# Beilage_xx.net
KiCad netlist of a schematic drawn in EAGLE
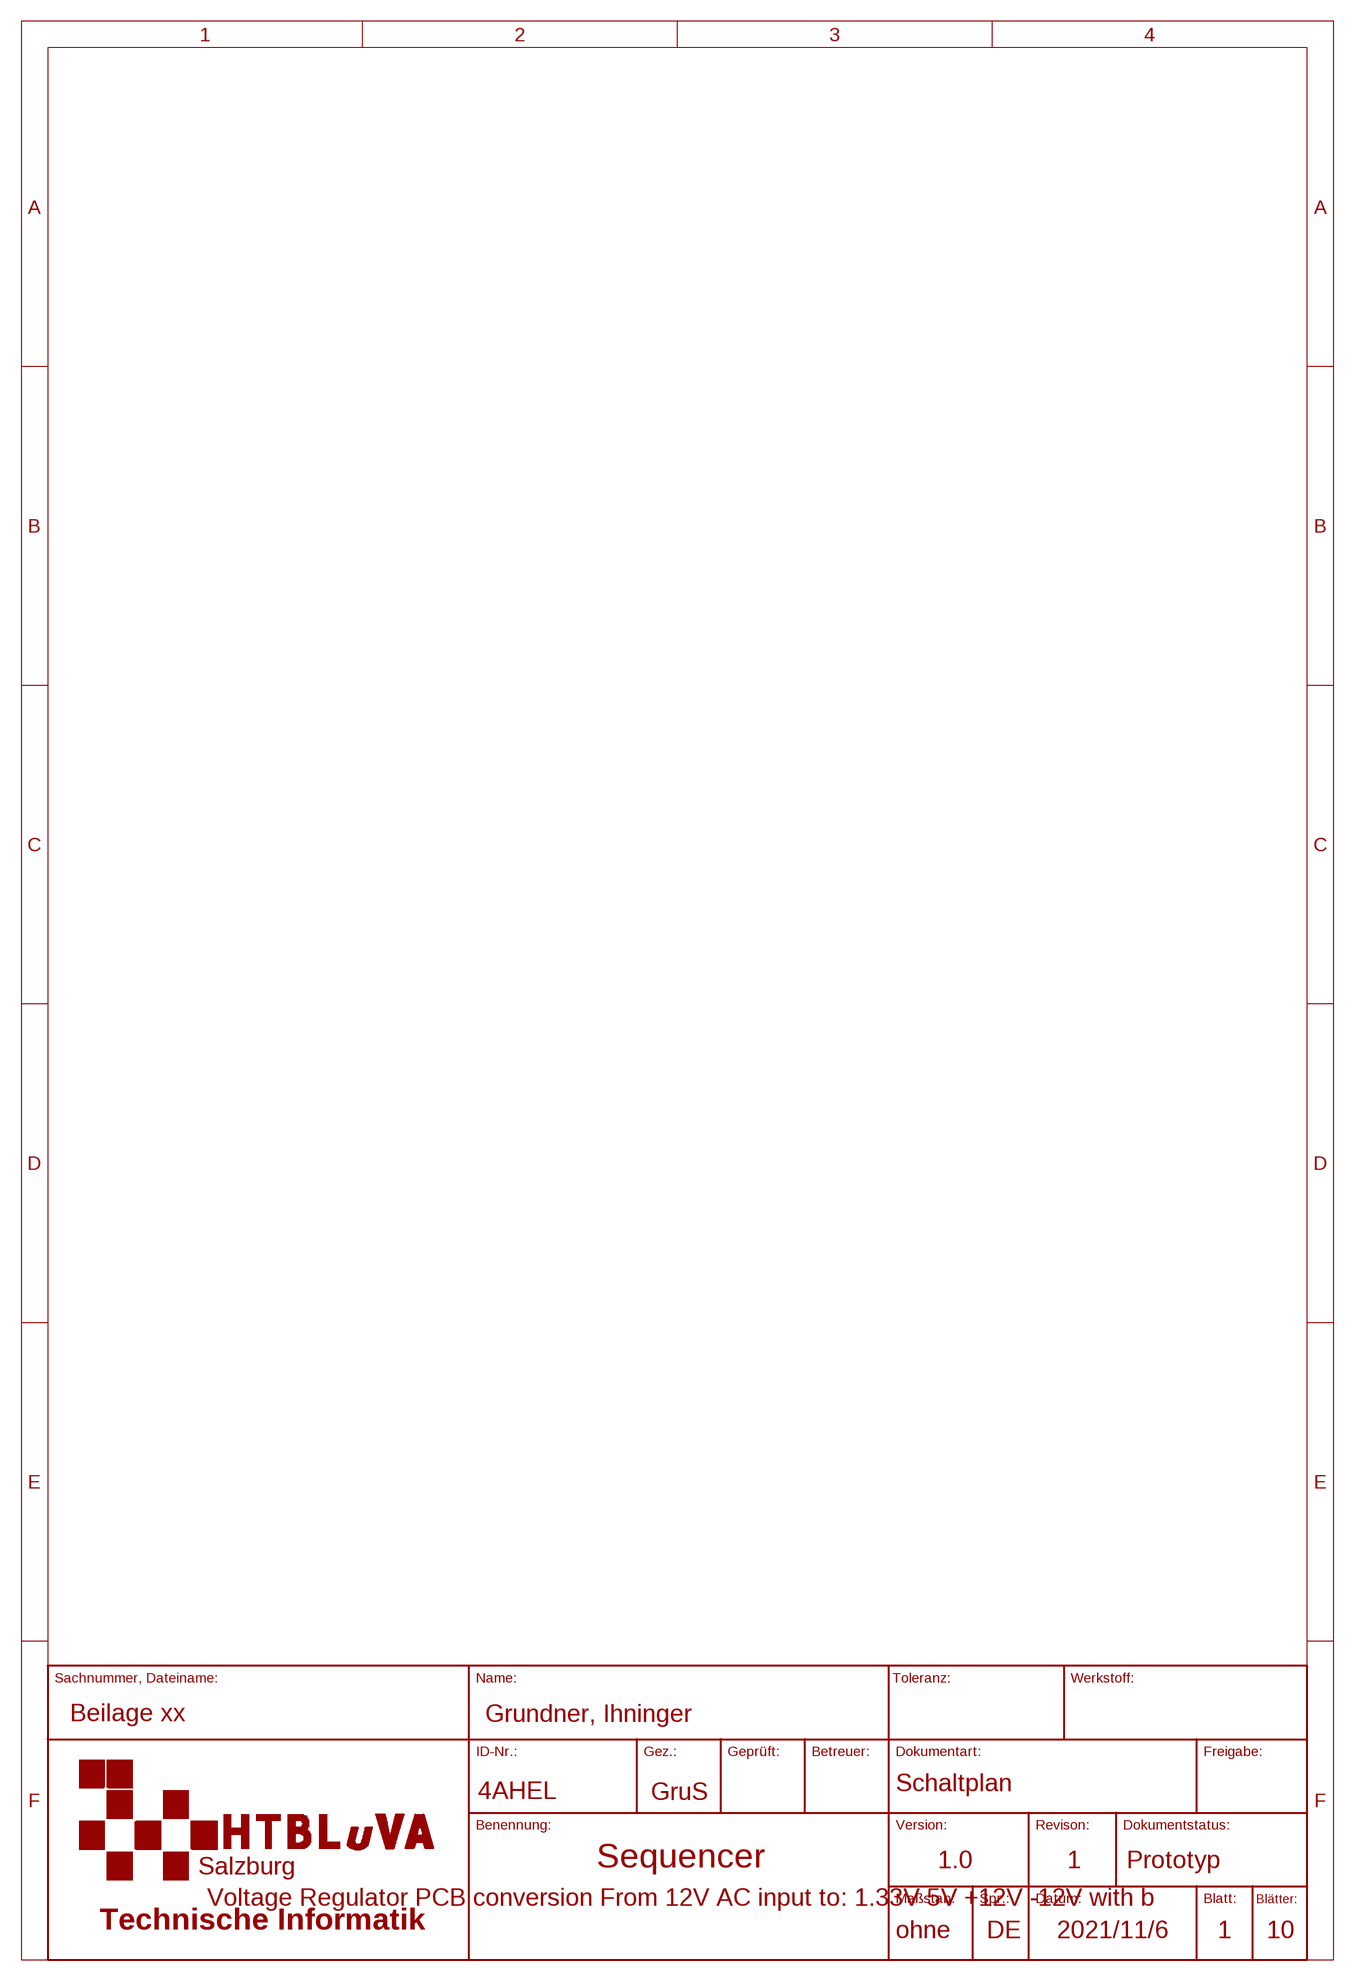
[diagram p0: schematic, sheet 1]
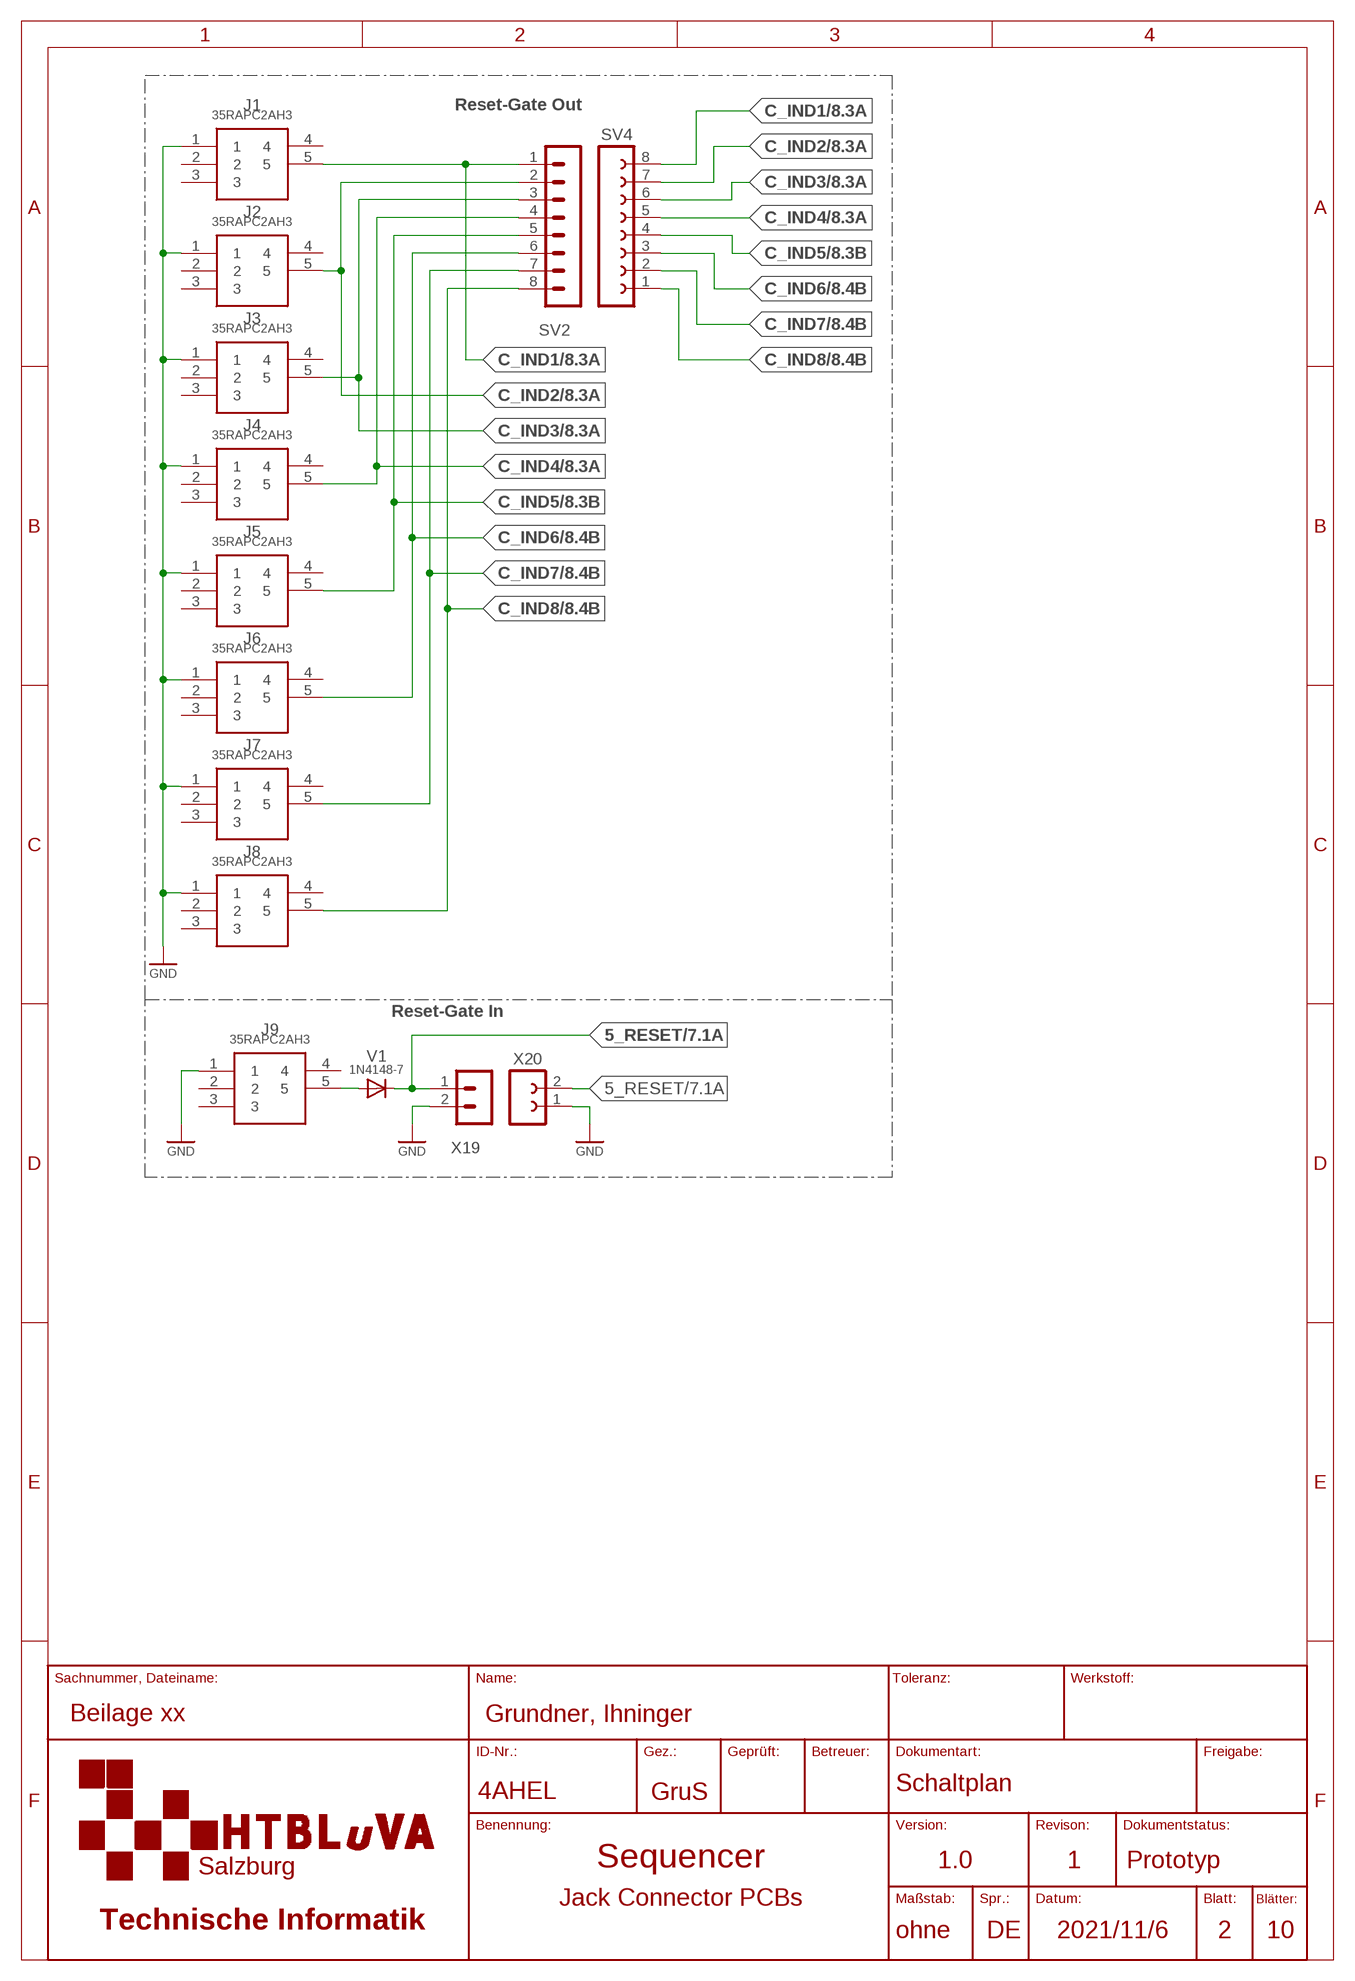
[diagram p1: schematic, sheet 2]
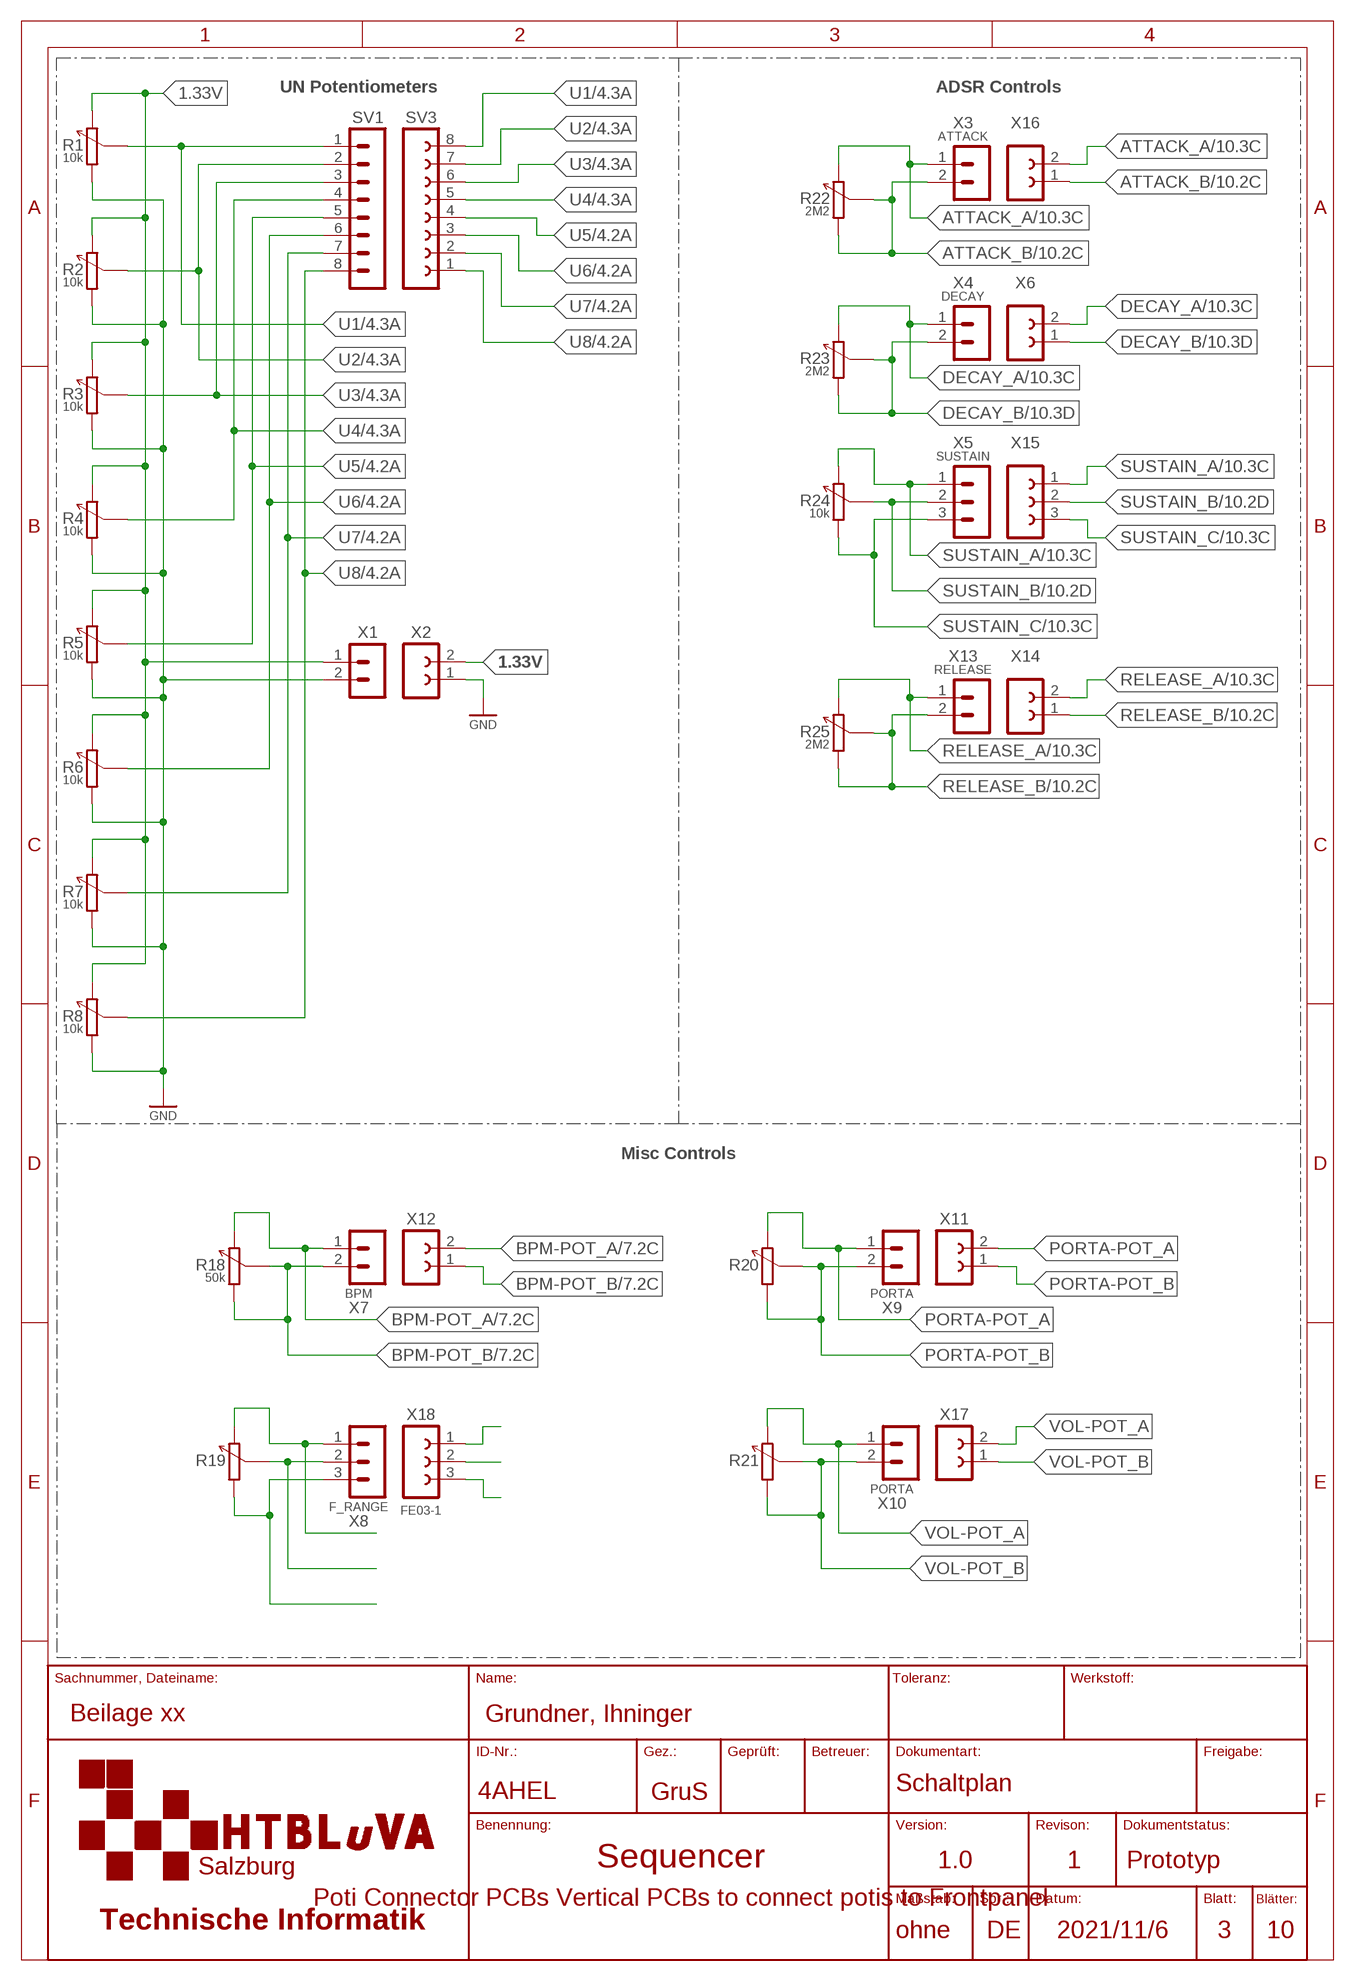
[diagram p2: schematic, sheet 3]
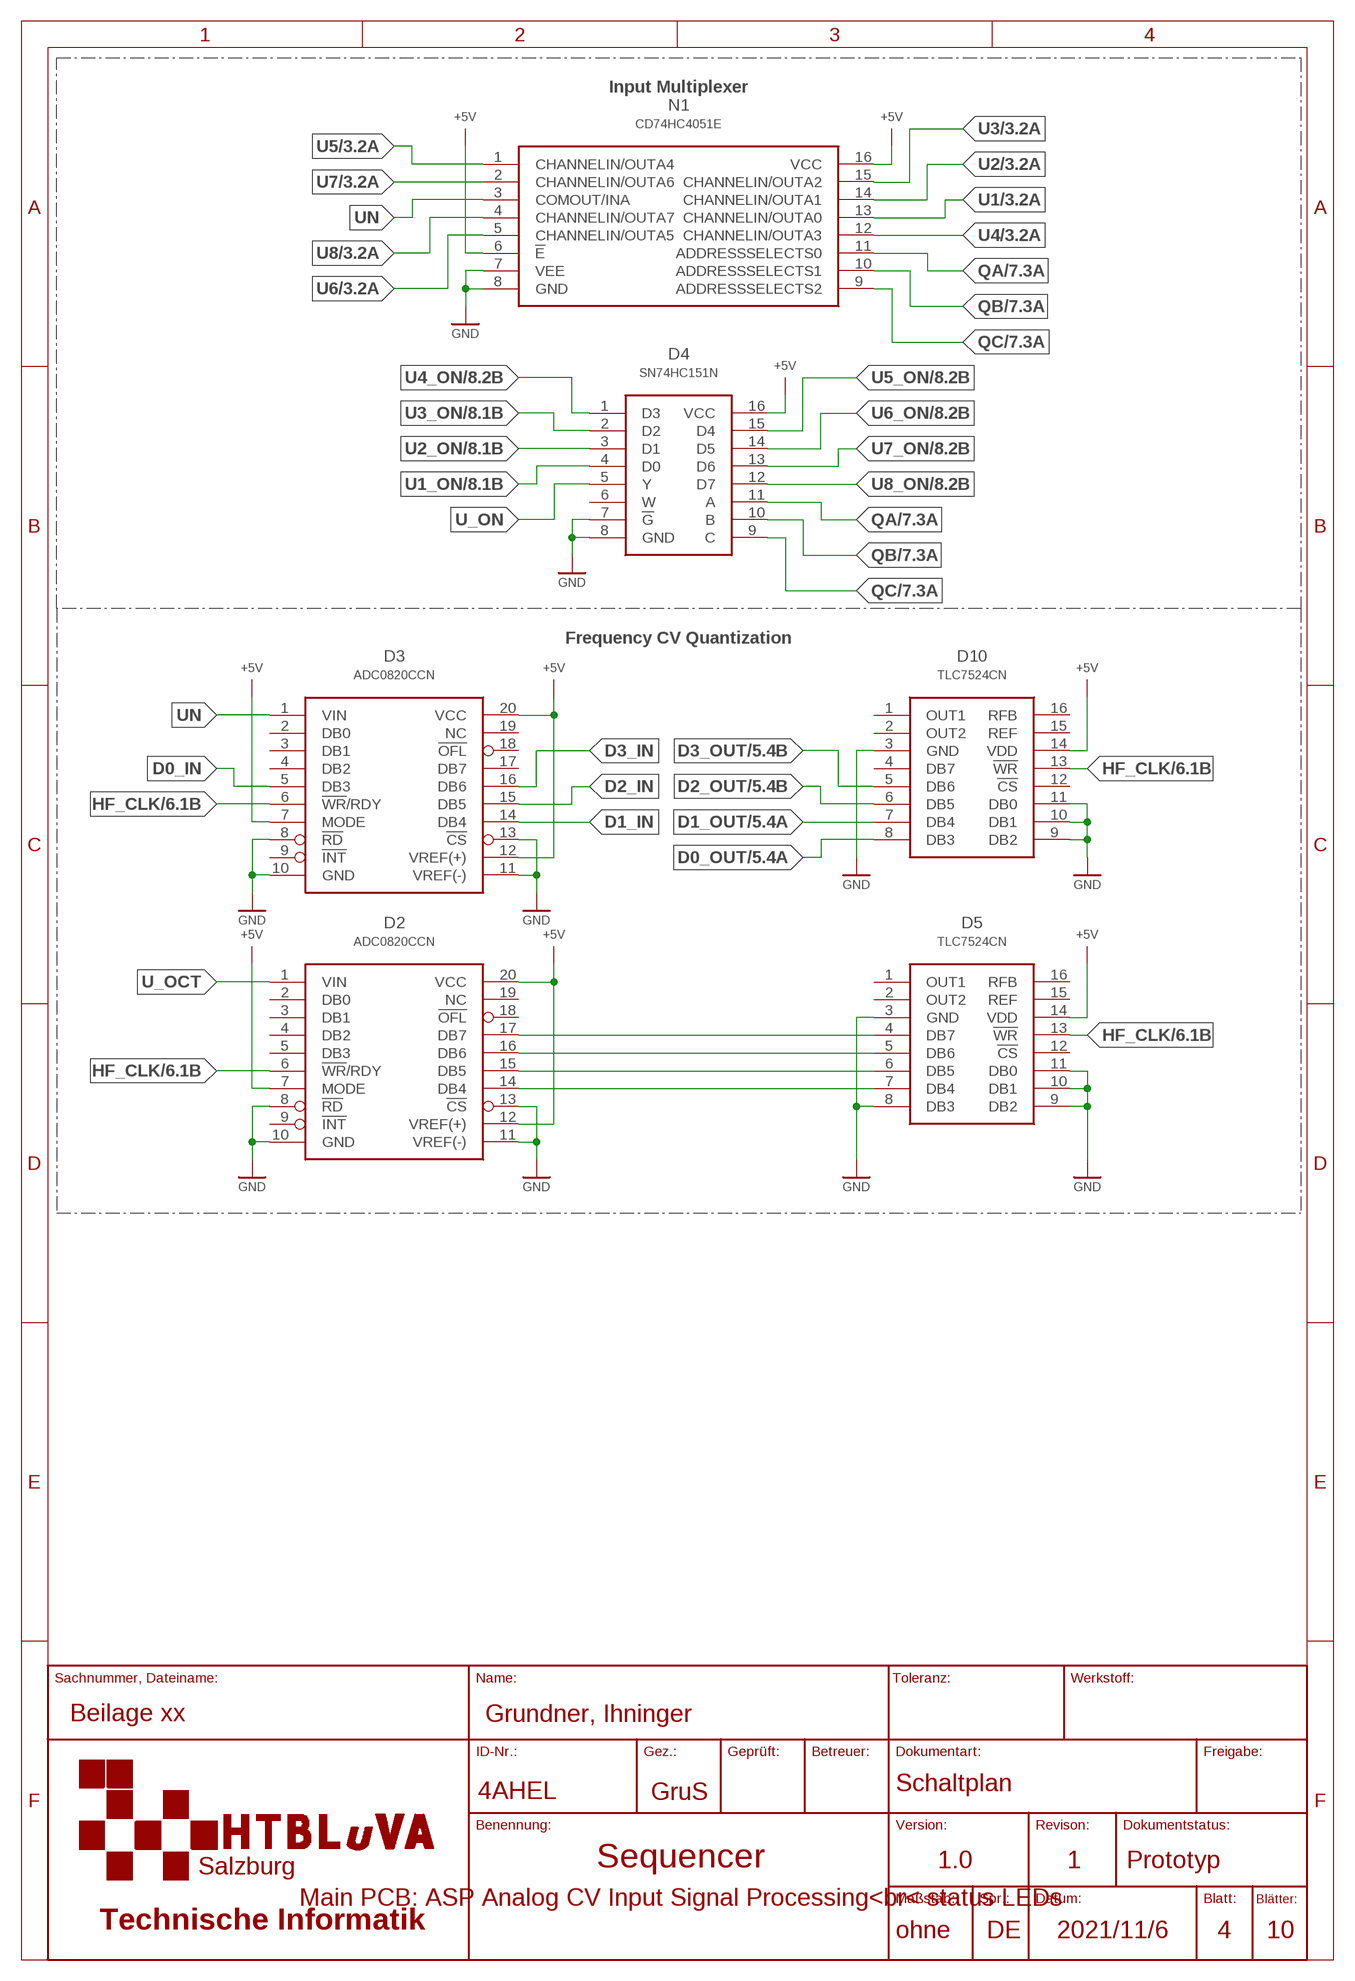
[diagram p3: schematic, sheet 4]
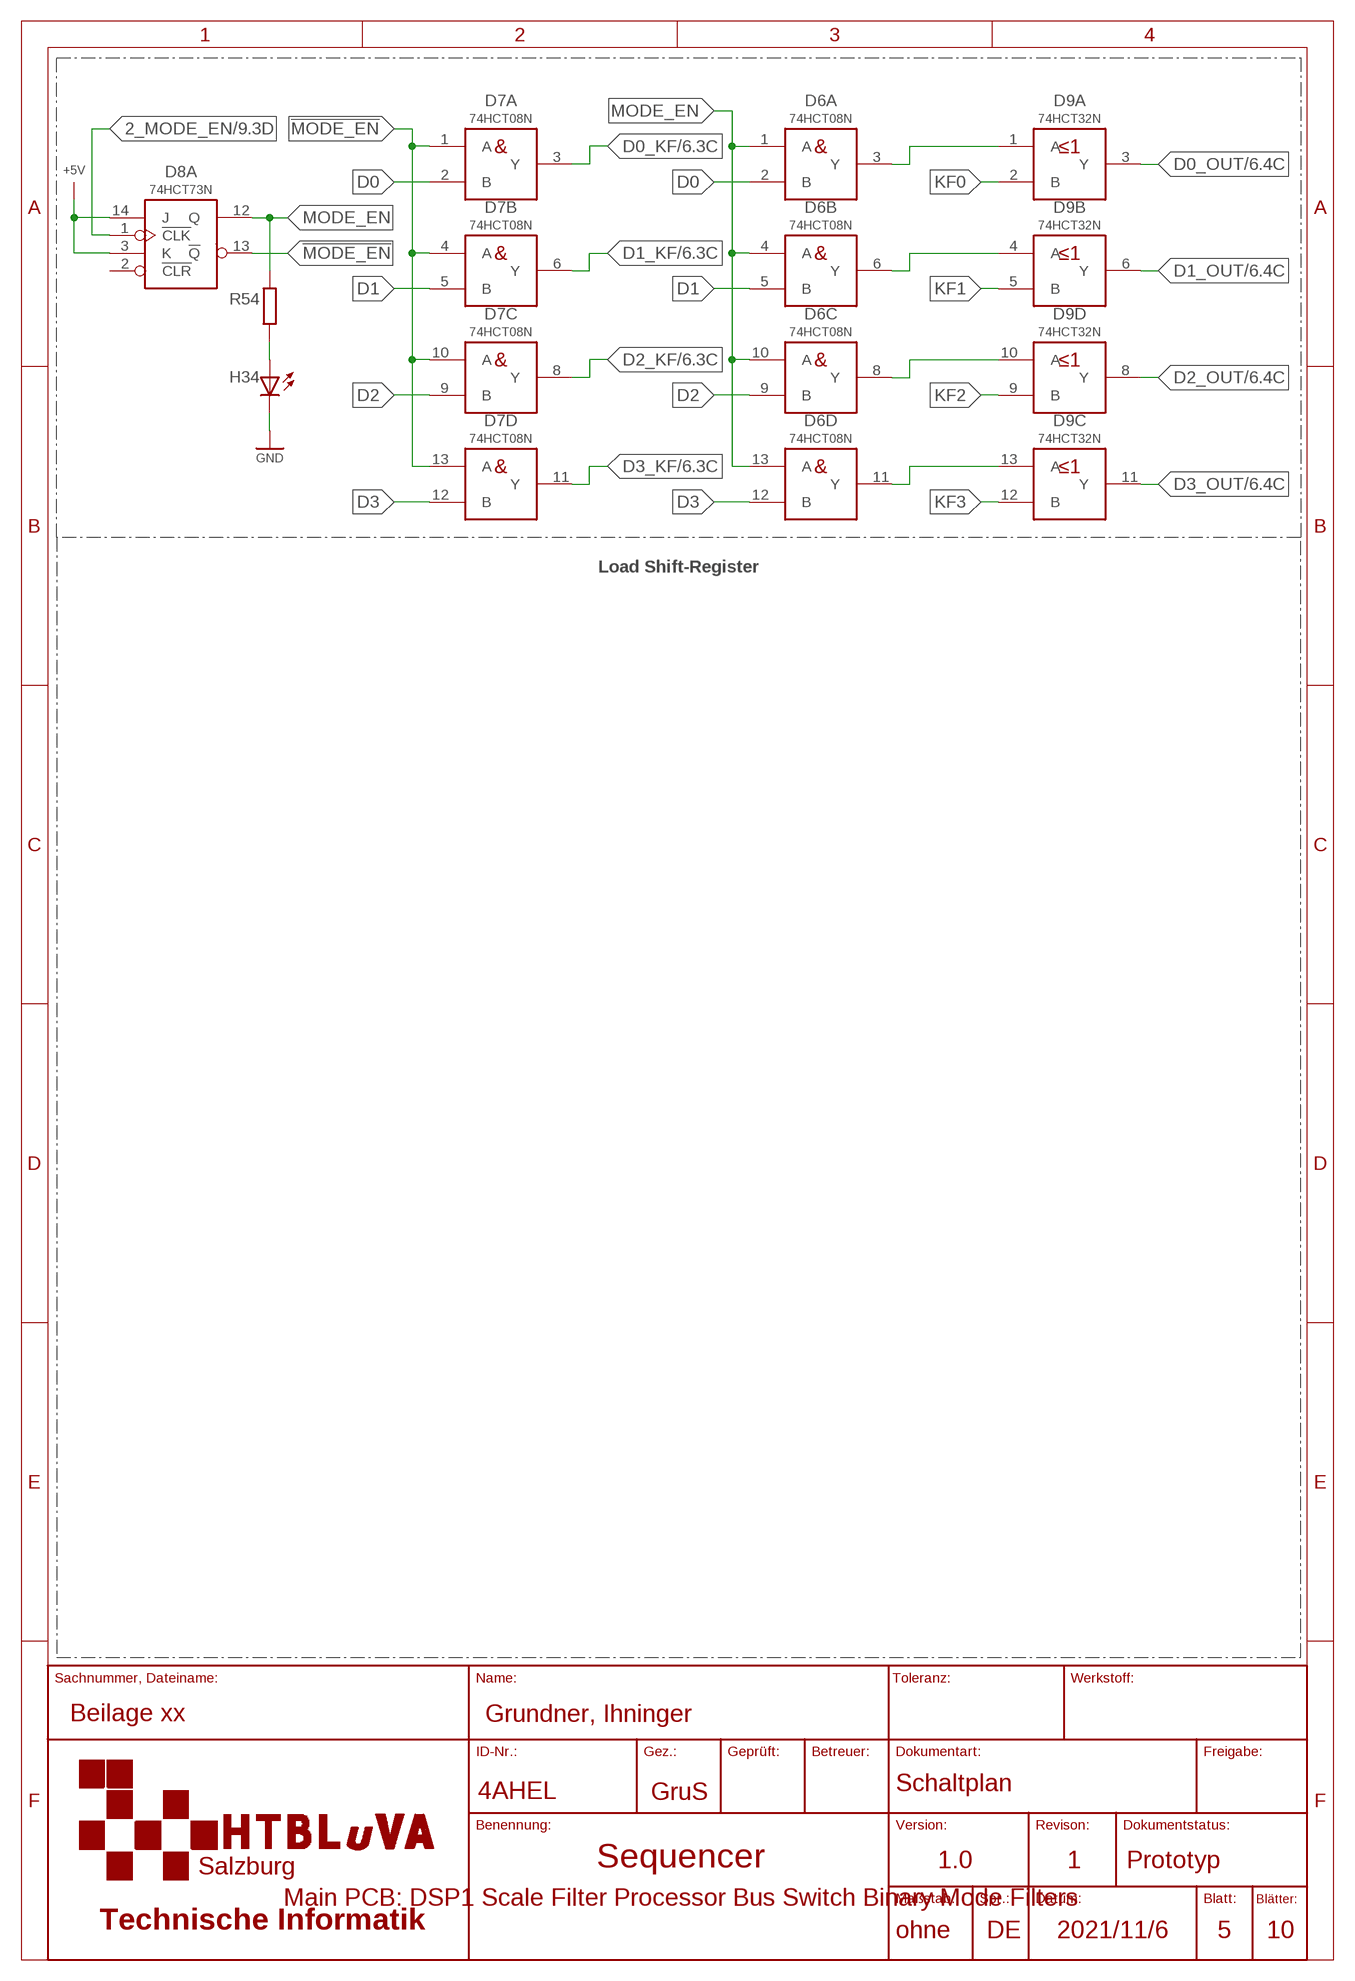
[diagram p4: schematic, sheet 5]
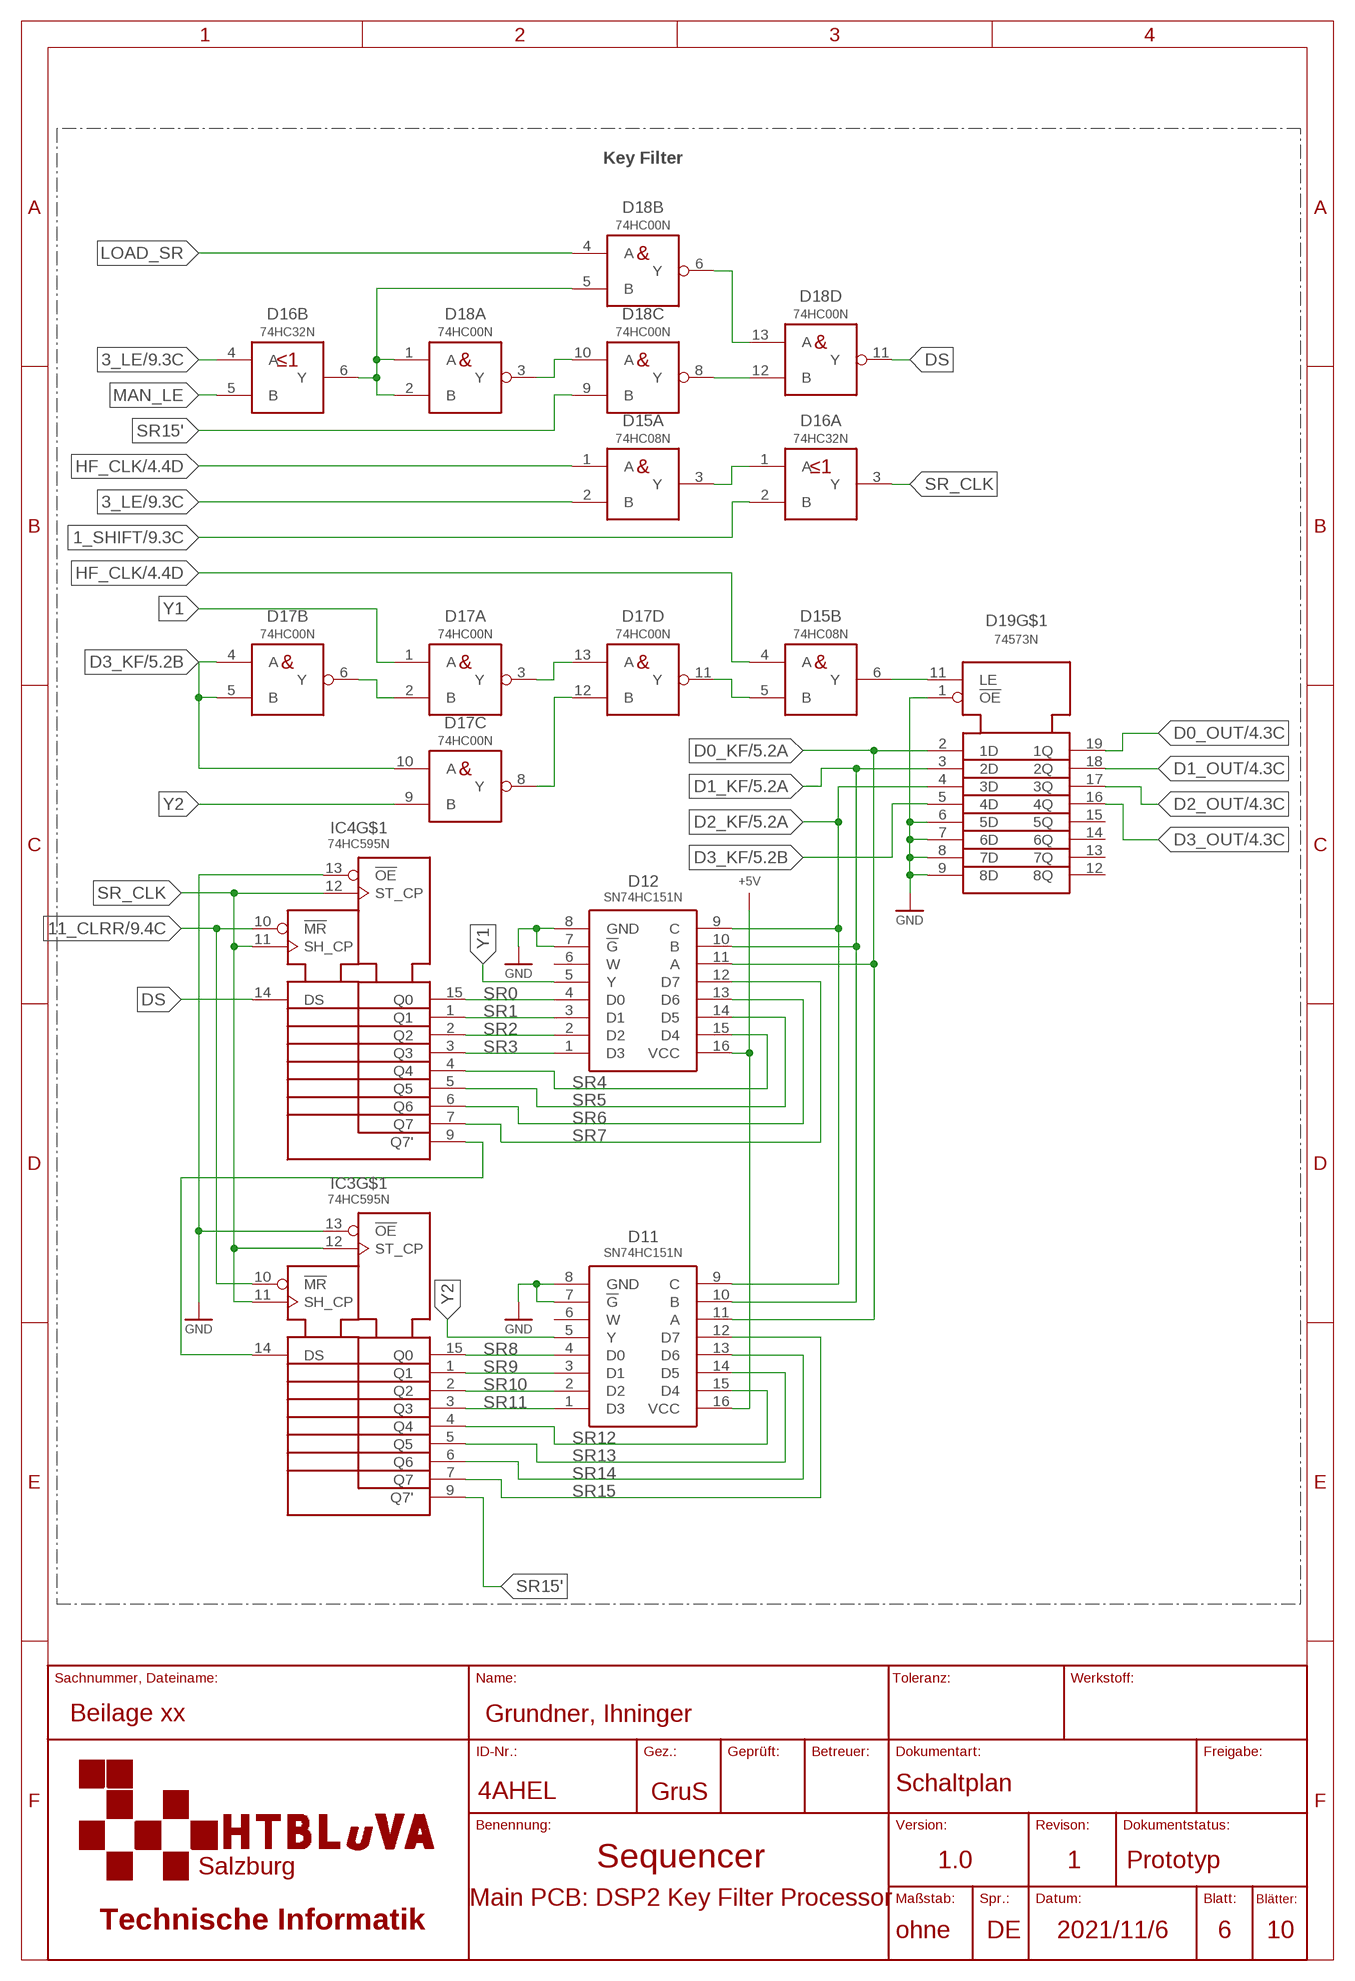
[diagram p5: schematic, sheet 6]
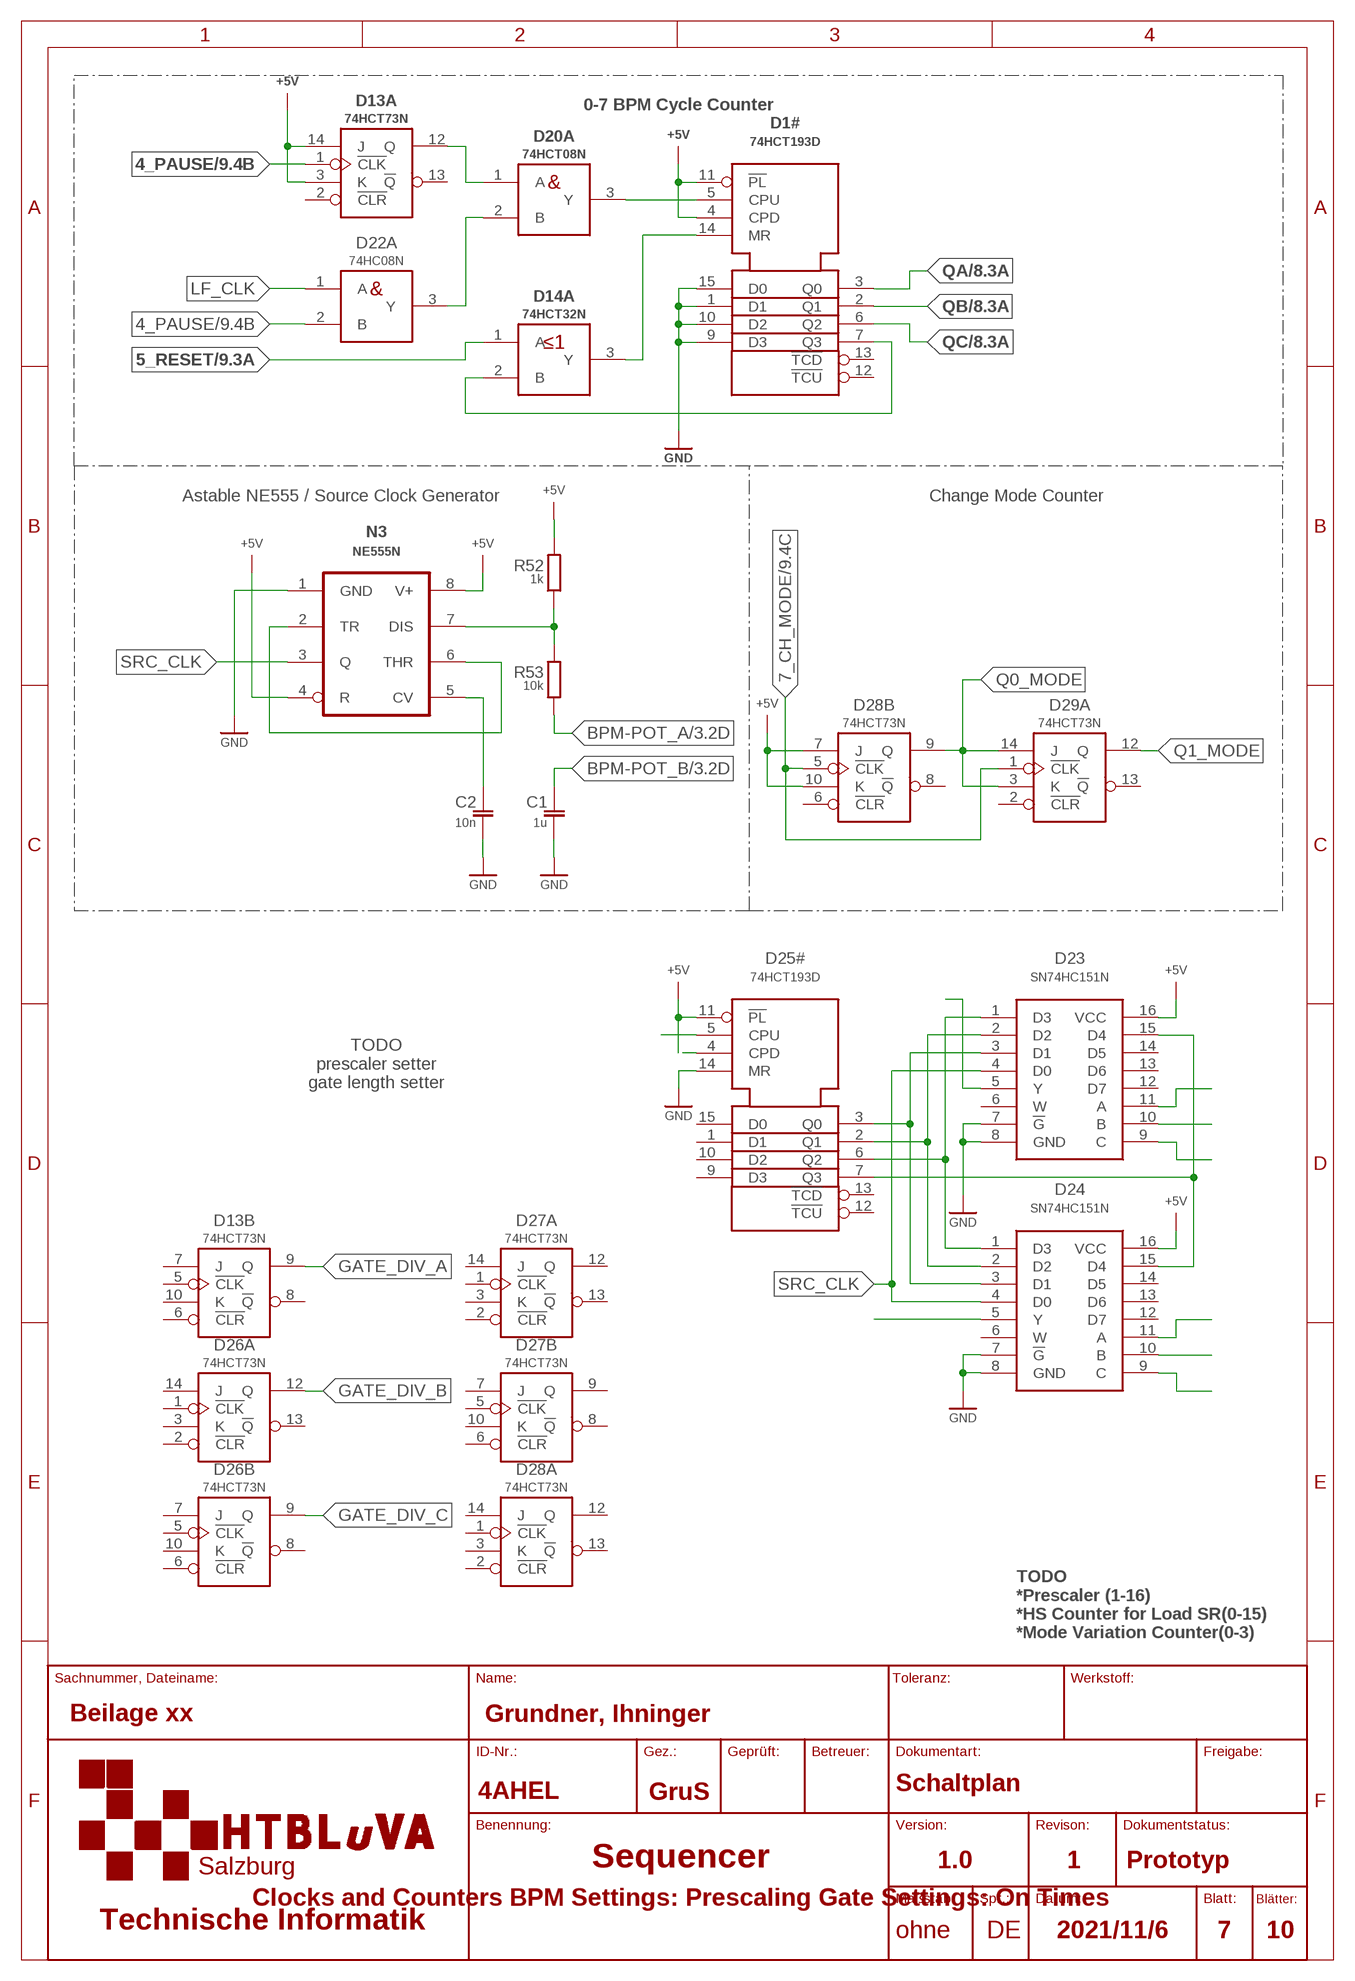
[diagram p6: schematic, sheet 7]
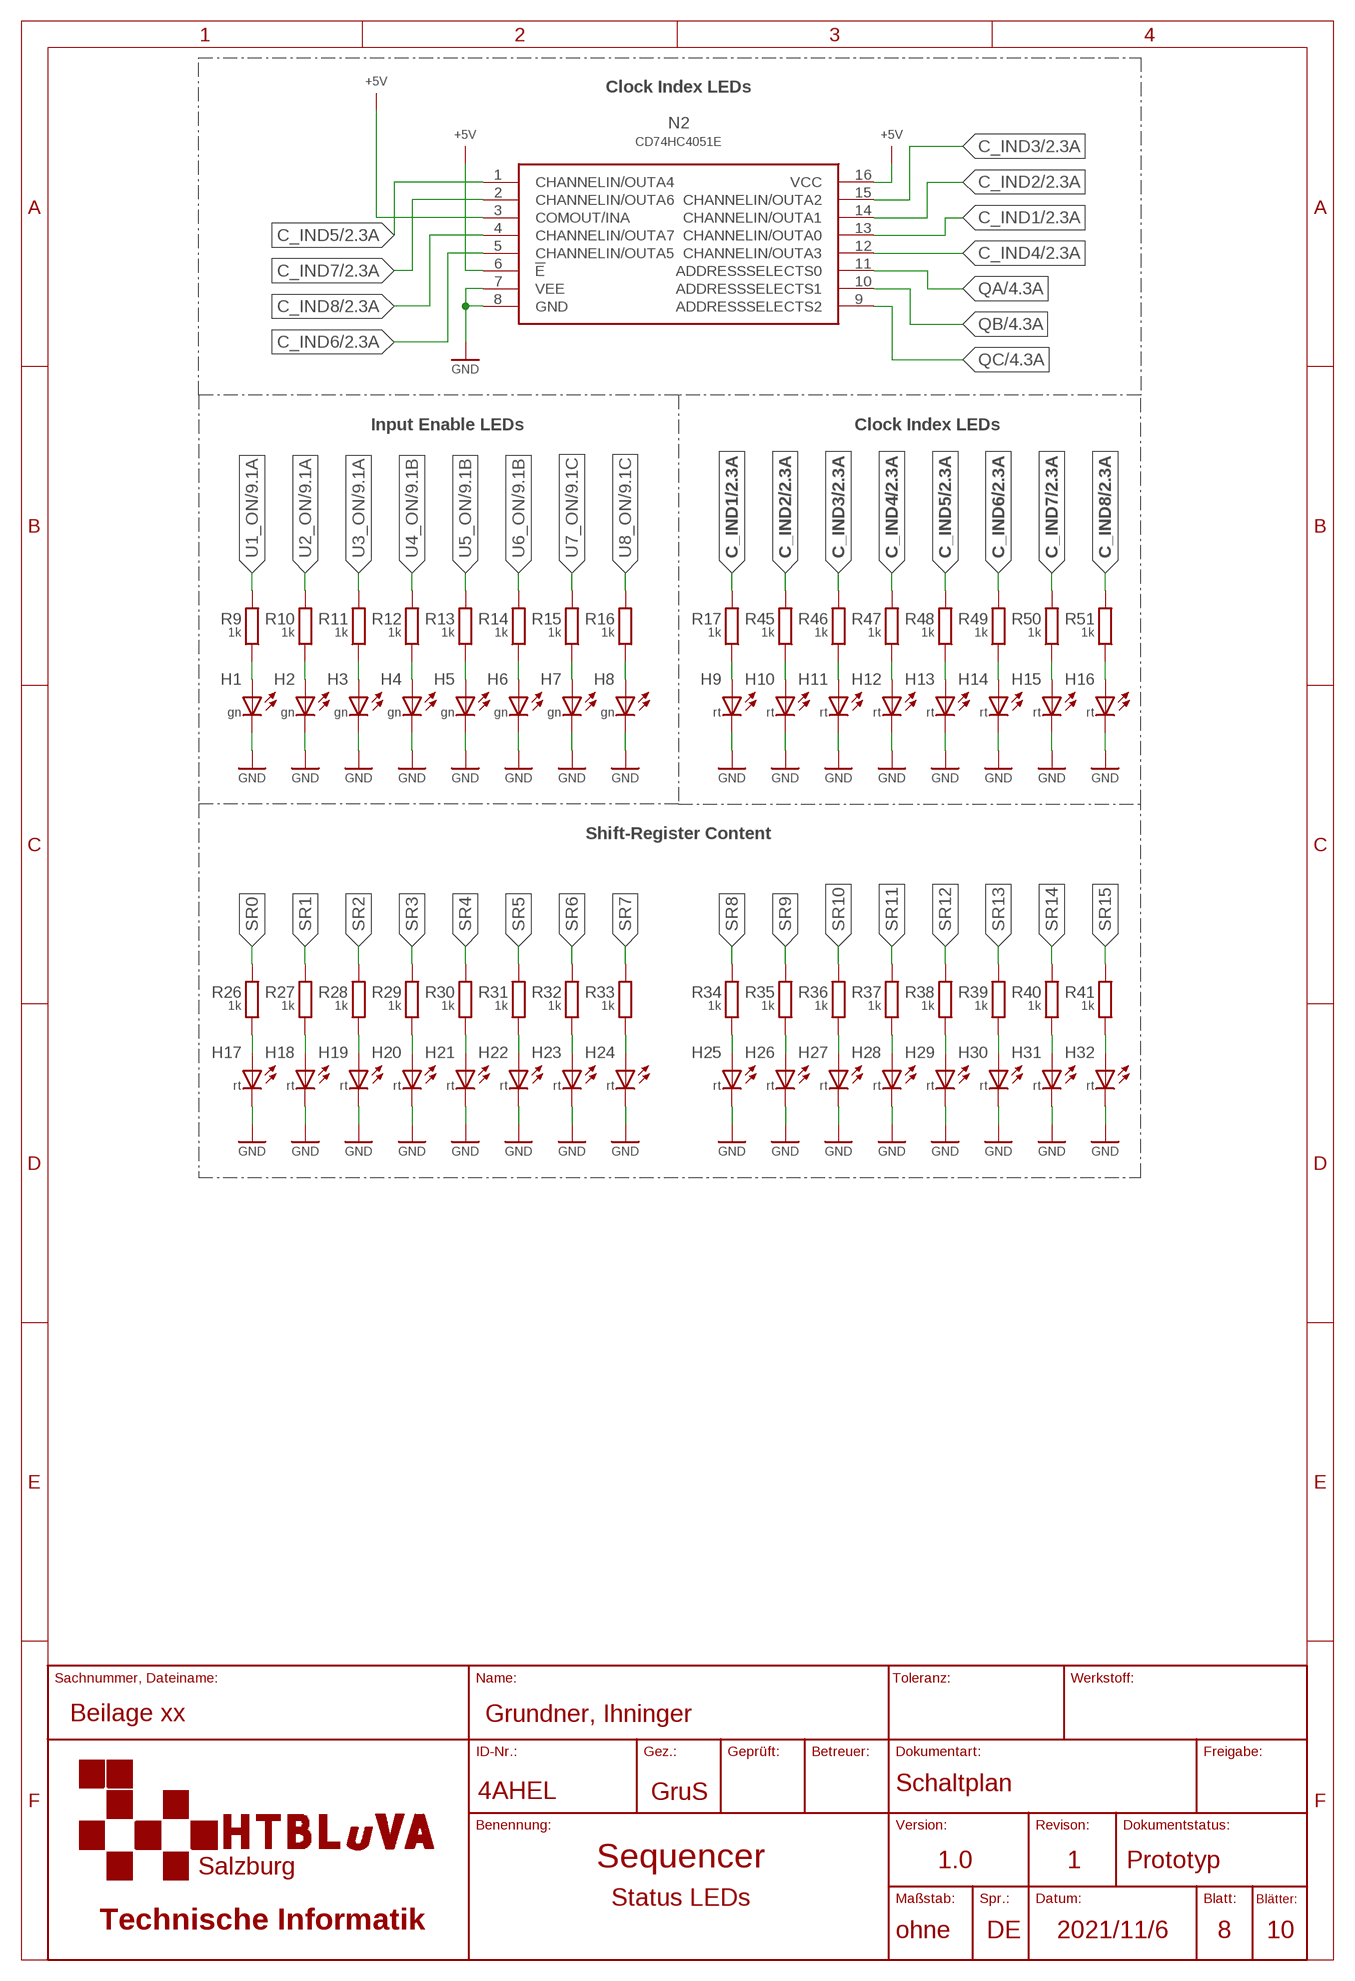
[diagram p7: schematic, sheet 8]
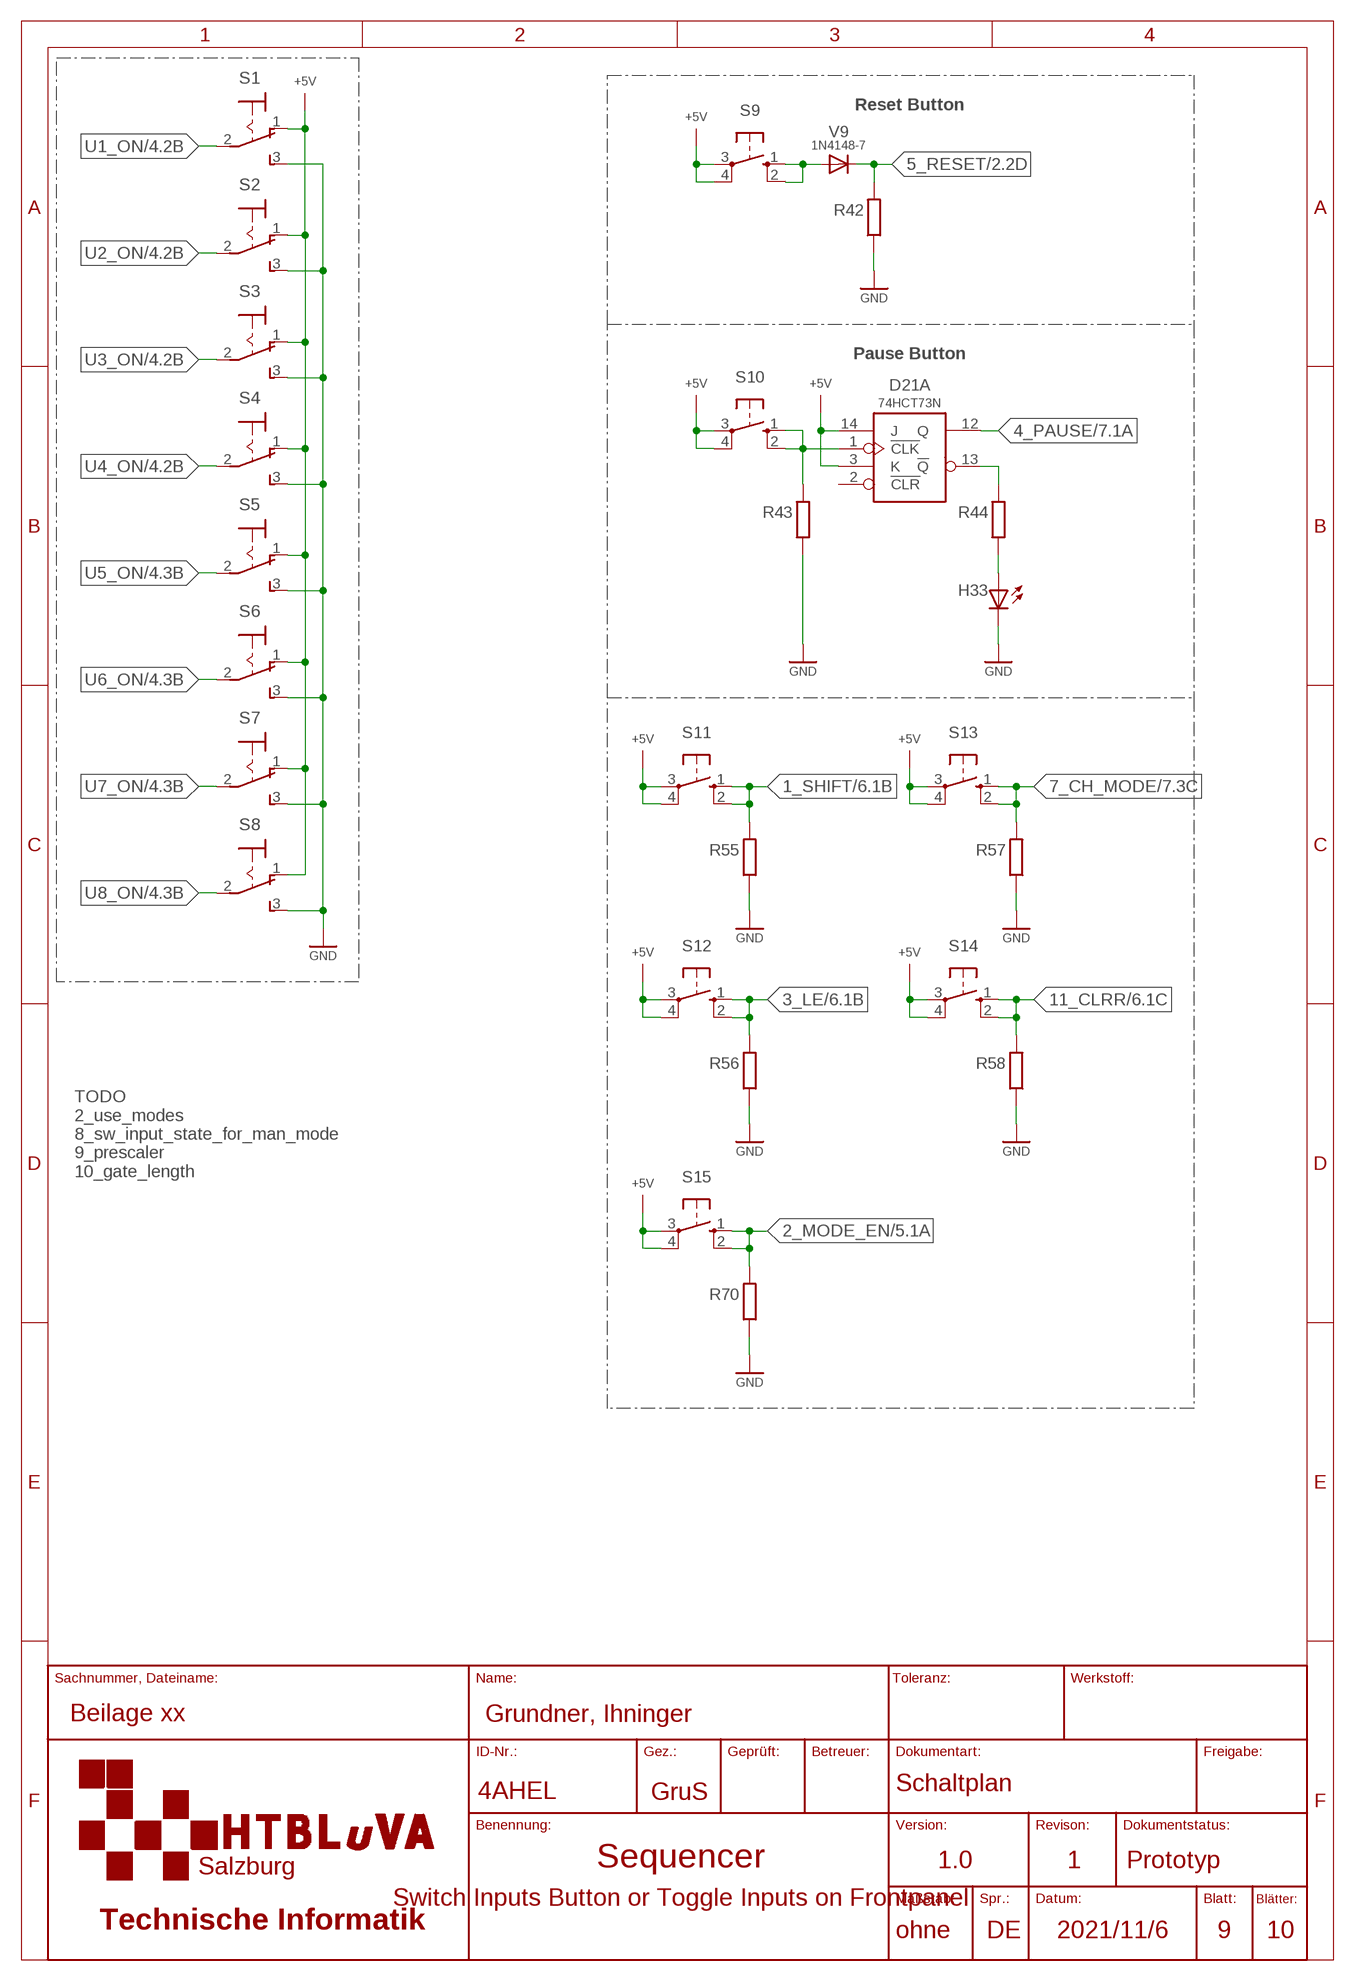
[diagram p8: schematic, sheet 9]
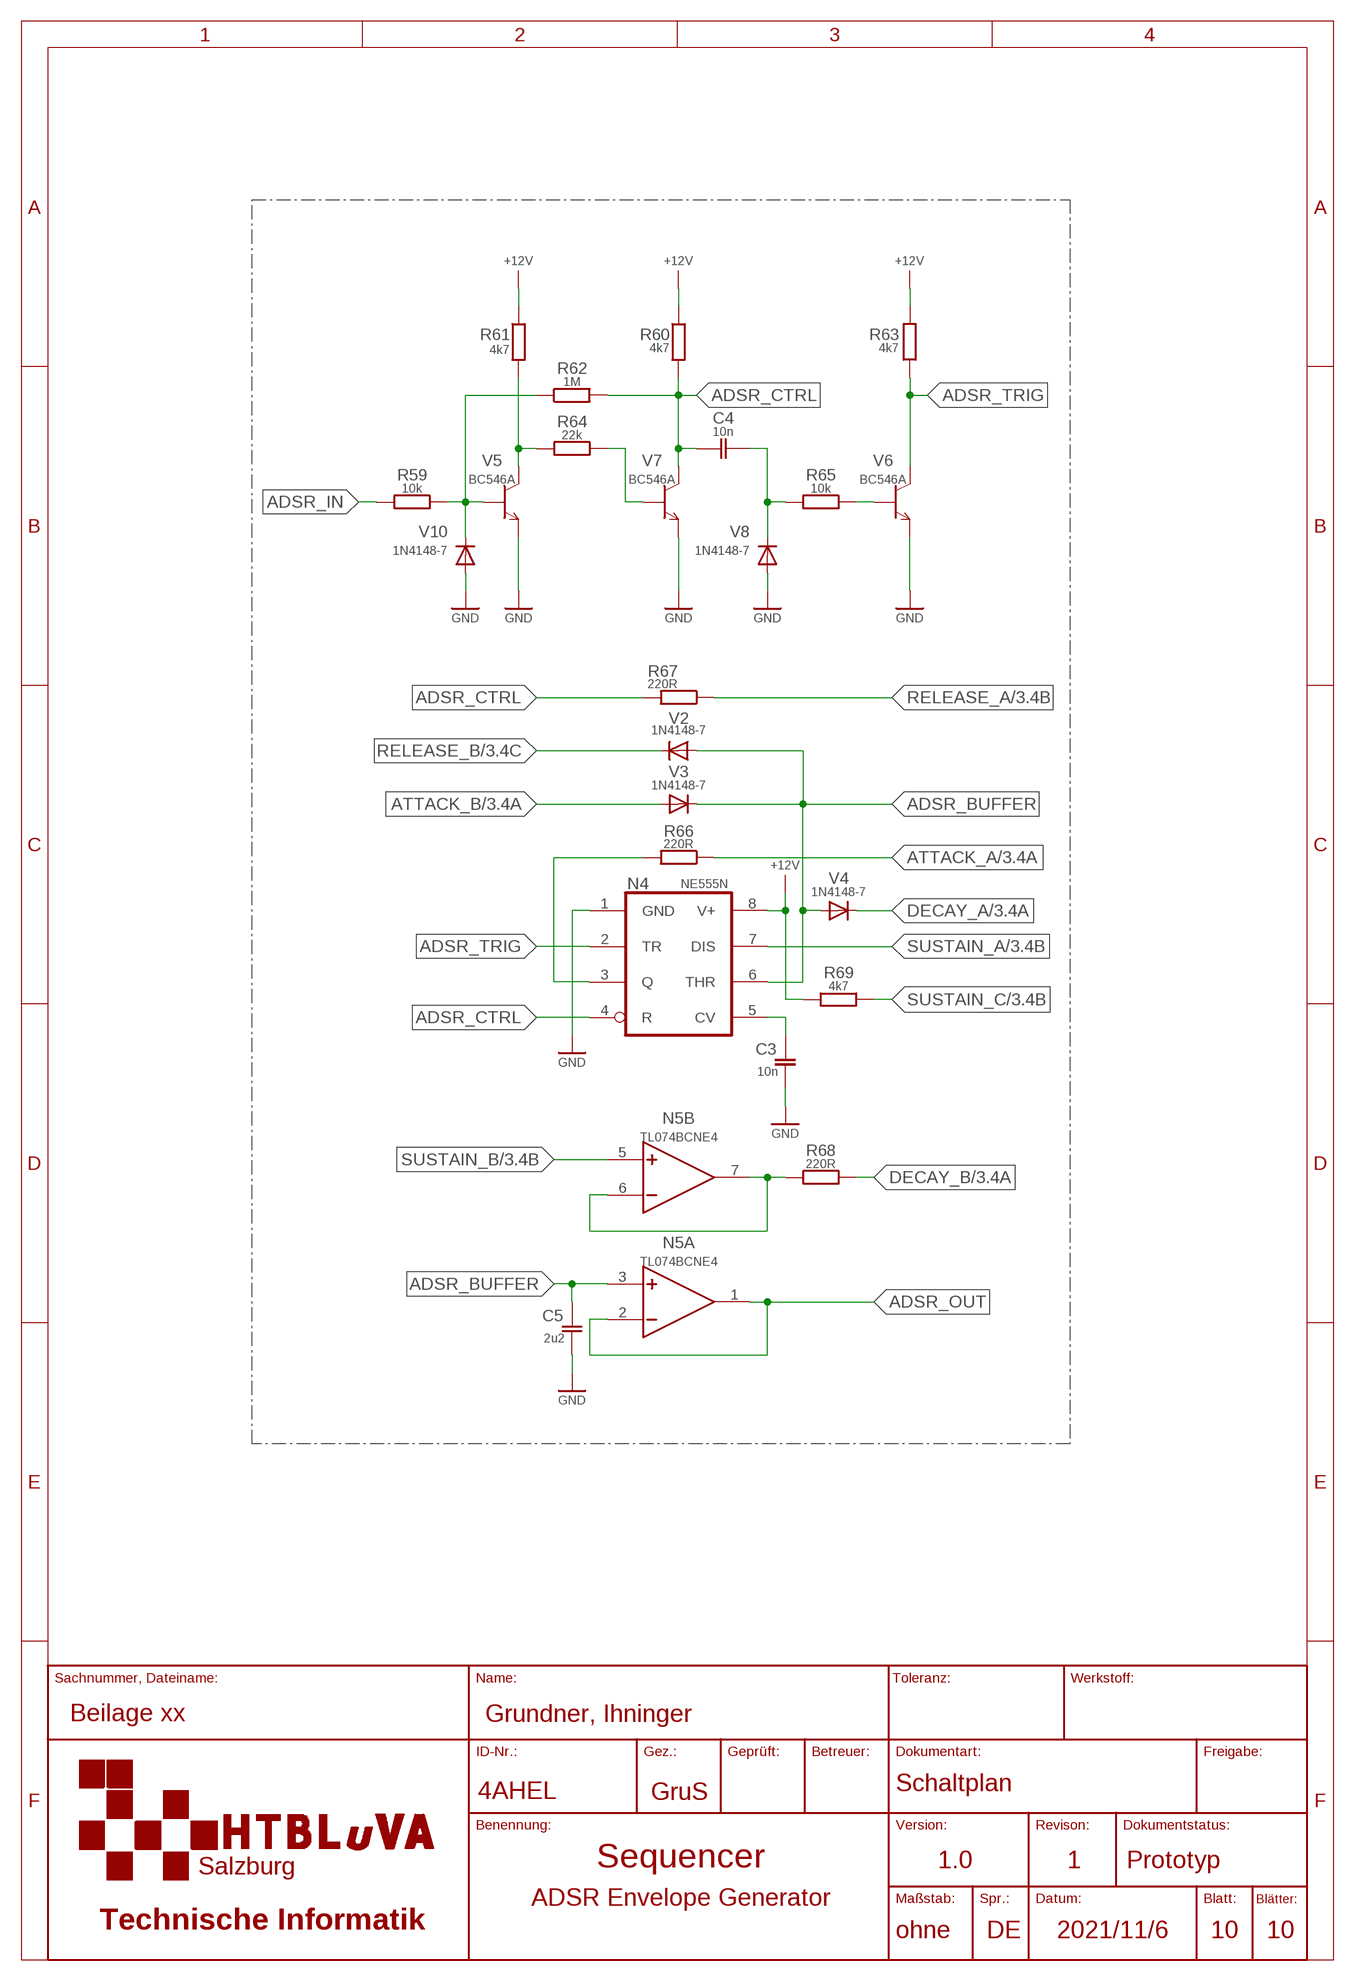
[diagram p9: schematic, sheet 10]

(export (version "E")
  (design (tool "Eeschema 10.0.6"))
  (components
    (comp (ref "C3")
      (value "10n")
      (footprint "eagle-import:C050-025X075")
      (libsource (lib "eagle-import") (part "C-EU050-025X075"))
    )
    (comp (ref "C4")
      (value "10n")
      (footprint "eagle-import:C050-025X075")
      (libsource (lib "eagle-import") (part "C-EU050-025X075"))
    )
    (comp (ref "C5")
      (value "2u2")
      (footprint "eagle-import:C050-025X075")
      (libsource (lib "eagle-import") (part "C-EU050-025X075"))
    )
    (comp (ref "N4")
      (value "NE555N")
      (footprint "eagle-import:DIL08")
      (libsource (lib "eagle-import") (part "NE555N"))
    )
    (comp (ref "N5")
      (value "TL074BCNE4")
      (footprint "eagle-import:DIL14")
      (libsource (lib "eagle-import") (part "TL074BCNE4"))
    )
    (comp (ref "R59")
      (value "10k")
      (footprint "eagle-import:R1206")
      (libsource (lib "eagle-import") (part "R-EUSR1206"))
    )
    (comp (ref "R60")
      (value "4k7")
      (footprint "eagle-import:R1206")
      (libsource (lib "eagle-import") (part "R-EUSR1206"))
    )
    (comp (ref "R61")
      (value "4k7")
      (footprint "eagle-import:R1206")
      (libsource (lib "eagle-import") (part "R-EUSR1206"))
    )
    (comp (ref "R62")
      (value "1M")
      (footprint "eagle-import:R1206")
      (libsource (lib "eagle-import") (part "R-EUSR1206"))
    )
    (comp (ref "R63")
      (value "4k7")
      (footprint "eagle-import:R1206")
      (libsource (lib "eagle-import") (part "R-EUSR1206"))
    )
    (comp (ref "R64")
      (value "22k")
      (footprint "eagle-import:R1206")
      (libsource (lib "eagle-import") (part "R-EUSR1206"))
    )
    (comp (ref "R65")
      (value "10k")
      (footprint "eagle-import:R1206")
      (libsource (lib "eagle-import") (part "R-EUSR1206"))
    )
    (comp (ref "R66")
      (value "220R")
      (footprint "eagle-import:R1206")
      (libsource (lib "eagle-import") (part "R-EUSR1206"))
    )
    (comp (ref "R67")
      (value "220R")
      (footprint "eagle-import:R1206")
      (libsource (lib "eagle-import") (part "R-EUSR1206"))
    )
    (comp (ref "R68")
      (value "220R")
      (footprint "eagle-import:R1206")
      (libsource (lib "eagle-import") (part "R-EUSR1206"))
    )
    (comp (ref "R69")
      (value "4k7")
      (footprint "eagle-import:R1206")
      (libsource (lib "eagle-import") (part "R-EUSR1206"))
    )
    (comp (ref "V2")
      (value "1N4148-7")
      (footprint "eagle-import:DO35-7")
      (libsource (lib "eagle-import") (part "1N4148-7"))
    )
    (comp (ref "V3")
      (value "1N4148-7")
      (footprint "eagle-import:DO35-7")
      (libsource (lib "eagle-import") (part "1N4148-7"))
    )
    (comp (ref "V4")
      (value "1N4148-7")
      (footprint "eagle-import:DO35-7")
      (libsource (lib "eagle-import") (part "1N4148-7"))
    )
    (comp (ref "V5")
      (value "BC546A")
      (footprint "eagle-import:TO92-123")
      (libsource (lib "eagle-import") (part "BC546A"))
    )
    (comp (ref "V6")
      (value "BC546A")
      (footprint "eagle-import:TO92-123")
      (libsource (lib "eagle-import") (part "BC546A"))
    )
    (comp (ref "V7")
      (value "BC546A")
      (footprint "eagle-import:TO92-123")
      (libsource (lib "eagle-import") (part "BC546A"))
    )
    (comp (ref "V8")
      (value "1N4148-7")
      (footprint "eagle-import:DO35-7")
      (libsource (lib "eagle-import") (part "1N4148-7"))
    )
    (comp (ref "V10")
      (value "1N4148-7")
      (footprint "eagle-import:DO35-7")
      (libsource (lib "eagle-import") (part "1N4148-7"))
    )
    (comp (ref "C1")
      (value "1u")
      (footprint "eagle-import:C050-025X075")
      (libsource (lib "eagle-import") (part "C-EU050-025X075"))
    )
    (comp (ref "C2")
      (value "10n")
      (footprint "eagle-import:C050-025X075")
      (libsource (lib "eagle-import") (part "C-EU050-025X075"))
    )
    (comp (ref "D1")
      (value "74HCT193D")
      (footprint "eagle-import:SO16")
      (libsource (lib "eagle-import") (part "74193DHCT"))
    )
    (comp (ref "D13")
      (value "74HCT73N")
      (footprint "eagle-import:DIP14")
      (libsource (lib "eagle-import") (part "7473NHCT"))
    )
    (comp (ref "D14")
      (value "74HCT32N")
      (footprint "eagle-import:DIP14")
      (libsource (lib "eagle-import") (part "7432NHCT"))
    )
    (comp (ref "D20")
      (value "74HCT08N")
      (footprint "eagle-import:DIP14")
      (libsource (lib "eagle-import") (part "7408NHCT"))
    )
    (comp (ref "D22")
      (value "74HC08N")
      (footprint "eagle-import:DIP14")
      (libsource (lib "eagle-import") (part "7408NHC"))
    )
    (comp (ref "D23")
      (value "SN74HC151N")
      (footprint "eagle-import:DIP16")
      (fields (field (name "MOUSER_PART_NUMBER") "595-SN74HC151N"))
      (libsource (lib "eagle-import") (part "SN74HC151N"))
    )
    (comp (ref "D24")
      (value "SN74HC151N")
      (footprint "eagle-import:DIP16")
      (fields (field (name "MOUSER_PART_NUMBER") "595-SN74HC151N"))
      (libsource (lib "eagle-import") (part "SN74HC151N"))
    )
    (comp (ref "D25")
      (value "74HCT193D")
      (footprint "eagle-import:SO16")
      (libsource (lib "eagle-import") (part "74193DHCT"))
    )
    (comp (ref "D26")
      (value "74HCT73N")
      (footprint "eagle-import:DIP14")
      (libsource (lib "eagle-import") (part "7473NHCT"))
    )
    (comp (ref "D27")
      (value "74HCT73N")
      (footprint "eagle-import:DIP14")
      (libsource (lib "eagle-import") (part "7473NHCT"))
    )
    (comp (ref "D28")
      (value "74HCT73N")
      (footprint "eagle-import:DIP14")
      (libsource (lib "eagle-import") (part "7473NHCT"))
    )
    (comp (ref "D29")
      (value "74HCT73N")
      (footprint "eagle-import:DIP14")
      (libsource (lib "eagle-import") (part "7473NHCT"))
    )
    (comp (ref "N3")
      (value "NE555N")
      (footprint "eagle-import:DIL08")
      (libsource (lib "eagle-import") (part "NE555N"))
    )
    (comp (ref "R52")
      (value "1k")
      (footprint "eagle-import:R1206")
      (libsource (lib "eagle-import") (part "R-EUSR1206"))
    )
    (comp (ref "R53")
      (value "10k")
      (footprint "eagle-import:R1206")
      (libsource (lib "eagle-import") (part "R-EUSR1206"))
    )
    (comp (ref "R1")
      (value "10k")
      (footprint "eagle-import:R-POT-PANEL-MOUNT")
      (libsource (lib "eagle-import") (part "R-POT"))
    )
    (comp (ref "R2")
      (value "10k")
      (footprint "eagle-import:R-POT-PANEL-MOUNT")
      (libsource (lib "eagle-import") (part "R-POT"))
    )
    (comp (ref "R3")
      (value "10k")
      (footprint "eagle-import:R-POT-PANEL-MOUNT")
      (libsource (lib "eagle-import") (part "R-POT"))
    )
    (comp (ref "R4")
      (value "10k")
      (footprint "eagle-import:R-POT-PANEL-MOUNT")
      (libsource (lib "eagle-import") (part "R-POT"))
    )
    (comp (ref "R5")
      (value "10k")
      (footprint "eagle-import:R-POT-PANEL-MOUNT")
      (libsource (lib "eagle-import") (part "R-POT"))
    )
    (comp (ref "R6")
      (value "10k")
      (footprint "eagle-import:R-POT-PANEL-MOUNT")
      (libsource (lib "eagle-import") (part "R-POT"))
    )
    (comp (ref "R7")
      (value "10k")
      (footprint "eagle-import:R-POT-PANEL-MOUNT")
      (libsource (lib "eagle-import") (part "R-POT"))
    )
    (comp (ref "R8")
      (value "10k")
      (footprint "eagle-import:R-POT-PANEL-MOUNT")
      (libsource (lib "eagle-import") (part "R-POT"))
    )
    (comp (ref "R18")
      (value "50k")
      (footprint "eagle-import:R-POT-PANEL-MOUNT")
      (libsource (lib "eagle-import") (part "R-POT"))
    )
    (comp (ref "R19")
      (value "R-POT")
      (footprint "eagle-import:R-POT-PANEL-MOUNT")
      (libsource (lib "eagle-import") (part "R-POT"))
    )
    (comp (ref "R20")
      (value "R-POT")
      (footprint "eagle-import:R-POT-PANEL-MOUNT")
      (libsource (lib "eagle-import") (part "R-POT"))
    )
    (comp (ref "R21")
      (value "R-POT")
      (footprint "eagle-import:R-POT-PANEL-MOUNT")
      (libsource (lib "eagle-import") (part "R-POT"))
    )
    (comp (ref "R22")
      (value "2M2")
      (footprint "eagle-import:R-POT-PANEL-MOUNT")
      (libsource (lib "eagle-import") (part "R-POT"))
    )
    (comp (ref "R23")
      (value "2M2")
      (footprint "eagle-import:R-POT-PANEL-MOUNT")
      (libsource (lib "eagle-import") (part "R-POT"))
    )
    (comp (ref "R24")
      (value "10k")
      (footprint "eagle-import:R-POT-PANEL-MOUNT")
      (libsource (lib "eagle-import") (part "R-POT"))
    )
    (comp (ref "R25")
      (value "2M2")
      (footprint "eagle-import:R-POT-PANEL-MOUNT")
      (libsource (lib "eagle-import") (part "R-POT"))
    )
    (comp (ref "SV1")
      (value "MA08-1W")
      (footprint "eagle-import:MA08-1W")
      (libsource (lib "eagle-import") (part "MA08-1W"))
    )
    (comp (ref "SV3")
      (value "FE08-1")
      (footprint "eagle-import:FE08")
      (libsource (lib "eagle-import") (part "FE08-1"))
    )
    (comp (ref "X1")
      (value "MA02-1W")
      (footprint "eagle-import:MA02-1W")
      (libsource (lib "eagle-import") (part "MA02-1W"))
    )
    (comp (ref "X2")
      (value "FE02-10.8MM")
      (footprint "eagle-import:FE02-1")
      (libsource (lib "eagle-import") (part "FE02-10.8MM"))
    )
    (comp (ref "X3")
      (value "ATTACK")
      (footprint "eagle-import:MA02-1W")
      (libsource (lib "eagle-import") (part "MA02-1W"))
    )
    (comp (ref "X4")
      (value "DECAY")
      (footprint "eagle-import:MA02-1W")
      (libsource (lib "eagle-import") (part "MA02-1W"))
    )
    (comp (ref "X5")
      (value "SUSTAIN")
      (footprint "eagle-import:MA03-1W")
      (libsource (lib "eagle-import") (part "MA03-1W"))
    )
    (comp (ref "X6")
      (value "FE02-10.8MM")
      (footprint "eagle-import:FE02-1")
      (libsource (lib "eagle-import") (part "FE02-10.8MM"))
    )
    (comp (ref "X7")
      (value "BPM")
      (footprint "eagle-import:MA02-1W")
      (libsource (lib "eagle-import") (part "MA02-1W"))
    )
    (comp (ref "X8")
      (value "F_RANGE")
      (footprint "eagle-import:MA03-1W")
      (libsource (lib "eagle-import") (part "MA03-1W"))
    )
    (comp (ref "X9")
      (value "PORTA")
      (footprint "eagle-import:MA02-1W")
      (libsource (lib "eagle-import") (part "MA02-1W"))
    )
    (comp (ref "X10")
      (value "PORTA")
      (footprint "eagle-import:MA02-1W")
      (libsource (lib "eagle-import") (part "MA02-1W"))
    )
    (comp (ref "X11")
      (value "FE02-10.8MM")
      (footprint "eagle-import:FE02-1")
      (libsource (lib "eagle-import") (part "FE02-10.8MM"))
    )
    (comp (ref "X12")
      (value "FE02-10.8MM")
      (footprint "eagle-import:FE02-1")
      (libsource (lib "eagle-import") (part "FE02-10.8MM"))
    )
    (comp (ref "X13")
      (value "RELEASE")
      (footprint "eagle-import:MA02-1W")
      (libsource (lib "eagle-import") (part "MA02-1W"))
    )
    (comp (ref "X14")
      (value "FE02-10.8MM")
      (footprint "eagle-import:FE02-1")
      (libsource (lib "eagle-import") (part "FE02-10.8MM"))
    )
    (comp (ref "X15")
      (value "FE03-1")
      (footprint "eagle-import:FE03-1")
      (libsource (lib "eagle-import") (part "FE03-1"))
    )
    (comp (ref "X16")
      (value "FE02-10.8MM")
      (footprint "eagle-import:FE02-1")
      (libsource (lib "eagle-import") (part "FE02-10.8MM"))
    )
    (comp (ref "X17")
      (value "FE02-10.8MM")
      (footprint "eagle-import:FE02-1")
      (libsource (lib "eagle-import") (part "FE02-10.8MM"))
    )
    (comp (ref "X18")
      (value "FE03-1")
      (footprint "eagle-import:FE03-1")
      (libsource (lib "eagle-import") (part "FE03-1"))
    )
    (comp (ref "D11")
      (value "SN74HC151N")
      (footprint "eagle-import:DIP16")
      (fields (field (name "MOUSER_PART_NUMBER") "595-SN74HC151N"))
      (libsource (lib "eagle-import") (part "SN74HC151N"))
    )
    (comp (ref "D12")
      (value "SN74HC151N")
      (footprint "eagle-import:DIP16")
      (fields (field (name "MOUSER_PART_NUMBER") "595-SN74HC151N"))
      (libsource (lib "eagle-import") (part "SN74HC151N"))
    )
    (comp (ref "D15")
      (value "74HC08N")
      (footprint "eagle-import:DIP14")
      (libsource (lib "eagle-import") (part "7408NHC"))
    )
    (comp (ref "D16")
      (value "74HC32N")
      (footprint "eagle-import:DIP14")
      (libsource (lib "eagle-import") (part "7432NHC"))
    )
    (comp (ref "D17")
      (value "74HC00N")
      (footprint "eagle-import:DIP14")
      (libsource (lib "eagle-import") (part "7400NHC"))
    )
    (comp (ref "D18")
      (value "74HC00N")
      (footprint "eagle-import:DIP14")
      (libsource (lib "eagle-import") (part "7400NHC"))
    )
    (comp (ref "D19")
      (value "74573N")
      (footprint "eagle-import:DIP20")
      (libsource (lib "eagle-import") (part "74573N"))
    )
    (comp (ref "IC3")
      (value "74HC595N")
      (footprint "eagle-import:DIP16")
      (libsource (lib "eagle-import") (part "74595NHC"))
    )
    (comp (ref "IC4")
      (value "74HC595N")
      (footprint "eagle-import:DIP16")
      (libsource (lib "eagle-import") (part "74595NHC"))
    )
    (comp (ref "D2")
      (value "ADC0820CCN")
      (footprint "eagle-import:DIL20")
      (fields
        (field (name "ARROW_PART_NUMBER") "ADC0820CCN/NOPB")
        (field (name "MOUSER_PART_NUMBER") "926-ADC0820CCN/NOPB")
      )
      (libsource (lib "eagle-import") (part "ADC0820CCN"))
    )
    (comp (ref "D3")
      (value "ADC0820CCN")
      (footprint "eagle-import:DIL20")
      (fields
        (field (name "ARROW_PART_NUMBER") "ADC0820CCN/NOPB")
        (field (name "MOUSER_PART_NUMBER") "926-ADC0820CCN/NOPB")
      )
      (libsource (lib "eagle-import") (part "ADC0820CCN"))
    )
    (comp (ref "D4")
      (value "SN74HC151N")
      (footprint "eagle-import:DIP16")
      (fields (field (name "MOUSER_PART_NUMBER") "595-SN74HC151N"))
      (libsource (lib "eagle-import") (part "SN74HC151N"))
    )
    (comp (ref "D5")
      (value "TLC7524CN")
      (footprint "eagle-import:DIL16")
      (fields (field (name "RS_PART_NUMBER") "0650087"))
      (libsource (lib "eagle-import") (part "TLC7524CN"))
    )
    (comp (ref "D10")
      (value "TLC7524CN")
      (footprint "eagle-import:DIL16")
      (fields (field (name "RS_PART_NUMBER") "0650087"))
      (libsource (lib "eagle-import") (part "TLC7524CN"))
    )
    (comp (ref "N1")
      (value "CD74HC4051E")
      (footprint "eagle-import:DIP16")
      (libsource (lib "eagle-import") (part "CD74HC4051E"))
    )
    (comp (ref "D6")
      (value "74HCT08N")
      (footprint "eagle-import:DIP14")
      (libsource (lib "eagle-import") (part "7408NHCT"))
    )
    (comp (ref "D7")
      (value "74HCT08N")
      (footprint "eagle-import:DIP14")
      (libsource (lib "eagle-import") (part "7408NHCT"))
    )
    (comp (ref "D8")
      (value "74HCT73N")
      (footprint "eagle-import:DIP14")
      (libsource (lib "eagle-import") (part "7473NHCT"))
    )
    (comp (ref "D9")
      (value "74HCT32N")
      (footprint "eagle-import:DIP14")
      (libsource (lib "eagle-import") (part "7432NHCT"))
    )
    (comp (ref "H34")
      (value "LED5MM")
      (footprint "eagle-import:LED5MM")
      (libsource (lib "eagle-import") (part "LED5MM"))
    )
    (comp (ref "R54")
      (value "R-EUSR1206")
      (footprint "eagle-import:R1206")
      (libsource (lib "eagle-import") (part "R-EUSR1206"))
    )
    (comp (ref "J1")
      (value "35RAPC2AH3")
      (footprint "eagle-import:35RAPC2AH3")
      (fields (field (name "MOUSER_PART_NUMBER") "502-35RAPC2AH3"))
      (libsource (lib "eagle-import") (part "35RAPC2AH3"))
    )
    (comp (ref "J2")
      (value "35RAPC2AH3")
      (footprint "eagle-import:35RAPC2AH3")
      (fields (field (name "MOUSER_PART_NUMBER") "502-35RAPC2AH3"))
      (libsource (lib "eagle-import") (part "35RAPC2AH3"))
    )
    (comp (ref "J3")
      (value "35RAPC2AH3")
      (footprint "eagle-import:35RAPC2AH3")
      (fields (field (name "MOUSER_PART_NUMBER") "502-35RAPC2AH3"))
      (libsource (lib "eagle-import") (part "35RAPC2AH3"))
    )
    (comp (ref "J4")
      (value "35RAPC2AH3")
      (footprint "eagle-import:35RAPC2AH3")
      (fields (field (name "MOUSER_PART_NUMBER") "502-35RAPC2AH3"))
      (libsource (lib "eagle-import") (part "35RAPC2AH3"))
    )
    (comp (ref "J5")
      (value "35RAPC2AH3")
      (footprint "eagle-import:35RAPC2AH3")
      (fields (field (name "MOUSER_PART_NUMBER") "502-35RAPC2AH3"))
      (libsource (lib "eagle-import") (part "35RAPC2AH3"))
    )
    (comp (ref "J6")
      (value "35RAPC2AH3")
      (footprint "eagle-import:35RAPC2AH3")
      (fields (field (name "MOUSER_PART_NUMBER") "502-35RAPC2AH3"))
      (libsource (lib "eagle-import") (part "35RAPC2AH3"))
    )
    (comp (ref "J7")
      (value "35RAPC2AH3")
      (footprint "eagle-import:35RAPC2AH3")
      (fields (field (name "MOUSER_PART_NUMBER") "502-35RAPC2AH3"))
      (libsource (lib "eagle-import") (part "35RAPC2AH3"))
    )
    (comp (ref "J8")
      (value "35RAPC2AH3")
      (footprint "eagle-import:35RAPC2AH3")
      (fields (field (name "MOUSER_PART_NUMBER") "502-35RAPC2AH3"))
      (libsource (lib "eagle-import") (part "35RAPC2AH3"))
    )
    (comp (ref "J9")
      (value "35RAPC2AH3")
      (footprint "eagle-import:35RAPC2AH3")
      (fields (field (name "MOUSER_PART_NUMBER") "502-35RAPC2AH3"))
      (libsource (lib "eagle-import") (part "35RAPC2AH3"))
    )
    (comp (ref "SV2")
      (value "MA08-1W")
      (footprint "eagle-import:MA08-1W")
      (libsource (lib "eagle-import") (part "MA08-1W"))
    )
    (comp (ref "SV4")
      (value "FE08-1")
      (footprint "eagle-import:FE08")
      (libsource (lib "eagle-import") (part "FE08-1"))
    )
    (comp (ref "V1")
      (value "1N4148-7")
      (footprint "eagle-import:DO35-7")
      (libsource (lib "eagle-import") (part "1N4148-7"))
    )
    (comp (ref "X19")
      (value "MA02-1W")
      (footprint "eagle-import:MA02-1W")
      (libsource (lib "eagle-import") (part "MA02-1W"))
    )
    (comp (ref "X20")
      (value "FE02-10.8MM")
      (footprint "eagle-import:FE02-1")
      (libsource (lib "eagle-import") (part "FE02-10.8MM"))
    )
    (comp (ref "D21")
      (value "74HCT73N")
      (footprint "eagle-import:DIP14")
      (libsource (lib "eagle-import") (part "7473NHCT"))
    )
    (comp (ref "H33")
      (value "LED5MM")
      (footprint "eagle-import:LED5MM")
      (libsource (lib "eagle-import") (part "LED5MM"))
    )
    (comp (ref "R42")
      (value "R-EUSR1206")
      (footprint "eagle-import:R1206")
      (libsource (lib "eagle-import") (part "R-EUSR1206"))
    )
    (comp (ref "R43")
      (value "R-EUSR1206")
      (footprint "eagle-import:R1206")
      (libsource (lib "eagle-import") (part "R-EUSR1206"))
    )
    (comp (ref "R44")
      (value "R-EUSR1206")
      (footprint "eagle-import:R1206")
      (libsource (lib "eagle-import") (part "R-EUSR1206"))
    )
    (comp (ref "R55")
      (value "R-EUSR1206")
      (footprint "eagle-import:R1206")
      (libsource (lib "eagle-import") (part "R-EUSR1206"))
    )
    (comp (ref "R56")
      (value "R-EUSR1206")
      (footprint "eagle-import:R1206")
      (libsource (lib "eagle-import") (part "R-EUSR1206"))
    )
    (comp (ref "R57")
      (value "R-EUSR1206")
      (footprint "eagle-import:R1206")
      (libsource (lib "eagle-import") (part "R-EUSR1206"))
    )
    (comp (ref "R58")
      (value "R-EUSR1206")
      (footprint "eagle-import:R1206")
      (libsource (lib "eagle-import") (part "R-EUSR1206"))
    )
    (comp (ref "R70")
      (value "R-EUSR1206")
      (footprint "eagle-import:R1206")
      (libsource (lib "eagle-import") (part "R-EUSR1206"))
    )
    (comp (ref "S1")
      (value "TSW1")
      (footprint "eagle-import:320-916")
      (libsource (lib "eagle-import") (part "TSW1"))
    )
    (comp (ref "S2")
      (value "TSW1")
      (footprint "eagle-import:320-916")
      (libsource (lib "eagle-import") (part "TSW1"))
    )
    (comp (ref "S3")
      (value "TSW1")
      (footprint "eagle-import:320-916")
      (libsource (lib "eagle-import") (part "TSW1"))
    )
    (comp (ref "S4")
      (value "TSW1")
      (footprint "eagle-import:320-916")
      (libsource (lib "eagle-import") (part "TSW1"))
    )
    (comp (ref "S5")
      (value "TSW1")
      (footprint "eagle-import:320-916")
      (libsource (lib "eagle-import") (part "TSW1"))
    )
    (comp (ref "S6")
      (value "TSW1")
      (footprint "eagle-import:320-916")
      (libsource (lib "eagle-import") (part "TSW1"))
    )
    (comp (ref "S7")
      (value "TSW1")
      (footprint "eagle-import:320-916")
      (libsource (lib "eagle-import") (part "TSW1"))
    )
    (comp (ref "S8")
      (value "TSW1")
      (footprint "eagle-import:320-916")
      (libsource (lib "eagle-import") (part "TSW1"))
    )
    (comp (ref "S9")
      (value "TASTE10-XX")
      (footprint "eagle-import:VERSTäRKER_B3F-10XX")
      (libsource (lib "eagle-import") (part "TASTE10-XX"))
    )
    (comp (ref "S10")
      (value "TASTE10-XX")
      (footprint "eagle-import:VERSTäRKER_B3F-10XX")
      (libsource (lib "eagle-import") (part "TASTE10-XX"))
    )
    (comp (ref "S11")
      (value "TASTE10-XX")
      (footprint "eagle-import:VERSTäRKER_B3F-10XX")
      (libsource (lib "eagle-import") (part "TASTE10-XX"))
    )
    (comp (ref "S12")
      (value "TASTE10-XX")
      (footprint "eagle-import:VERSTäRKER_B3F-10XX")
      (libsource (lib "eagle-import") (part "TASTE10-XX"))
    )
    (comp (ref "S13")
      (value "TASTE10-XX")
      (footprint "eagle-import:VERSTäRKER_B3F-10XX")
      (libsource (lib "eagle-import") (part "TASTE10-XX"))
    )
    (comp (ref "S14")
      (value "TASTE10-XX")
      (footprint "eagle-import:VERSTäRKER_B3F-10XX")
      (libsource (lib "eagle-import") (part "TASTE10-XX"))
    )
    (comp (ref "S15")
      (value "TASTE10-XX")
      (footprint "eagle-import:VERSTäRKER_B3F-10XX")
      (libsource (lib "eagle-import") (part "TASTE10-XX"))
    )
    (comp (ref "V9")
      (value "1N4148-7")
      (footprint "eagle-import:DO35-7")
      (libsource (lib "eagle-import") (part "1N4148-7"))
    )
    (comp (ref "H1")
      (value "gn")
      (footprint "eagle-import:LED5MM")
      (libsource (lib "eagle-import") (part "LED5MM"))
    )
    (comp (ref "H2")
      (value "gn")
      (footprint "eagle-import:LED5MM")
      (libsource (lib "eagle-import") (part "LED5MM"))
    )
    (comp (ref "H3")
      (value "gn")
      (footprint "eagle-import:LED5MM")
      (libsource (lib "eagle-import") (part "LED5MM"))
    )
    (comp (ref "H4")
      (value "gn")
      (footprint "eagle-import:LED5MM")
      (libsource (lib "eagle-import") (part "LED5MM"))
    )
    (comp (ref "H5")
      (value "gn")
      (footprint "eagle-import:LED5MM")
      (libsource (lib "eagle-import") (part "LED5MM"))
    )
    (comp (ref "H6")
      (value "gn")
      (footprint "eagle-import:LED5MM")
      (libsource (lib "eagle-import") (part "LED5MM"))
    )
    (comp (ref "H7")
      (value "gn")
      (footprint "eagle-import:LED5MM")
      (libsource (lib "eagle-import") (part "LED5MM"))
    )
    (comp (ref "H8")
      (value "gn")
      (footprint "eagle-import:LED5MM")
      (libsource (lib "eagle-import") (part "LED5MM"))
    )
    (comp (ref "H9")
      (value "rt")
      (footprint "eagle-import:LED5MM")
      (libsource (lib "eagle-import") (part "LED5MM"))
    )
    (comp (ref "H10")
      (value "rt")
      (footprint "eagle-import:LED5MM")
      (libsource (lib "eagle-import") (part "LED5MM"))
    )
    (comp (ref "H11")
      (value "rt")
      (footprint "eagle-import:LED5MM")
      (libsource (lib "eagle-import") (part "LED5MM"))
    )
    (comp (ref "H12")
      (value "rt")
      (footprint "eagle-import:LED5MM")
      (libsource (lib "eagle-import") (part "LED5MM"))
    )
    (comp (ref "H13")
      (value "rt")
      (footprint "eagle-import:LED5MM")
      (libsource (lib "eagle-import") (part "LED5MM"))
    )
    (comp (ref "H14")
      (value "rt")
      (footprint "eagle-import:LED5MM")
      (libsource (lib "eagle-import") (part "LED5MM"))
    )
    (comp (ref "H15")
      (value "rt")
      (footprint "eagle-import:LED5MM")
      (libsource (lib "eagle-import") (part "LED5MM"))
    )
    (comp (ref "H16")
      (value "rt")
      (footprint "eagle-import:LED5MM")
      (libsource (lib "eagle-import") (part "LED5MM"))
    )
    (comp (ref "H17")
      (value "rt")
      (footprint "eagle-import:LED3MM")
      (libsource (lib "eagle-import") (part "LED3MM"))
    )
    (comp (ref "H18")
      (value "rt")
      (footprint "eagle-import:LED3MM")
      (libsource (lib "eagle-import") (part "LED3MM"))
    )
    (comp (ref "H19")
      (value "rt")
      (footprint "eagle-import:LED3MM")
      (libsource (lib "eagle-import") (part "LED3MM"))
    )
    (comp (ref "H20")
      (value "rt")
      (footprint "eagle-import:LED3MM")
      (libsource (lib "eagle-import") (part "LED3MM"))
    )
    (comp (ref "H21")
      (value "rt")
      (footprint "eagle-import:LED3MM")
      (libsource (lib "eagle-import") (part "LED3MM"))
    )
    (comp (ref "H22")
      (value "rt")
      (footprint "eagle-import:LED3MM")
      (libsource (lib "eagle-import") (part "LED3MM"))
    )
    (comp (ref "H23")
      (value "rt")
      (footprint "eagle-import:LED3MM")
      (libsource (lib "eagle-import") (part "LED3MM"))
    )
    (comp (ref "H24")
      (value "rt")
      (footprint "eagle-import:LED3MM")
      (libsource (lib "eagle-import") (part "LED3MM"))
    )
    (comp (ref "H25")
      (value "rt")
      (footprint "eagle-import:LED3MM")
      (libsource (lib "eagle-import") (part "LED3MM"))
    )
    (comp (ref "H26")
      (value "rt")
      (footprint "eagle-import:LED3MM")
      (libsource (lib "eagle-import") (part "LED3MM"))
    )
    (comp (ref "H27")
      (value "rt")
      (footprint "eagle-import:LED3MM")
      (libsource (lib "eagle-import") (part "LED3MM"))
    )
    (comp (ref "H28")
      (value "rt")
      (footprint "eagle-import:LED3MM")
      (libsource (lib "eagle-import") (part "LED3MM"))
    )
    (comp (ref "H29")
      (value "rt")
      (footprint "eagle-import:LED3MM")
      (libsource (lib "eagle-import") (part "LED3MM"))
    )
    (comp (ref "H30")
      (value "rt")
      (footprint "eagle-import:LED3MM")
      (libsource (lib "eagle-import") (part "LED3MM"))
    )
    (comp (ref "H31")
      (value "rt")
      (footprint "eagle-import:LED3MM")
      (libsource (lib "eagle-import") (part "LED3MM"))
    )
    (comp (ref "H32")
      (value "rt")
      (footprint "eagle-import:LED3MM")
      (libsource (lib "eagle-import") (part "LED3MM"))
    )
    (comp (ref "N2")
      (value "CD74HC4051E")
      (footprint "eagle-import:DIP16")
      (libsource (lib "eagle-import") (part "CD74HC4051E"))
    )
    (comp (ref "R9")
      (value "1k")
      (footprint "eagle-import:0207_10")
      (libsource (lib "eagle-import") (part "R-EUS0207/10"))
    )
    (comp (ref "R10")
      (value "1k")
      (footprint "eagle-import:0207_10")
      (libsource (lib "eagle-import") (part "R-EUS0207/10"))
    )
    (comp (ref "R11")
      (value "1k")
      (footprint "eagle-import:0207_10")
      (libsource (lib "eagle-import") (part "R-EUS0207/10"))
    )
    (comp (ref "R12")
      (value "1k")
      (footprint "eagle-import:0207_10")
      (libsource (lib "eagle-import") (part "R-EUS0207/10"))
    )
    (comp (ref "R13")
      (value "1k")
      (footprint "eagle-import:0207_10")
      (libsource (lib "eagle-import") (part "R-EUS0207/10"))
    )
    (comp (ref "R14")
      (value "1k")
      (footprint "eagle-import:0207_10")
      (libsource (lib "eagle-import") (part "R-EUS0207/10"))
    )
    (comp (ref "R15")
      (value "1k")
      (footprint "eagle-import:0207_10")
      (libsource (lib "eagle-import") (part "R-EUS0207/10"))
    )
    (comp (ref "R16")
      (value "1k")
      (footprint "eagle-import:0207_10")
      (libsource (lib "eagle-import") (part "R-EUS0207/10"))
    )
    (comp (ref "R17")
      (value "1k")
      (footprint "eagle-import:0207_10")
      (libsource (lib "eagle-import") (part "R-EUS0207/10"))
    )
    (comp (ref "R26")
      (value "1k")
      (footprint "eagle-import:0207_10")
      (libsource (lib "eagle-import") (part "R-EUS0207/10"))
    )
    (comp (ref "R27")
      (value "1k")
      (footprint "eagle-import:0207_10")
      (libsource (lib "eagle-import") (part "R-EUS0207/10"))
    )
    (comp (ref "R28")
      (value "1k")
      (footprint "eagle-import:0207_10")
      (libsource (lib "eagle-import") (part "R-EUS0207/10"))
    )
    (comp (ref "R29")
      (value "1k")
      (footprint "eagle-import:0207_10")
      (libsource (lib "eagle-import") (part "R-EUS0207/10"))
    )
    (comp (ref "R30")
      (value "1k")
      (footprint "eagle-import:0207_10")
      (libsource (lib "eagle-import") (part "R-EUS0207/10"))
    )
    (comp (ref "R31")
      (value "1k")
      (footprint "eagle-import:0207_10")
      (libsource (lib "eagle-import") (part "R-EUS0207/10"))
    )
    (comp (ref "R32")
      (value "1k")
      (footprint "eagle-import:0207_10")
      (libsource (lib "eagle-import") (part "R-EUS0207/10"))
    )
    (comp (ref "R33")
      (value "1k")
      (footprint "eagle-import:0207_10")
      (libsource (lib "eagle-import") (part "R-EUS0207/10"))
    )
    (comp (ref "R34")
      (value "1k")
      (footprint "eagle-import:0207_10")
      (libsource (lib "eagle-import") (part "R-EUS0207/10"))
    )
    (comp (ref "R35")
      (value "1k")
      (footprint "eagle-import:0207_10")
      (libsource (lib "eagle-import") (part "R-EUS0207/10"))
    )
    (comp (ref "R36")
      (value "1k")
      (footprint "eagle-import:0207_10")
      (libsource (lib "eagle-import") (part "R-EUS0207/10"))
    )
    (comp (ref "R37")
      (value "1k")
      (footprint "eagle-import:0207_10")
      (libsource (lib "eagle-import") (part "R-EUS0207/10"))
    )
    (comp (ref "R38")
      (value "1k")
      (footprint "eagle-import:0207_10")
      (libsource (lib "eagle-import") (part "R-EUS0207/10"))
    )
    (comp (ref "R39")
      (value "1k")
      (footprint "eagle-import:0207_10")
      (libsource (lib "eagle-import") (part "R-EUS0207/10"))
    )
    (comp (ref "R40")
      (value "1k")
      (footprint "eagle-import:0207_10")
      (libsource (lib "eagle-import") (part "R-EUS0207/10"))
    )
    (comp (ref "R41")
      (value "1k")
      (footprint "eagle-import:0207_10")
      (libsource (lib "eagle-import") (part "R-EUS0207/10"))
    )
    (comp (ref "R45")
      (value "1k")
      (footprint "eagle-import:0207_10")
      (libsource (lib "eagle-import") (part "R-EUS0207/10"))
    )
    (comp (ref "R46")
      (value "1k")
      (footprint "eagle-import:0207_10")
      (libsource (lib "eagle-import") (part "R-EUS0207/10"))
    )
    (comp (ref "R47")
      (value "1k")
      (footprint "eagle-import:0207_10")
      (libsource (lib "eagle-import") (part "R-EUS0207/10"))
    )
    (comp (ref "R48")
      (value "1k")
      (footprint "eagle-import:0207_10")
      (libsource (lib "eagle-import") (part "R-EUS0207/10"))
    )
    (comp (ref "R49")
      (value "1k")
      (footprint "eagle-import:0207_10")
      (libsource (lib "eagle-import") (part "R-EUS0207/10"))
    )
    (comp (ref "R50")
      (value "1k")
      (footprint "eagle-import:0207_10")
      (libsource (lib "eagle-import") (part "R-EUS0207/10"))
    )
    (comp (ref "R51")
      (value "1k")
      (footprint "eagle-import:0207_10")
      (libsource (lib "eagle-import") (part "R-EUS0207/10"))
    )
  )
  (nets
    (net (code "1") (name "+5V") (class "Default")
      (node (ref "D1") (pin "11") (pinfunction "~{PL}_11") (pintype "input"))
      (node (ref "D1") (pin "4") (pinfunction "CPD_4") (pintype "input"))
      (node (ref "D10") (pin "14") (pinfunction "VDD_14") (pintype "power_in"))
      (node (ref "D11") (pin "16") (pinfunction "VCC_16") (pintype "bidirectional"))
      (node (ref "D12") (pin "16") (pinfunction "VCC_16") (pintype "bidirectional"))
      (node (ref "D13") (pin "14") (pinfunction "J_14") (pintype "input"))
      (node (ref "D13") (pin "3") (pinfunction "K_3") (pintype "input"))
      (node (ref "D2") (pin "12") (pinfunction "VREF(+)_12") (pintype "bidirectional"))
      (node (ref "D2") (pin "20") (pinfunction "VCC_20") (pintype "bidirectional"))
      (node (ref "D2") (pin "7") (pinfunction "MODE_7") (pintype "bidirectional"))
      (node (ref "D21") (pin "14") (pinfunction "J_14") (pintype "input"))
      (node (ref "D21") (pin "3") (pinfunction "K_3") (pintype "input"))
      (node (ref "D23") (pin "16") (pinfunction "VCC_16") (pintype "bidirectional"))
      (node (ref "D24") (pin "16") (pinfunction "VCC_16") (pintype "bidirectional"))
      (node (ref "D25") (pin "11") (pinfunction "~{PL}_11") (pintype "input"))
      (node (ref "D25") (pin "4") (pinfunction "CPD_4") (pintype "input"))
      (node (ref "D28") (pin "10") (pinfunction "K_10") (pintype "input"))
      (node (ref "D28") (pin "7") (pinfunction "J_7") (pintype "input"))
      (node (ref "D3") (pin "12") (pinfunction "VREF(+)_12") (pintype "bidirectional"))
      (node (ref "D3") (pin "20") (pinfunction "VCC_20") (pintype "bidirectional"))
      (node (ref "D3") (pin "7") (pinfunction "MODE_7") (pintype "bidirectional"))
      (node (ref "D4") (pin "16") (pinfunction "VCC_16") (pintype "bidirectional"))
      (node (ref "D5") (pin "14") (pinfunction "VDD_14") (pintype "power_in"))
      (node (ref "D8") (pin "14") (pinfunction "J_14") (pintype "input"))
      (node (ref "D8") (pin "3") (pinfunction "K_3") (pintype "input"))
      (node (ref "N1") (pin "16") (pinfunction "VCC_16") (pintype "power_in"))
      (node (ref "N1") (pin "6") (pinfunction "~{E}_6") (pintype "input"))
      (node (ref "N2") (pin "16") (pinfunction "VCC_16") (pintype "power_in"))
      (node (ref "N2") (pin "3") (pinfunction "COMOUT/INA_3") (pintype "bidirectional"))
      (node (ref "N2") (pin "6") (pinfunction "~{E}_6") (pintype "input"))
      (node (ref "N3") (pin "4") (pinfunction "R_4") (pintype "input"))
      (node (ref "N3") (pin "8") (pinfunction "V+_8") (pintype "power_in"))
      (node (ref "R52") (pin "2") (pinfunction "2_2") (pintype "passive"))
      (node (ref "S1") (pin "1") (pinfunction "O_1") (pintype "passive"))
      (node (ref "S10") (pin "3") (pinfunction "P_3") (pintype "passive"))
      (node (ref "S10") (pin "4") (pinfunction "P1_4") (pintype "passive"))
      (node (ref "S11") (pin "3") (pinfunction "P_3") (pintype "passive"))
      (node (ref "S11") (pin "4") (pinfunction "P1_4") (pintype "passive"))
      (node (ref "S12") (pin "3") (pinfunction "P_3") (pintype "passive"))
      (node (ref "S12") (pin "4") (pinfunction "P1_4") (pintype "passive"))
      (node (ref "S13") (pin "3") (pinfunction "P_3") (pintype "passive"))
      (node (ref "S13") (pin "4") (pinfunction "P1_4") (pintype "passive"))
      (node (ref "S14") (pin "3") (pinfunction "P_3") (pintype "passive"))
      (node (ref "S14") (pin "4") (pinfunction "P1_4") (pintype "passive"))
      (node (ref "S15") (pin "3") (pinfunction "P_3") (pintype "passive"))
      (node (ref "S15") (pin "4") (pinfunction "P1_4") (pintype "passive"))
      (node (ref "S2") (pin "1") (pinfunction "O_1") (pintype "passive"))
      (node (ref "S3") (pin "1") (pinfunction "O_1") (pintype "passive"))
      (node (ref "S4") (pin "1") (pinfunction "O_1") (pintype "passive"))
      (node (ref "S5") (pin "1") (pinfunction "O_1") (pintype "passive"))
      (node (ref "S6") (pin "1") (pinfunction "O_1") (pintype "passive"))
      (node (ref "S7") (pin "1") (pinfunction "O_1") (pintype "passive"))
      (node (ref "S8") (pin "1") (pinfunction "O_1") (pintype "passive"))
      (node (ref "S9") (pin "3") (pinfunction "P_3") (pintype "passive"))
      (node (ref "S9") (pin "4") (pinfunction "P1_4") (pintype "passive"))
    )
    (net (code "2") (name "+12V") (class "Default")
      (node (ref "N4") (pin "8") (pinfunction "V+_8") (pintype "power_in"))
      (node (ref "R60") (pin "1") (pinfunction "1_1") (pintype "passive"))
      (node (ref "R61") (pin "1") (pinfunction "1_1") (pintype "passive"))
      (node (ref "R63") (pin "2") (pinfunction "2_2") (pintype "passive"))
      (node (ref "R69") (pin "2") (pinfunction "2_2") (pintype "passive"))
    )
    (net (code "3") (name "1.33V") (class "Default")
      (node (ref "R1") (pin "3") (pinfunction "2_3") (pintype "passive"))
      (node (ref "R2") (pin "3") (pinfunction "2_3") (pintype "passive"))
      (node (ref "R3") (pin "3") (pinfunction "2_3") (pintype "passive"))
      (node (ref "R4") (pin "3") (pinfunction "2_3") (pintype "passive"))
      (node (ref "R5") (pin "3") (pinfunction "2_3") (pintype "passive"))
      (node (ref "R6") (pin "3") (pinfunction "2_3") (pintype "passive"))
      (node (ref "R7") (pin "3") (pinfunction "2_3") (pintype "passive"))
      (node (ref "R8") (pin "3") (pinfunction "2_3") (pintype "passive"))
      (node (ref "X1") (pin "1") (pinfunction "2_1") (pintype "passive"))
      (node (ref "X2") (pin "2") (pinfunction "2_2") (pintype "passive"))
    )
    (net (code "4") (name "1_SHIFT") (class "Default")
      (node (ref "D16") (pin "2") (pinfunction "B_2") (pintype "input"))
      (node (ref "R55") (pin "2") (pinfunction "2_2") (pintype "passive"))
      (node (ref "S11") (pin "1") (pinfunction "S_1") (pintype "passive"))
      (node (ref "S11") (pin "2") (pinfunction "S1_2") (pintype "passive"))
    )
    (net (code "5") (name "2_MODE_EN") (class "Default")
      (node (ref "D8") (pin "1") (pinfunction "~{CLK}_1") (pintype "input"))
      (node (ref "R70") (pin "2") (pinfunction "2_2") (pintype "passive"))
      (node (ref "S15") (pin "1") (pinfunction "S_1") (pintype "passive"))
      (node (ref "S15") (pin "2") (pinfunction "S1_2") (pintype "passive"))
    )
    (net (code "6") (name "3_LE") (class "Default")
      (node (ref "D15") (pin "2") (pinfunction "B_2") (pintype "input"))
      (node (ref "D16") (pin "4") (pinfunction "A_4") (pintype "input"))
      (node (ref "R56") (pin "2") (pinfunction "2_2") (pintype "passive"))
      (node (ref "S12") (pin "1") (pinfunction "S_1") (pintype "passive"))
      (node (ref "S12") (pin "2") (pinfunction "S1_2") (pintype "passive"))
    )
    (net (code "7") (name "4_PAUSE") (class "Default")
      (node (ref "D13") (pin "1") (pinfunction "~{CLK}_1") (pintype "input"))
      (node (ref "D21") (pin "12") (pinfunction "Q_12") (pintype "output"))
      (node (ref "D22") (pin "2") (pinfunction "B_2") (pintype "input"))
    )
    (net (code "8") (name "5_RESET") (class "Default")
      (node (ref "D14") (pin "1") (pinfunction "A_1") (pintype "input"))
      (node (ref "R42") (pin "2") (pinfunction "2_2") (pintype "passive"))
      (node (ref "V1") (pin "C") (pinfunction "C_C") (pintype "passive"))
      (node (ref "V9") (pin "C") (pinfunction "C_C") (pintype "passive"))
      (node (ref "X19") (pin "1") (pinfunction "2_1") (pintype "passive"))
      (node (ref "X20") (pin "2") (pinfunction "2_2") (pintype "passive"))
    )
    (net (code "9") (name "7_CH_MODE") (class "Default")
      (node (ref "D28") (pin "5") (pinfunction "~{CLK}_5") (pintype "input"))
      (node (ref "D29") (pin "1") (pinfunction "~{CLK}_1") (pintype "input"))
      (node (ref "R57") (pin "2") (pinfunction "2_2") (pintype "passive"))
      (node (ref "S13") (pin "1") (pinfunction "S_1") (pintype "passive"))
      (node (ref "S13") (pin "2") (pinfunction "S1_2") (pintype "passive"))
    )
    (net (code "10") (name "11_CLRR") (class "Default")
      (node (ref "IC3") (pin "10") (pinfunction "~{MR}_10") (pintype "bidirectional"))
      (node (ref "IC4") (pin "10") (pinfunction "~{MR}_10") (pintype "bidirectional"))
      (node (ref "R58") (pin "2") (pinfunction "2_2") (pintype "passive"))
      (node (ref "S14") (pin "1") (pinfunction "S_1") (pintype "passive"))
      (node (ref "S14") (pin "2") (pinfunction "S1_2") (pintype "passive"))
    )
    (net (code "11") (name "ADSR_BUFFER") (class "Default")
      (node (ref "C5") (pin "1") (pinfunction "1_1") (pintype "passive"))
      (node (ref "N4") (pin "6") (pinfunction "THR_6") (pintype "input"))
      (node (ref "N5") (pin "3") (pinfunction "P_3") (pintype "bidirectional"))
      (node (ref "V2") (pin "A") (pinfunction "A_A") (pintype "passive"))
      (node (ref "V3") (pin "C") (pinfunction "C_C") (pintype "passive"))
      (node (ref "V4") (pin "A") (pinfunction "A_A") (pintype "passive"))
    )
    (net (code "12") (name "ADSR_CTRL") (class "Default")
      (node (ref "C4") (pin "1") (pinfunction "1_1") (pintype "passive"))
      (node (ref "N4") (pin "4") (pinfunction "R_4") (pintype "input"))
      (node (ref "R60") (pin "2") (pinfunction "2_2") (pintype "passive"))
      (node (ref "R62") (pin "2") (pinfunction "2_2") (pintype "passive"))
      (node (ref "R67") (pin "2") (pinfunction "2_2") (pintype "passive"))
      (node (ref "V7") (pin "1") (pinfunction "C_1") (pintype "passive"))
    )
    (net (code "13") (name "ADSR_IN") (class "Default")
      (node (ref "R59") (pin "2") (pinfunction "2_2") (pintype "passive"))
    )
    (net (code "14") (name "ADSR_OUT") (class "Default")
      (node (ref "N5") (pin "1") (pinfunction "O_1") (pintype "bidirectional"))
      (node (ref "N5") (pin "2") (pinfunction "N_2") (pintype "bidirectional"))
    )
    (net (code "15") (name "ADSR_TRIG") (class "Default")
      (node (ref "N4") (pin "2") (pinfunction "TR_2") (pintype "input"))
      (node (ref "R63") (pin "1") (pinfunction "1_1") (pintype "passive"))
      (node (ref "V6") (pin "1") (pinfunction "C_1") (pintype "passive"))
    )
    (net (code "16") (name "ATTACK_A") (class "Default")
      (node (ref "R22") (pin "3") (pinfunction "2_3") (pintype "passive"))
      (node (ref "R66") (pin "1") (pinfunction "1_1") (pintype "passive"))
      (node (ref "X16") (pin "2") (pinfunction "2_2") (pintype "passive"))
      (node (ref "X3") (pin "1") (pinfunction "2_1") (pintype "passive"))
    )
    (net (code "17") (name "ATTACK_B") (class "Default")
      (node (ref "R22") (pin "1") (pinfunction "1_1") (pintype "passive"))
      (node (ref "R22") (pin "2") (pinfunction "3_2") (pintype "passive"))
      (node (ref "V3") (pin "A") (pinfunction "A_A") (pintype "passive"))
      (node (ref "X16") (pin "1") (pinfunction "1_1") (pintype "passive"))
      (node (ref "X3") (pin "2") (pinfunction "3_2") (pintype "passive"))
    )
    (net (code "18") (name "BPM-POT_A") (class "Default")
      (node (ref "R18") (pin "3") (pinfunction "2_3") (pintype "passive"))
      (node (ref "R53") (pin "1") (pinfunction "1_1") (pintype "passive"))
      (node (ref "X12") (pin "2") (pinfunction "2_2") (pintype "passive"))
      (node (ref "X7") (pin "1") (pinfunction "2_1") (pintype "passive"))
    )
    (net (code "19") (name "BPM-POT_B") (class "Default")
      (node (ref "C1") (pin "1") (pinfunction "1_1") (pintype "passive"))
      (node (ref "R18") (pin "1") (pinfunction "1_1") (pintype "passive"))
      (node (ref "R18") (pin "2") (pinfunction "3_2") (pintype "passive"))
      (node (ref "X12") (pin "1") (pinfunction "1_1") (pintype "passive"))
      (node (ref "X7") (pin "2") (pinfunction "3_2") (pintype "passive"))
    )
    (net (code "20") (name "C_IND1") (class "Default")
      (node (ref "J1") (pin "5") (pinfunction "5_5") (pintype "bidirectional"))
      (node (ref "N2") (pin "13") (pinfunction "CHANNELIN/OUTA0_13") (pintype "bidirectional"))
      (node (ref "R17") (pin "2") (pinfunction "2_2") (pintype "passive"))
      (node (ref "SV2") (pin "1") (pinfunction "1_1") (pintype "passive"))
      (node (ref "SV4") (pin "8") (pinfunction "8_8") (pintype "passive"))
    )
    (net (code "21") (name "C_IND2") (class "Default")
      (node (ref "J2") (pin "5") (pinfunction "5_5") (pintype "bidirectional"))
      (node (ref "N2") (pin "14") (pinfunction "CHANNELIN/OUTA1_14") (pintype "bidirectional"))
      (node (ref "R45") (pin "2") (pinfunction "2_2") (pintype "passive"))
      (node (ref "SV2") (pin "2") (pinfunction "2_2") (pintype "passive"))
      (node (ref "SV4") (pin "7") (pinfunction "7_7") (pintype "passive"))
    )
    (net (code "22") (name "C_IND3") (class "Default")
      (node (ref "J3") (pin "5") (pinfunction "5_5") (pintype "bidirectional"))
      (node (ref "N2") (pin "15") (pinfunction "CHANNELIN/OUTA2_15") (pintype "bidirectional"))
      (node (ref "R46") (pin "2") (pinfunction "2_2") (pintype "passive"))
      (node (ref "SV2") (pin "3") (pinfunction "3_3") (pintype "passive"))
      (node (ref "SV4") (pin "6") (pinfunction "6_6") (pintype "passive"))
    )
    (net (code "23") (name "C_IND4") (class "Default")
      (node (ref "J4") (pin "5") (pinfunction "5_5") (pintype "bidirectional"))
      (node (ref "N2") (pin "12") (pinfunction "CHANNELIN/OUTA3_12") (pintype "bidirectional"))
      (node (ref "R47") (pin "2") (pinfunction "2_2") (pintype "passive"))
      (node (ref "SV2") (pin "4") (pinfunction "4_4") (pintype "passive"))
      (node (ref "SV4") (pin "5") (pinfunction "5_5") (pintype "passive"))
    )
    (net (code "24") (name "C_IND5") (class "Default")
      (node (ref "J5") (pin "5") (pinfunction "5_5") (pintype "bidirectional"))
      (node (ref "N2") (pin "1") (pinfunction "CHANNELIN/OUTA4_1") (pintype "bidirectional"))
      (node (ref "R48") (pin "2") (pinfunction "2_2") (pintype "passive"))
      (node (ref "SV2") (pin "5") (pinfunction "5_5") (pintype "passive"))
      (node (ref "SV4") (pin "4") (pinfunction "4_4") (pintype "passive"))
    )
    (net (code "25") (name "C_IND6") (class "Default")
      (node (ref "J6") (pin "5") (pinfunction "5_5") (pintype "bidirectional"))
      (node (ref "N2") (pin "5") (pinfunction "CHANNELIN/OUTA5_5") (pintype "bidirectional"))
      (node (ref "R49") (pin "2") (pinfunction "2_2") (pintype "passive"))
      (node (ref "SV2") (pin "6") (pinfunction "6_6") (pintype "passive"))
      (node (ref "SV4") (pin "3") (pinfunction "3_3") (pintype "passive"))
    )
    (net (code "26") (name "C_IND7") (class "Default")
      (node (ref "J7") (pin "5") (pinfunction "5_5") (pintype "bidirectional"))
      (node (ref "N2") (pin "2") (pinfunction "CHANNELIN/OUTA6_2") (pintype "bidirectional"))
      (node (ref "R50") (pin "2") (pinfunction "2_2") (pintype "passive"))
      (node (ref "SV2") (pin "7") (pinfunction "7_7") (pintype "passive"))
      (node (ref "SV4") (pin "2") (pinfunction "2_2") (pintype "passive"))
    )
    (net (code "27") (name "C_IND8") (class "Default")
      (node (ref "J8") (pin "5") (pinfunction "5_5") (pintype "bidirectional"))
      (node (ref "N2") (pin "4") (pinfunction "CHANNELIN/OUTA7_4") (pintype "bidirectional"))
      (node (ref "R51") (pin "2") (pinfunction "2_2") (pintype "passive"))
      (node (ref "SV2") (pin "8") (pinfunction "8_8") (pintype "passive"))
      (node (ref "SV4") (pin "1") (pinfunction "1_1") (pintype "passive"))
    )
    (net (code "28") (name "D0") (class "Default")
      (node (ref "D6") (pin "2") (pinfunction "B_2") (pintype "input"))
      (node (ref "D7") (pin "2") (pinfunction "B_2") (pintype "input"))
    )
    (net (code "29") (name "D0_IN") (class "Default")
      (node (ref "D3") (pin "5") (pinfunction "DB3_5") (pintype "bidirectional"))
    )
    (net (code "30") (name "D0_KF") (class "Default")
      (node (ref "D11") (pin "11") (pinfunction "A_11") (pintype "bidirectional"))
      (node (ref "D12") (pin "11") (pinfunction "A_11") (pintype "bidirectional"))
      (node (ref "D19") (pin "2") (pinfunction "1D_2") (pintype "bidirectional"))
      (node (ref "D7") (pin "3") (pinfunction "Y_3") (pintype "output"))
    )
    (net (code "31") (name "D0_OUT") (class "Default")
      (node (ref "D10") (pin "8") (pinfunction "DB3_8") (pintype "input"))
      (node (ref "D19") (pin "19") (pinfunction "1Q_19") (pintype "bidirectional"))
      (node (ref "D9") (pin "3") (pinfunction "Y_3") (pintype "output"))
    )
    (net (code "32") (name "D1") (class "Default")
      (node (ref "D6") (pin "5") (pinfunction "B_5") (pintype "input"))
      (node (ref "D7") (pin "5") (pinfunction "B_5") (pintype "input"))
    )
    (net (code "33") (name "D1_IN") (class "Default")
      (node (ref "D3") (pin "14") (pinfunction "DB4_14") (pintype "bidirectional"))
    )
    (net (code "34") (name "D1_KF") (class "Default")
      (node (ref "D11") (pin "10") (pinfunction "B_10") (pintype "bidirectional"))
      (node (ref "D12") (pin "10") (pinfunction "B_10") (pintype "bidirectional"))
      (node (ref "D19") (pin "3") (pinfunction "2D_3") (pintype "bidirectional"))
      (node (ref "D7") (pin "6") (pinfunction "Y_6") (pintype "output"))
    )
    (net (code "35") (name "D1_OUT") (class "Default")
      (node (ref "D10") (pin "7") (pinfunction "DB4_7") (pintype "input"))
      (node (ref "D19") (pin "18") (pinfunction "2Q_18") (pintype "bidirectional"))
      (node (ref "D9") (pin "6") (pinfunction "Y_6") (pintype "output"))
    )
    (net (code "36") (name "D2") (class "Default")
      (node (ref "D6") (pin "9") (pinfunction "B_9") (pintype "input"))
      (node (ref "D7") (pin "9") (pinfunction "B_9") (pintype "input"))
    )
    (net (code "37") (name "D2_IN") (class "Default")
      (node (ref "D3") (pin "15") (pinfunction "DB5_15") (pintype "bidirectional"))
    )
    (net (code "38") (name "D2_KF") (class "Default")
      (node (ref "D11") (pin "9") (pinfunction "C_9") (pintype "bidirectional"))
      (node (ref "D12") (pin "9") (pinfunction "C_9") (pintype "bidirectional"))
      (node (ref "D19") (pin "4") (pinfunction "3D_4") (pintype "bidirectional"))
      (node (ref "D7") (pin "8") (pinfunction "Y_8") (pintype "output"))
    )
    (net (code "39") (name "D2_OUT") (class "Default")
      (node (ref "D10") (pin "6") (pinfunction "DB5_6") (pintype "input"))
      (node (ref "D19") (pin "17") (pinfunction "3Q_17") (pintype "bidirectional"))
      (node (ref "D9") (pin "8") (pinfunction "Y_8") (pintype "output"))
    )
    (net (code "40") (name "D3") (class "Default")
      (node (ref "D6") (pin "12") (pinfunction "B_12") (pintype "input"))
      (node (ref "D7") (pin "12") (pinfunction "B_12") (pintype "input"))
    )
    (net (code "41") (name "D3_IN") (class "Default")
      (node (ref "D3") (pin "16") (pinfunction "DB6_16") (pintype "bidirectional"))
    )
    (net (code "42") (name "D3_KF") (class "Default")
      (node (ref "D17") (pin "10") (pinfunction "A_10") (pintype "input"))
      (node (ref "D17") (pin "4") (pinfunction "A_4") (pintype "input"))
      (node (ref "D17") (pin "5") (pinfunction "B_5") (pintype "input"))
      (node (ref "D19") (pin "5") (pinfunction "4D_5") (pintype "bidirectional"))
      (node (ref "D7") (pin "11") (pinfunction "Y_11") (pintype "output"))
    )
    (net (code "43") (name "D3_OUT") (class "Default")
      (node (ref "D10") (pin "5") (pinfunction "DB6_5") (pintype "input"))
      (node (ref "D19") (pin "16") (pinfunction "4Q_16") (pintype "bidirectional"))
      (node (ref "D9") (pin "11") (pinfunction "Y_11") (pintype "output"))
    )
    (net (code "44") (name "DECAY_A") (class "Default")
      (node (ref "R23") (pin "3") (pinfunction "2_3") (pintype "passive"))
      (node (ref "V4") (pin "C") (pinfunction "C_C") (pintype "passive"))
      (node (ref "X4") (pin "1") (pinfunction "2_1") (pintype "passive"))
      (node (ref "X6") (pin "2") (pinfunction "2_2") (pintype "passive"))
    )
    (net (code "45") (name "DECAY_B") (class "Default")
      (node (ref "R23") (pin "1") (pinfunction "1_1") (pintype "passive"))
      (node (ref "R23") (pin "2") (pinfunction "3_2") (pintype "passive"))
      (node (ref "R68") (pin "1") (pinfunction "1_1") (pintype "passive"))
      (node (ref "X4") (pin "2") (pinfunction "3_2") (pintype "passive"))
      (node (ref "X6") (pin "1") (pinfunction "1_1") (pintype "passive"))
    )
    (net (code "46") (name "DS") (class "Default")
      (node (ref "D18") (pin "11") (pinfunction "Y_11") (pintype "output"))
      (node (ref "IC4") (pin "14") (pinfunction "DS_14") (pintype "bidirectional"))
    )
    (net (code "47") (name "GATE_DIV_A") (class "Default")
      (node (ref "D13") (pin "9") (pinfunction "Q_9") (pintype "output"))
    )
    (net (code "48") (name "GATE_DIV_B") (class "Default")
      (node (ref "D26") (pin "12") (pinfunction "Q_12") (pintype "output"))
    )
    (net (code "49") (name "GATE_DIV_C") (class "Default")
      (node (ref "D26") (pin "9") (pinfunction "Q_9") (pintype "output"))
    )
    (net (code "50") (name "GND") (class "Default")
      (node (ref "C1") (pin "2") (pinfunction "2_2") (pintype "passive"))
      (node (ref "C2") (pin "2") (pinfunction "2_2") (pintype "passive"))
      (node (ref "C3") (pin "2") (pinfunction "2_2") (pintype "passive"))
      (node (ref "C5") (pin "2") (pinfunction "2_2") (pintype "passive"))
      (node (ref "D1") (pin "1") (pinfunction "D1_1") (pintype "input"))
      (node (ref "D1") (pin "10") (pinfunction "D2_10") (pintype "input"))
      (node (ref "D1") (pin "15") (pinfunction "D0_15") (pintype "input"))
      (node (ref "D1") (pin "9") (pinfunction "D3_9") (pintype "input"))
      (node (ref "D10") (pin "10") (pinfunction "DB1_10") (pintype "input"))
      (node (ref "D10") (pin "11") (pinfunction "DB0_11") (pintype "input"))
      (node (ref "D10") (pin "3") (pinfunction "GND_3") (pintype "power_in"))
      (node (ref "D10") (pin "9") (pinfunction "DB2_9") (pintype "input"))
      (node (ref "D11") (pin "7") (pinfunction "~{G}_7") (pintype "bidirectional"))
      (node (ref "D11") (pin "8") (pinfunction "GND_8") (pintype "bidirectional"))
      (node (ref "D12") (pin "7") (pinfunction "~{G}_7") (pintype "bidirectional"))
      (node (ref "D12") (pin "8") (pinfunction "GND_8") (pintype "bidirectional"))
      (node (ref "D19") (pin "1") (pinfunction "~{OE}_1") (pintype "bidirectional"))
      (node (ref "D19") (pin "6") (pinfunction "5D_6") (pintype "bidirectional"))
      (node (ref "D19") (pin "7") (pinfunction "6D_7") (pintype "bidirectional"))
      (node (ref "D19") (pin "8") (pinfunction "7D_8") (pintype "bidirectional"))
      (node (ref "D19") (pin "9") (pinfunction "8D_9") (pintype "bidirectional"))
      (node (ref "D2") (pin "10") (pinfunction "GND_10") (pintype "bidirectional"))
      (node (ref "D2") (pin "11") (pinfunction "VREF(-)_11") (pintype "bidirectional"))
      (node (ref "D2") (pin "13") (pinfunction "~{CS}_13") (pintype "input"))
      (node (ref "D2") (pin "8") (pinfunction "~{RD}_8") (pintype "bidirectional"))
      (node (ref "D23") (pin "7") (pinfunction "~{G}_7") (pintype "bidirectional"))
      (node (ref "D23") (pin "8") (pinfunction "GND_8") (pintype "bidirectional"))
      (node (ref "D24") (pin "7") (pinfunction "~{G}_7") (pintype "bidirectional"))
      (node (ref "D24") (pin "8") (pinfunction "GND_8") (pintype "bidirectional"))
      (node (ref "D25") (pin "14") (pinfunction "MR_14") (pintype "input"))
      (node (ref "D3") (pin "10") (pinfunction "GND_10") (pintype "bidirectional"))
      (node (ref "D3") (pin "11") (pinfunction "VREF(-)_11") (pintype "bidirectional"))
      (node (ref "D3") (pin "13") (pinfunction "~{CS}_13") (pintype "input"))
      (node (ref "D3") (pin "8") (pinfunction "~{RD}_8") (pintype "bidirectional"))
      (node (ref "D4") (pin "7") (pinfunction "~{G}_7") (pintype "bidirectional"))
      (node (ref "D4") (pin "8") (pinfunction "GND_8") (pintype "bidirectional"))
      (node (ref "D5") (pin "10") (pinfunction "DB1_10") (pintype "input"))
      (node (ref "D5") (pin "11") (pinfunction "DB0_11") (pintype "input"))
      (node (ref "D5") (pin "3") (pinfunction "GND_3") (pintype "power_in"))
      (node (ref "D5") (pin "8") (pinfunction "DB3_8") (pintype "input"))
      (node (ref "D5") (pin "9") (pinfunction "DB2_9") (pintype "input"))
      (node (ref "H1") (pin "K") (pinfunction "C_K") (pintype "passive"))
      (node (ref "H10") (pin "K") (pinfunction "C_K") (pintype "passive"))
      (node (ref "H11") (pin "K") (pinfunction "C_K") (pintype "passive"))
      (node (ref "H12") (pin "K") (pinfunction "C_K") (pintype "passive"))
      (node (ref "H13") (pin "K") (pinfunction "C_K") (pintype "passive"))
      (node (ref "H14") (pin "K") (pinfunction "C_K") (pintype "passive"))
      (node (ref "H15") (pin "K") (pinfunction "C_K") (pintype "passive"))
      (node (ref "H16") (pin "K") (pinfunction "C_K") (pintype "passive"))
      (node (ref "H17") (pin "K") (pinfunction "C_K") (pintype "passive"))
      (node (ref "H18") (pin "K") (pinfunction "C_K") (pintype "passive"))
      (node (ref "H19") (pin "K") (pinfunction "C_K") (pintype "passive"))
      (node (ref "H2") (pin "K") (pinfunction "C_K") (pintype "passive"))
      (node (ref "H20") (pin "K") (pinfunction "C_K") (pintype "passive"))
      (node (ref "H21") (pin "K") (pinfunction "C_K") (pintype "passive"))
      (node (ref "H22") (pin "K") (pinfunction "C_K") (pintype "passive"))
      (node (ref "H23") (pin "K") (pinfunction "C_K") (pintype "passive"))
      (node (ref "H24") (pin "K") (pinfunction "C_K") (pintype "passive"))
      (node (ref "H25") (pin "K") (pinfunction "C_K") (pintype "passive"))
      (node (ref "H26") (pin "K") (pinfunction "C_K") (pintype "passive"))
      (node (ref "H27") (pin "K") (pinfunction "C_K") (pintype "passive"))
      (node (ref "H28") (pin "K") (pinfunction "C_K") (pintype "passive"))
      (node (ref "H29") (pin "K") (pinfunction "C_K") (pintype "passive"))
      (node (ref "H3") (pin "K") (pinfunction "C_K") (pintype "passive"))
      (node (ref "H30") (pin "K") (pinfunction "C_K") (pintype "passive"))
      (node (ref "H31") (pin "K") (pinfunction "C_K") (pintype "passive"))
      (node (ref "H32") (pin "K") (pinfunction "C_K") (pintype "passive"))
      (node (ref "H33") (pin "K") (pinfunction "C_K") (pintype "passive"))
      (node (ref "H34") (pin "K") (pinfunction "C_K") (pintype "passive"))
      (node (ref "H4") (pin "K") (pinfunction "C_K") (pintype "passive"))
      (node (ref "H5") (pin "K") (pinfunction "C_K") (pintype "passive"))
      (node (ref "H6") (pin "K") (pinfunction "C_K") (pintype "passive"))
      (node (ref "H7") (pin "K") (pinfunction "C_K") (pintype "passive"))
      (node (ref "H8") (pin "K") (pinfunction "C_K") (pintype "passive"))
      (node (ref "H9") (pin "K") (pinfunction "C_K") (pintype "passive"))
      (node (ref "IC3") (pin "13") (pinfunction "~{OE}_13") (pintype "bidirectional"))
      (node (ref "IC4") (pin "13") (pinfunction "~{OE}_13") (pintype "bidirectional"))
      (node (ref "J1") (pin "1") (pinfunction "1_1") (pintype "bidirectional"))
      (node (ref "J2") (pin "1") (pinfunction "1_1") (pintype "bidirectional"))
      (node (ref "J3") (pin "1") (pinfunction "1_1") (pintype "bidirectional"))
      (node (ref "J4") (pin "1") (pinfunction "1_1") (pintype "bidirectional"))
      (node (ref "J5") (pin "1") (pinfunction "1_1") (pintype "bidirectional"))
      (node (ref "J6") (pin "1") (pinfunction "1_1") (pintype "bidirectional"))
      (node (ref "J7") (pin "1") (pinfunction "1_1") (pintype "bidirectional"))
      (node (ref "J8") (pin "1") (pinfunction "1_1") (pintype "bidirectional"))
      (node (ref "J9") (pin "1") (pinfunction "1_1") (pintype "bidirectional"))
      (node (ref "N1") (pin "7") (pinfunction "VEE_7") (pintype "power_in"))
      (node (ref "N1") (pin "8") (pinfunction "GND_8") (pintype "power_in"))
      (node (ref "N2") (pin "7") (pinfunction "VEE_7") (pintype "power_in"))
      (node (ref "N2") (pin "8") (pinfunction "GND_8") (pintype "power_in"))
      (node (ref "N3") (pin "1") (pinfunction "GND_1") (pintype "power_in"))
      (node (ref "N4") (pin "1") (pinfunction "GND_1") (pintype "power_in"))
      (node (ref "R1") (pin "1") (pinfunction "1_1") (pintype "passive"))
      (node (ref "R2") (pin "1") (pinfunction "1_1") (pintype "passive"))
      (node (ref "R3") (pin "1") (pinfunction "1_1") (pintype "passive"))
      (node (ref "R4") (pin "1") (pinfunction "1_1") (pintype "passive"))
      (node (ref "R42") (pin "1") (pinfunction "1_1") (pintype "passive"))
      (node (ref "R43") (pin "1") (pinfunction "1_1") (pintype "passive"))
      (node (ref "R5") (pin "1") (pinfunction "1_1") (pintype "passive"))
      (node (ref "R55") (pin "1") (pinfunction "1_1") (pintype "passive"))
      (node (ref "R56") (pin "1") (pinfunction "1_1") (pintype "passive"))
      (node (ref "R57") (pin "1") (pinfunction "1_1") (pintype "passive"))
      (node (ref "R58") (pin "1") (pinfunction "1_1") (pintype "passive"))
      (node (ref "R6") (pin "1") (pinfunction "1_1") (pintype "passive"))
      (node (ref "R7") (pin "1") (pinfunction "1_1") (pintype "passive"))
      (node (ref "R70") (pin "1") (pinfunction "1_1") (pintype "passive"))
      (node (ref "R8") (pin "1") (pinfunction "1_1") (pintype "passive"))
      (node (ref "S1") (pin "3") (pinfunction "S_3") (pintype "passive"))
      (node (ref "S2") (pin "3") (pinfunction "S_3") (pintype "passive"))
      (node (ref "S3") (pin "3") (pinfunction "S_3") (pintype "passive"))
      (node (ref "S4") (pin "3") (pinfunction "S_3") (pintype "passive"))
      (node (ref "S5") (pin "3") (pinfunction "S_3") (pintype "passive"))
      (node (ref "S6") (pin "3") (pinfunction "S_3") (pintype "passive"))
      (node (ref "S7") (pin "3") (pinfunction "S_3") (pintype "passive"))
      (node (ref "S8") (pin "3") (pinfunction "S_3") (pintype "passive"))
      (node (ref "V10") (pin "A") (pinfunction "A_A") (pintype "passive"))
      (node (ref "V5") (pin "3") (pinfunction "E_3") (pintype "passive"))
      (node (ref "V6") (pin "3") (pinfunction "E_3") (pintype "passive"))
      (node (ref "V7") (pin "3") (pinfunction "E_3") (pintype "passive"))
      (node (ref "V8") (pin "A") (pinfunction "A_A") (pintype "passive"))
      (node (ref "X1") (pin "2") (pinfunction "3_2") (pintype "passive"))
      (node (ref "X19") (pin "2") (pinfunction "3_2") (pintype "passive"))
      (node (ref "X2") (pin "1") (pinfunction "1_1") (pintype "passive"))
      (node (ref "X20") (pin "1") (pinfunction "1_1") (pintype "passive"))
    )
    (net (code "51") (name "HF_CLK") (class "Default")
      (node (ref "D10") (pin "13") (pinfunction "~{WR}_13") (pintype "input"))
      (node (ref "D15") (pin "1") (pinfunction "A_1") (pintype "input"))
      (node (ref "D15") (pin "4") (pinfunction "A_4") (pintype "input"))
      (node (ref "D2") (pin "6") (pinfunction "~{WR}/RDY_6") (pintype "bidirectional"))
      (node (ref "D3") (pin "6") (pinfunction "~{WR}/RDY_6") (pintype "bidirectional"))
      (node (ref "D5") (pin "13") (pinfunction "~{WR}_13") (pintype "input"))
    )
    (net (code "52") (name "KF0") (class "Default")
      (node (ref "D9") (pin "2") (pinfunction "B_2") (pintype "input"))
    )
    (net (code "53") (name "KF1") (class "Default")
      (node (ref "D9") (pin "5") (pinfunction "B_5") (pintype "input"))
    )
    (net (code "54") (name "KF2") (class "Default")
      (node (ref "D9") (pin "9") (pinfunction "B_9") (pintype "input"))
    )
    (net (code "55") (name "KF3") (class "Default")
      (node (ref "D9") (pin "12") (pinfunction "B_12") (pintype "input"))
    )
    (net (code "56") (name "LF_CLK") (class "Default")
      (node (ref "D22") (pin "1") (pinfunction "A_1") (pintype "input"))
    )
    (net (code "57") (name "LOAD_SR") (class "Default")
      (node (ref "D18") (pin "4") (pinfunction "A_4") (pintype "input"))
    )
    (net (code "58") (name "MAN_LE") (class "Default")
      (node (ref "D16") (pin "5") (pinfunction "B_5") (pintype "input"))
    )
    (net (code "59") (name "MODE_EN") (class "Default")
      (node (ref "D6") (pin "1") (pinfunction "A_1") (pintype "input"))
      (node (ref "D6") (pin "10") (pinfunction "A_10") (pintype "input"))
      (node (ref "D6") (pin "13") (pinfunction "A_13") (pintype "input"))
      (node (ref "D6") (pin "4") (pinfunction "A_4") (pintype "input"))
      (node (ref "D8") (pin "12") (pinfunction "Q_12") (pintype "output"))
      (node (ref "R54") (pin "2") (pinfunction "2_2") (pintype "passive"))
    )
    (net (code "60") (name "Net-(C4-Pad2)") (class "Default")
      (node (ref "C4") (pin "2") (pinfunction "2_2") (pintype "passive"))
      (node (ref "R65") (pin "2") (pinfunction "2_2") (pintype "passive"))
      (node (ref "V8") (pin "C") (pinfunction "C_C") (pintype "passive"))
    )
    (net (code "61") (name "Net-(D1A-CPU)") (class "Default")
      (node (ref "D1") (pin "5") (pinfunction "CPU_5") (pintype "input"))
      (node (ref "D20") (pin "3") (pinfunction "Y_3") (pintype "output"))
    )
    (net (code "62") (name "Net-(D2-DB4)") (class "Default")
      (node (ref "D2") (pin "14") (pinfunction "DB4_14") (pintype "bidirectional"))
      (node (ref "D5") (pin "7") (pinfunction "DB4_7") (pintype "input"))
    )
    (net (code "63") (name "Net-(D2-DB5)") (class "Default")
      (node (ref "D2") (pin "15") (pinfunction "DB5_15") (pintype "bidirectional"))
      (node (ref "D5") (pin "6") (pinfunction "DB5_6") (pintype "input"))
    )
    (net (code "64") (name "Net-(D2-DB6)") (class "Default")
      (node (ref "D2") (pin "16") (pinfunction "DB6_16") (pintype "bidirectional"))
      (node (ref "D5") (pin "5") (pinfunction "DB6_5") (pintype "input"))
    )
    (net (code "65") (name "Net-(D2-DB7)") (class "Default")
      (node (ref "D2") (pin "17") (pinfunction "DB7_17") (pintype "bidirectional"))
      (node (ref "D5") (pin "4") (pinfunction "DB7_4") (pintype "input"))
    )
    (net (code "66") (name "Net-(D6B-Y)") (class "Default")
      (node (ref "D6") (pin "3") (pinfunction "Y_3") (pintype "output"))
      (node (ref "D9") (pin "1") (pinfunction "A_1") (pintype "input"))
    )
    (net (code "67") (name "Net-(D6C-Y)") (class "Default")
      (node (ref "D6") (pin "6") (pinfunction "Y_6") (pintype "output"))
      (node (ref "D9") (pin "4") (pinfunction "A_4") (pintype "input"))
    )
    (net (code "68") (name "Net-(D6D-Y)") (class "Default")
      (node (ref "D6") (pin "8") (pinfunction "Y_8") (pintype "output"))
      (node (ref "D9") (pin "10") (pinfunction "A_10") (pintype "input"))
    )
    (net (code "69") (name "Net-(D6E-Y)") (class "Default")
      (node (ref "D6") (pin "11") (pinfunction "Y_11") (pintype "output"))
      (node (ref "D9") (pin "13") (pinfunction "A_13") (pintype "input"))
    )
    (net (code "70") (name "Net-(D13B-Q)") (class "Default")
      (node (ref "D13") (pin "12") (pinfunction "Q_12") (pintype "output"))
      (node (ref "D20") (pin "1") (pinfunction "A_1") (pintype "input"))
    )
    (net (code "71") (name "Net-(D14B-B)") (class "Default")
      (node (ref "D1") (pin "7") (pinfunction "Q3_7") (pintype "output"))
      (node (ref "D14") (pin "2") (pinfunction "B_2") (pintype "input"))
    )
    (net (code "72") (name "Net-(D14B-Y)") (class "Default")
      (node (ref "D1") (pin "14") (pinfunction "MR_14") (pintype "input"))
      (node (ref "D14") (pin "3") (pinfunction "Y_3") (pintype "output"))
    )
    (net (code "73") (name "Net-(D15B-Y)") (class "Default")
      (node (ref "D15") (pin "3") (pinfunction "Y_3") (pintype "output"))
      (node (ref "D16") (pin "1") (pinfunction "A_1") (pintype "input"))
    )
    (net (code "74") (name "Net-(D15C-B)") (class "Default")
      (node (ref "D15") (pin "5") (pinfunction "B_5") (pintype "input"))
      (node (ref "D17") (pin "11") (pinfunction "Y_11") (pintype "output"))
    )
    (net (code "75") (name "Net-(D15C-Y)") (class "Default")
      (node (ref "D15") (pin "6") (pinfunction "Y_6") (pintype "output"))
      (node (ref "D19") (pin "11") (pinfunction "LE_11") (pintype "bidirectional"))
    )
    (net (code "76") (name "Net-(D16C-Y)") (class "Default")
      (node (ref "D16") (pin "6") (pinfunction "Y_6") (pintype "output"))
      (node (ref "D18") (pin "1") (pinfunction "A_1") (pintype "input"))
      (node (ref "D18") (pin "2") (pinfunction "B_2") (pintype "input"))
      (node (ref "D18") (pin "5") (pinfunction "B_5") (pintype "input"))
    )
    (net (code "77") (name "Net-(D17B-B)") (class "Default")
      (node (ref "D17") (pin "2") (pinfunction "B_2") (pintype "input"))
      (node (ref "D17") (pin "6") (pinfunction "Y_6") (pintype "output"))
    )
    (net (code "78") (name "Net-(D17B-Y)") (class "Default")
      (node (ref "D17") (pin "13") (pinfunction "A_13") (pintype "input"))
      (node (ref "D17") (pin "3") (pinfunction "Y_3") (pintype "output"))
    )
    (net (code "79") (name "Net-(D17D-Y)") (class "Default")
      (node (ref "D17") (pin "12") (pinfunction "B_12") (pintype "input"))
      (node (ref "D17") (pin "8") (pinfunction "Y_8") (pintype "output"))
    )
    (net (code "80") (name "Net-(D18B-Y)") (class "Default")
      (node (ref "D18") (pin "10") (pinfunction "A_10") (pintype "input"))
      (node (ref "D18") (pin "3") (pinfunction "Y_3") (pintype "output"))
    )
    (net (code "81") (name "Net-(D18C-Y)") (class "Default")
      (node (ref "D18") (pin "13") (pinfunction "A_13") (pintype "input"))
      (node (ref "D18") (pin "6") (pinfunction "Y_6") (pintype "output"))
    )
    (net (code "82") (name "Net-(D18D-Y)") (class "Default")
      (node (ref "D18") (pin "12") (pinfunction "B_12") (pintype "input"))
      (node (ref "D18") (pin "8") (pinfunction "Y_8") (pintype "output"))
    )
    (net (code "83") (name "Net-(D20B-B)") (class "Default")
      (node (ref "D20") (pin "2") (pinfunction "B_2") (pintype "input"))
      (node (ref "D22") (pin "3") (pinfunction "Y_3") (pintype "output"))
    )
    (net (code "84") (name "Net-(D21B-~{CLK})") (class "Default")
      (node (ref "D21") (pin "1") (pinfunction "~{CLK}_1") (pintype "input"))
      (node (ref "R43") (pin "2") (pinfunction "2_2") (pintype "passive"))
      (node (ref "S10") (pin "1") (pinfunction "S_1") (pintype "passive"))
      (node (ref "S10") (pin "2") (pinfunction "S1_2") (pintype "passive"))
    )
    (net (code "85") (name "Net-(D21B-~{Q})") (class "Default")
      (node (ref "D21") (pin "13") (pinfunction "~{Q}_13") (pintype "output"))
      (node (ref "R44") (pin "2") (pinfunction "2_2") (pintype "passive"))
    )
    (net (code "86") (name "Net-(D23-D1)") (class "Default")
      (node (ref "D23") (pin "3") (pinfunction "D1_3") (pintype "bidirectional"))
      (node (ref "D24") (pin "3") (pinfunction "D1_3") (pintype "bidirectional"))
      (node (ref "D25") (pin "3") (pinfunction "Q0_3") (pintype "output"))
    )
    (net (code "87") (name "Net-(D23-D2)") (class "Default")
      (node (ref "D23") (pin "2") (pinfunction "D2_2") (pintype "bidirectional"))
      (node (ref "D24") (pin "2") (pinfunction "D2_2") (pintype "bidirectional"))
      (node (ref "D25") (pin "2") (pinfunction "Q1_2") (pintype "output"))
    )
    (net (code "88") (name "Net-(D23-D3)") (class "Default")
      (node (ref "D23") (pin "1") (pinfunction "D3_1") (pintype "bidirectional"))
      (node (ref "D24") (pin "1") (pinfunction "D3_1") (pintype "bidirectional"))
      (node (ref "D25") (pin "6") (pinfunction "Q2_6") (pintype "output"))
    )
    (net (code "89") (name "Net-(D23-D4)") (class "Default")
      (node (ref "D23") (pin "15") (pinfunction "D4_15") (pintype "bidirectional"))
      (node (ref "D24") (pin "15") (pinfunction "D4_15") (pintype "bidirectional"))
      (node (ref "D25") (pin "7") (pinfunction "Q3_7") (pintype "output"))
    )
    (net (code "90") (name "Net-(H1-PadA)") (class "Default")
      (node (ref "H1") (pin "A") (pinfunction "A_A") (pintype "passive"))
      (node (ref "R9") (pin "1") (pinfunction "1_1") (pintype "passive"))
    )
    (net (code "91") (name "Net-(H2-PadA)") (class "Default")
      (node (ref "H2") (pin "A") (pinfunction "A_A") (pintype "passive"))
      (node (ref "R10") (pin "1") (pinfunction "1_1") (pintype "passive"))
    )
    (net (code "92") (name "Net-(H3-PadA)") (class "Default")
      (node (ref "H3") (pin "A") (pinfunction "A_A") (pintype "passive"))
      (node (ref "R11") (pin "1") (pinfunction "1_1") (pintype "passive"))
    )
    (net (code "93") (name "Net-(H4-PadA)") (class "Default")
      (node (ref "H4") (pin "A") (pinfunction "A_A") (pintype "passive"))
      (node (ref "R12") (pin "1") (pinfunction "1_1") (pintype "passive"))
    )
    (net (code "94") (name "Net-(H5-PadA)") (class "Default")
      (node (ref "H5") (pin "A") (pinfunction "A_A") (pintype "passive"))
      (node (ref "R13") (pin "1") (pinfunction "1_1") (pintype "passive"))
    )
    (net (code "95") (name "Net-(H6-PadA)") (class "Default")
      (node (ref "H6") (pin "A") (pinfunction "A_A") (pintype "passive"))
      (node (ref "R14") (pin "1") (pinfunction "1_1") (pintype "passive"))
    )
    (net (code "96") (name "Net-(H7-PadA)") (class "Default")
      (node (ref "H7") (pin "A") (pinfunction "A_A") (pintype "passive"))
      (node (ref "R15") (pin "1") (pinfunction "1_1") (pintype "passive"))
    )
    (net (code "97") (name "Net-(H8-PadA)") (class "Default")
      (node (ref "H8") (pin "A") (pinfunction "A_A") (pintype "passive"))
      (node (ref "R16") (pin "1") (pinfunction "1_1") (pintype "passive"))
    )
    (net (code "98") (name "Net-(H9-PadA)") (class "Default")
      (node (ref "H9") (pin "A") (pinfunction "A_A") (pintype "passive"))
      (node (ref "R17") (pin "1") (pinfunction "1_1") (pintype "passive"))
    )
    (net (code "99") (name "Net-(H10-PadA)") (class "Default")
      (node (ref "H10") (pin "A") (pinfunction "A_A") (pintype "passive"))
      (node (ref "R45") (pin "1") (pinfunction "1_1") (pintype "passive"))
    )
    (net (code "100") (name "Net-(H11-PadA)") (class "Default")
      (node (ref "H11") (pin "A") (pinfunction "A_A") (pintype "passive"))
      (node (ref "R46") (pin "1") (pinfunction "1_1") (pintype "passive"))
    )
    (net (code "101") (name "Net-(H12-PadA)") (class "Default")
      (node (ref "H12") (pin "A") (pinfunction "A_A") (pintype "passive"))
      (node (ref "R47") (pin "1") (pinfunction "1_1") (pintype "passive"))
    )
    (net (code "102") (name "Net-(H13-PadA)") (class "Default")
      (node (ref "H13") (pin "A") (pinfunction "A_A") (pintype "passive"))
      (node (ref "R48") (pin "1") (pinfunction "1_1") (pintype "passive"))
    )
    (net (code "103") (name "Net-(H14-PadA)") (class "Default")
      (node (ref "H14") (pin "A") (pinfunction "A_A") (pintype "passive"))
      (node (ref "R49") (pin "1") (pinfunction "1_1") (pintype "passive"))
    )
    (net (code "104") (name "Net-(H15-PadA)") (class "Default")
      (node (ref "H15") (pin "A") (pinfunction "A_A") (pintype "passive"))
      (node (ref "R50") (pin "1") (pinfunction "1_1") (pintype "passive"))
    )
    (net (code "105") (name "Net-(H16-PadA)") (class "Default")
      (node (ref "H16") (pin "A") (pinfunction "A_A") (pintype "passive"))
      (node (ref "R51") (pin "1") (pinfunction "1_1") (pintype "passive"))
    )
    (net (code "106") (name "Net-(H17-PadA)") (class "Default")
      (node (ref "H17") (pin "A") (pinfunction "A_A") (pintype "passive"))
      (node (ref "R26") (pin "1") (pinfunction "1_1") (pintype "passive"))
    )
    (net (code "107") (name "Net-(H18-PadA)") (class "Default")
      (node (ref "H18") (pin "A") (pinfunction "A_A") (pintype "passive"))
      (node (ref "R27") (pin "1") (pinfunction "1_1") (pintype "passive"))
    )
    (net (code "108") (name "Net-(H19-PadA)") (class "Default")
      (node (ref "H19") (pin "A") (pinfunction "A_A") (pintype "passive"))
      (node (ref "R28") (pin "1") (pinfunction "1_1") (pintype "passive"))
    )
    (net (code "109") (name "Net-(H20-PadA)") (class "Default")
      (node (ref "H20") (pin "A") (pinfunction "A_A") (pintype "passive"))
      (node (ref "R29") (pin "1") (pinfunction "1_1") (pintype "passive"))
    )
    (net (code "110") (name "Net-(H21-PadA)") (class "Default")
      (node (ref "H21") (pin "A") (pinfunction "A_A") (pintype "passive"))
      (node (ref "R30") (pin "1") (pinfunction "1_1") (pintype "passive"))
    )
    (net (code "111") (name "Net-(H22-PadA)") (class "Default")
      (node (ref "H22") (pin "A") (pinfunction "A_A") (pintype "passive"))
      (node (ref "R31") (pin "1") (pinfunction "1_1") (pintype "passive"))
    )
    (net (code "112") (name "Net-(H23-PadA)") (class "Default")
      (node (ref "H23") (pin "A") (pinfunction "A_A") (pintype "passive"))
      (node (ref "R32") (pin "1") (pinfunction "1_1") (pintype "passive"))
    )
    (net (code "113") (name "Net-(H24-PadA)") (class "Default")
      (node (ref "H24") (pin "A") (pinfunction "A_A") (pintype "passive"))
      (node (ref "R33") (pin "1") (pinfunction "1_1") (pintype "passive"))
    )
    (net (code "114") (name "Net-(H25-PadA)") (class "Default")
      (node (ref "H25") (pin "A") (pinfunction "A_A") (pintype "passive"))
      (node (ref "R34") (pin "1") (pinfunction "1_1") (pintype "passive"))
    )
    (net (code "115") (name "Net-(H26-PadA)") (class "Default")
      (node (ref "H26") (pin "A") (pinfunction "A_A") (pintype "passive"))
      (node (ref "R35") (pin "1") (pinfunction "1_1") (pintype "passive"))
    )
    (net (code "116") (name "Net-(H27-PadA)") (class "Default")
      (node (ref "H27") (pin "A") (pinfunction "A_A") (pintype "passive"))
      (node (ref "R36") (pin "1") (pinfunction "1_1") (pintype "passive"))
    )
    (net (code "117") (name "Net-(H28-PadA)") (class "Default")
      (node (ref "H28") (pin "A") (pinfunction "A_A") (pintype "passive"))
      (node (ref "R37") (pin "1") (pinfunction "1_1") (pintype "passive"))
    )
    (net (code "118") (name "Net-(H29-PadA)") (class "Default")
      (node (ref "H29") (pin "A") (pinfunction "A_A") (pintype "passive"))
      (node (ref "R38") (pin "1") (pinfunction "1_1") (pintype "passive"))
    )
    (net (code "119") (name "Net-(H30-PadA)") (class "Default")
      (node (ref "H30") (pin "A") (pinfunction "A_A") (pintype "passive"))
      (node (ref "R39") (pin "1") (pinfunction "1_1") (pintype "passive"))
    )
    (net (code "120") (name "Net-(H31-PadA)") (class "Default")
      (node (ref "H31") (pin "A") (pinfunction "A_A") (pintype "passive"))
      (node (ref "R40") (pin "1") (pinfunction "1_1") (pintype "passive"))
    )
    (net (code "121") (name "Net-(H32-PadA)") (class "Default")
      (node (ref "H32") (pin "A") (pinfunction "A_A") (pintype "passive"))
      (node (ref "R41") (pin "1") (pinfunction "1_1") (pintype "passive"))
    )
    (net (code "122") (name "Net-(H33-PadA)") (class "Default")
      (node (ref "H33") (pin "A") (pinfunction "A_A") (pintype "passive"))
      (node (ref "R44") (pin "1") (pinfunction "1_1") (pintype "passive"))
    )
    (net (code "123") (name "Net-(H34-PadA)") (class "Default")
      (node (ref "H34") (pin "A") (pinfunction "A_A") (pintype "passive"))
      (node (ref "R54") (pin "1") (pinfunction "1_1") (pintype "passive"))
    )
    (net (code "124") (name "Net-(IC3A-DS)") (class "Default")
      (node (ref "IC3") (pin "14") (pinfunction "DS_14") (pintype "bidirectional"))
      (node (ref "IC4") (pin "9") (pinfunction "Q7'_9") (pintype "bidirectional"))
    )
    (net (code "125") (name "Net-(J9-Pad5)") (class "Default")
      (node (ref "J9") (pin "5") (pinfunction "5_5") (pintype "bidirectional"))
      (node (ref "V1") (pin "A") (pinfunction "A_A") (pintype "passive"))
    )
    (net (code "126") (name "Net-(N3-CV)") (class "Default")
      (node (ref "C2") (pin "1") (pinfunction "1_1") (pintype "passive"))
      (node (ref "N3") (pin "5") (pinfunction "CV_5") (pintype "input"))
    )
    (net (code "127") (name "Net-(N3-DIS)") (class "Default")
      (node (ref "N3") (pin "7") (pinfunction "DIS_7") (pintype "input"))
      (node (ref "R52") (pin "1") (pinfunction "1_1") (pintype "passive"))
      (node (ref "R53") (pin "2") (pinfunction "2_2") (pintype "passive"))
    )
    (net (code "128") (name "Net-(N3-THR)") (class "Default")
      (node (ref "N3") (pin "2") (pinfunction "TR_2") (pintype "input"))
      (node (ref "N3") (pin "6") (pinfunction "THR_6") (pintype "input"))
    )
    (net (code "129") (name "Net-(N4-CV)") (class "Default")
      (node (ref "C3") (pin "1") (pinfunction "1_1") (pintype "passive"))
      (node (ref "N4") (pin "5") (pinfunction "CV_5") (pintype "input"))
    )
    (net (code "130") (name "Net-(N4-Q)") (class "Default")
      (node (ref "N4") (pin "3") (pinfunction "Q_3") (pintype "output"))
      (node (ref "R66") (pin "2") (pinfunction "2_2") (pintype "passive"))
    )
    (net (code "131") (name "Net-(N5B-N)") (class "Default")
      (node (ref "N5") (pin "6") (pinfunction "N_6") (pintype "bidirectional"))
      (node (ref "N5") (pin "7") (pinfunction "O_7") (pintype "bidirectional"))
      (node (ref "R68") (pin "2") (pinfunction "2_2") (pintype "passive"))
    )
    (net (code "132") (name "Net-(R19-2)") (class "Default")
      (node (ref "R19") (pin "3") (pinfunction "2_3") (pintype "passive"))
      (node (ref "X8") (pin "1") (pinfunction "1_1") (pintype "passive"))
    )
    (net (code "133") (name "Net-(R19-3)") (class "Default")
      (node (ref "R19") (pin "2") (pinfunction "3_2") (pintype "passive"))
      (node (ref "X8") (pin "2") (pinfunction "2_2") (pintype "passive"))
    )
    (net (code "134") (name "Net-(R19-Pad1)") (class "Default")
      (node (ref "R19") (pin "1") (pinfunction "1_1") (pintype "passive"))
      (node (ref "X8") (pin "3") (pinfunction "3_3") (pintype "passive"))
    )
    (net (code "135") (name "Net-(S9-S)") (class "Default")
      (node (ref "S9") (pin "1") (pinfunction "S_1") (pintype "passive"))
      (node (ref "S9") (pin "2") (pinfunction "S1_2") (pintype "passive"))
      (node (ref "V9") (pin "A") (pinfunction "A_A") (pintype "passive"))
    )
    (net (code "136") (name "Net-(V5-B)") (class "Default")
      (node (ref "R59") (pin "1") (pinfunction "1_1") (pintype "passive"))
      (node (ref "R62") (pin "1") (pinfunction "1_1") (pintype "passive"))
      (node (ref "V10") (pin "C") (pinfunction "C_C") (pintype "passive"))
      (node (ref "V5") (pin "2") (pinfunction "B_2") (pintype "passive"))
    )
    (net (code "137") (name "Net-(V5-C)") (class "Default")
      (node (ref "R61") (pin "2") (pinfunction "2_2") (pintype "passive"))
      (node (ref "R64") (pin "2") (pinfunction "2_2") (pintype "passive"))
      (node (ref "V5") (pin "1") (pinfunction "C_1") (pintype "passive"))
    )
    (net (code "138") (name "Net-(V6-B)") (class "Default")
      (node (ref "R65") (pin "1") (pinfunction "1_1") (pintype "passive"))
      (node (ref "V6") (pin "2") (pinfunction "B_2") (pintype "passive"))
    )
    (net (code "139") (name "Net-(V7-B)") (class "Default")
      (node (ref "R64") (pin "1") (pinfunction "1_1") (pintype "passive"))
      (node (ref "V7") (pin "2") (pinfunction "B_2") (pintype "passive"))
    )
    (net (code "140") (name "PORTA-POT_A") (class "Default")
      (node (ref "R20") (pin "3") (pinfunction "2_3") (pintype "passive"))
      (node (ref "X11") (pin "2") (pinfunction "2_2") (pintype "passive"))
      (node (ref "X9") (pin "1") (pinfunction "2_1") (pintype "passive"))
    )
    (net (code "141") (name "PORTA-POT_B") (class "Default")
      (node (ref "R20") (pin "1") (pinfunction "1_1") (pintype "passive"))
      (node (ref "R20") (pin "2") (pinfunction "3_2") (pintype "passive"))
      (node (ref "X11") (pin "1") (pinfunction "1_1") (pintype "passive"))
      (node (ref "X9") (pin "2") (pinfunction "3_2") (pintype "passive"))
    )
    (net (code "142") (name "Q0_MODE") (class "Default")
      (node (ref "D28") (pin "9") (pinfunction "Q_9") (pintype "output"))
      (node (ref "D29") (pin "14") (pinfunction "J_14") (pintype "input"))
      (node (ref "D29") (pin "3") (pinfunction "K_3") (pintype "input"))
    )
    (net (code "143") (name "Q1_MODE") (class "Default")
      (node (ref "D29") (pin "12") (pinfunction "Q_12") (pintype "output"))
    )
    (net (code "144") (name "QA") (class "Default")
      (node (ref "D1") (pin "3") (pinfunction "Q0_3") (pintype "output"))
      (node (ref "D4") (pin "11") (pinfunction "A_11") (pintype "bidirectional"))
      (node (ref "N1") (pin "11") (pinfunction "ADDRESSSELECTS0_11") (pintype "input"))
      (node (ref "N2") (pin "11") (pinfunction "ADDRESSSELECTS0_11") (pintype "input"))
    )
    (net (code "145") (name "QB") (class "Default")
      (node (ref "D1") (pin "2") (pinfunction "Q1_2") (pintype "output"))
      (node (ref "D4") (pin "10") (pinfunction "B_10") (pintype "bidirectional"))
      (node (ref "N1") (pin "10") (pinfunction "ADDRESSSELECTS1_10") (pintype "input"))
      (node (ref "N2") (pin "10") (pinfunction "ADDRESSSELECTS1_10") (pintype "input"))
    )
    (net (code "146") (name "QC") (class "Default")
      (node (ref "D1") (pin "6") (pinfunction "Q2_6") (pintype "output"))
      (node (ref "D4") (pin "9") (pinfunction "C_9") (pintype "bidirectional"))
      (node (ref "N1") (pin "9") (pinfunction "ADDRESSSELECTS2_9") (pintype "input"))
      (node (ref "N2") (pin "9") (pinfunction "ADDRESSSELECTS2_9") (pintype "input"))
    )
    (net (code "147") (name "RELEASE_A") (class "Default")
      (node (ref "R25") (pin "3") (pinfunction "2_3") (pintype "passive"))
      (node (ref "R67") (pin "1") (pinfunction "1_1") (pintype "passive"))
      (node (ref "X13") (pin "1") (pinfunction "2_1") (pintype "passive"))
      (node (ref "X14") (pin "2") (pinfunction "2_2") (pintype "passive"))
    )
    (net (code "148") (name "RELEASE_B") (class "Default")
      (node (ref "R25") (pin "1") (pinfunction "1_1") (pintype "passive"))
      (node (ref "R25") (pin "2") (pinfunction "3_2") (pintype "passive"))
      (node (ref "V2") (pin "C") (pinfunction "C_C") (pintype "passive"))
      (node (ref "X13") (pin "2") (pinfunction "3_2") (pintype "passive"))
      (node (ref "X14") (pin "1") (pinfunction "1_1") (pintype "passive"))
    )
    (net (code "149") (name "SR0") (class "Default")
      (node (ref "D12") (pin "4") (pinfunction "D0_4") (pintype "bidirectional"))
      (node (ref "IC4") (pin "15") (pinfunction "Q0_15") (pintype "bidirectional"))
      (node (ref "R26") (pin "2") (pinfunction "2_2") (pintype "passive"))
    )
    (net (code "150") (name "SR1") (class "Default")
      (node (ref "D12") (pin "3") (pinfunction "D1_3") (pintype "bidirectional"))
      (node (ref "IC4") (pin "1") (pinfunction "Q1_1") (pintype "bidirectional"))
      (node (ref "R27") (pin "2") (pinfunction "2_2") (pintype "passive"))
    )
    (net (code "151") (name "SR2") (class "Default")
      (node (ref "D12") (pin "2") (pinfunction "D2_2") (pintype "bidirectional"))
      (node (ref "IC4") (pin "2") (pinfunction "Q2_2") (pintype "bidirectional"))
      (node (ref "R28") (pin "2") (pinfunction "2_2") (pintype "passive"))
    )
    (net (code "152") (name "SR3") (class "Default")
      (node (ref "D12") (pin "1") (pinfunction "D3_1") (pintype "bidirectional"))
      (node (ref "IC4") (pin "3") (pinfunction "Q3_3") (pintype "bidirectional"))
      (node (ref "R29") (pin "2") (pinfunction "2_2") (pintype "passive"))
    )
    (net (code "153") (name "SR4") (class "Default")
      (node (ref "D12") (pin "15") (pinfunction "D4_15") (pintype "bidirectional"))
      (node (ref "IC4") (pin "4") (pinfunction "Q4_4") (pintype "bidirectional"))
      (node (ref "R30") (pin "2") (pinfunction "2_2") (pintype "passive"))
    )
    (net (code "154") (name "SR5") (class "Default")
      (node (ref "D12") (pin "14") (pinfunction "D5_14") (pintype "bidirectional"))
      (node (ref "IC4") (pin "5") (pinfunction "Q5_5") (pintype "bidirectional"))
      (node (ref "R31") (pin "2") (pinfunction "2_2") (pintype "passive"))
    )
    (net (code "155") (name "SR6") (class "Default")
      (node (ref "D12") (pin "13") (pinfunction "D6_13") (pintype "bidirectional"))
      (node (ref "IC4") (pin "6") (pinfunction "Q6_6") (pintype "bidirectional"))
      (node (ref "R32") (pin "2") (pinfunction "2_2") (pintype "passive"))
    )
    (net (code "156") (name "SR7") (class "Default")
      (node (ref "D12") (pin "12") (pinfunction "D7_12") (pintype "bidirectional"))
      (node (ref "IC4") (pin "7") (pinfunction "Q7_7") (pintype "bidirectional"))
      (node (ref "R33") (pin "2") (pinfunction "2_2") (pintype "passive"))
    )
    (net (code "157") (name "SR8") (class "Default")
      (node (ref "D11") (pin "4") (pinfunction "D0_4") (pintype "bidirectional"))
      (node (ref "IC3") (pin "15") (pinfunction "Q0_15") (pintype "bidirectional"))
      (node (ref "R34") (pin "2") (pinfunction "2_2") (pintype "passive"))
    )
    (net (code "158") (name "SR9") (class "Default")
      (node (ref "D11") (pin "3") (pinfunction "D1_3") (pintype "bidirectional"))
      (node (ref "IC3") (pin "1") (pinfunction "Q1_1") (pintype "bidirectional"))
      (node (ref "R35") (pin "2") (pinfunction "2_2") (pintype "passive"))
    )
    (net (code "159") (name "SR10") (class "Default")
      (node (ref "D11") (pin "2") (pinfunction "D2_2") (pintype "bidirectional"))
      (node (ref "IC3") (pin "2") (pinfunction "Q2_2") (pintype "bidirectional"))
      (node (ref "R36") (pin "2") (pinfunction "2_2") (pintype "passive"))
    )
    (net (code "160") (name "SR11") (class "Default")
      (node (ref "D11") (pin "1") (pinfunction "D3_1") (pintype "bidirectional"))
      (node (ref "IC3") (pin "3") (pinfunction "Q3_3") (pintype "bidirectional"))
      (node (ref "R37") (pin "2") (pinfunction "2_2") (pintype "passive"))
    )
    (net (code "161") (name "SR12") (class "Default")
      (node (ref "D11") (pin "15") (pinfunction "D4_15") (pintype "bidirectional"))
      (node (ref "IC3") (pin "4") (pinfunction "Q4_4") (pintype "bidirectional"))
      (node (ref "R38") (pin "2") (pinfunction "2_2") (pintype "passive"))
    )
    (net (code "162") (name "SR13") (class "Default")
      (node (ref "D11") (pin "14") (pinfunction "D5_14") (pintype "bidirectional"))
      (node (ref "IC3") (pin "5") (pinfunction "Q5_5") (pintype "bidirectional"))
      (node (ref "R39") (pin "2") (pinfunction "2_2") (pintype "passive"))
    )
    (net (code "163") (name "SR14") (class "Default")
      (node (ref "D11") (pin "13") (pinfunction "D6_13") (pintype "bidirectional"))
      (node (ref "IC3") (pin "6") (pinfunction "Q6_6") (pintype "bidirectional"))
      (node (ref "R40") (pin "2") (pinfunction "2_2") (pintype "passive"))
    )
    (net (code "164") (name "SR15") (class "Default")
      (node (ref "D11") (pin "12") (pinfunction "D7_12") (pintype "bidirectional"))
      (node (ref "IC3") (pin "7") (pinfunction "Q7_7") (pintype "bidirectional"))
      (node (ref "R41") (pin "2") (pinfunction "2_2") (pintype "passive"))
    )
    (net (code "165") (name "SR15'") (class "Default")
      (node (ref "D18") (pin "9") (pinfunction "B_9") (pintype "input"))
      (node (ref "IC3") (pin "9") (pinfunction "Q7'_9") (pintype "bidirectional"))
    )
    (net (code "166") (name "SRC_CLK") (class "Default")
      (node (ref "D23") (pin "4") (pinfunction "D0_4") (pintype "bidirectional"))
      (node (ref "D24") (pin "4") (pinfunction "D0_4") (pintype "bidirectional"))
      (node (ref "N3") (pin "3") (pinfunction "Q_3") (pintype "output"))
    )
    (net (code "167") (name "SR_CLK") (class "Default")
      (node (ref "D16") (pin "3") (pinfunction "Y_3") (pintype "output"))
      (node (ref "IC3") (pin "11") (pinfunction "SH_CP_11") (pintype "bidirectional"))
      (node (ref "IC3") (pin "12") (pinfunction "ST_CP_12") (pintype "bidirectional"))
      (node (ref "IC4") (pin "11") (pinfunction "SH_CP_11") (pintype "bidirectional"))
      (node (ref "IC4") (pin "12") (pinfunction "ST_CP_12") (pintype "bidirectional"))
    )
    (net (code "168") (name "SUSTAIN_A") (class "Default")
      (node (ref "N4") (pin "7") (pinfunction "DIS_7") (pintype "input"))
      (node (ref "R24") (pin "3") (pinfunction "2_3") (pintype "passive"))
      (node (ref "X15") (pin "1") (pinfunction "1_1") (pintype "passive"))
      (node (ref "X5") (pin "1") (pinfunction "1_1") (pintype "passive"))
    )
    (net (code "169") (name "SUSTAIN_B") (class "Default")
      (node (ref "N5") (pin "5") (pinfunction "P_5") (pintype "bidirectional"))
      (node (ref "R24") (pin "2") (pinfunction "3_2") (pintype "passive"))
      (node (ref "X15") (pin "2") (pinfunction "2_2") (pintype "passive"))
      (node (ref "X5") (pin "2") (pinfunction "2_2") (pintype "passive"))
    )
    (net (code "170") (name "SUSTAIN_C") (class "Default")
      (node (ref "R24") (pin "1") (pinfunction "1_1") (pintype "passive"))
      (node (ref "R69") (pin "1") (pinfunction "1_1") (pintype "passive"))
      (node (ref "X15") (pin "3") (pinfunction "3_3") (pintype "passive"))
      (node (ref "X5") (pin "3") (pinfunction "3_3") (pintype "passive"))
    )
    (net (code "171") (name "U1") (class "Default")
      (node (ref "N1") (pin "13") (pinfunction "CHANNELIN/OUTA0_13") (pintype "bidirectional"))
      (node (ref "R1") (pin "2") (pinfunction "3_2") (pintype "passive"))
      (node (ref "SV1") (pin "1") (pinfunction "1_1") (pintype "passive"))
      (node (ref "SV3") (pin "8") (pinfunction "8_8") (pintype "passive"))
    )
    (net (code "172") (name "U1_ON") (class "Default")
      (node (ref "D4") (pin "4") (pinfunction "D0_4") (pintype "bidirectional"))
      (node (ref "R9") (pin "2") (pinfunction "2_2") (pintype "passive"))
      (node (ref "S1") (pin "2") (pinfunction "P_2") (pintype "passive"))
    )
    (net (code "173") (name "U2") (class "Default")
      (node (ref "N1") (pin "14") (pinfunction "CHANNELIN/OUTA1_14") (pintype "bidirectional"))
      (node (ref "R2") (pin "2") (pinfunction "3_2") (pintype "passive"))
      (node (ref "SV1") (pin "2") (pinfunction "2_2") (pintype "passive"))
      (node (ref "SV3") (pin "7") (pinfunction "7_7") (pintype "passive"))
    )
    (net (code "174") (name "U2_ON") (class "Default")
      (node (ref "D4") (pin "3") (pinfunction "D1_3") (pintype "bidirectional"))
      (node (ref "R10") (pin "2") (pinfunction "2_2") (pintype "passive"))
      (node (ref "S2") (pin "2") (pinfunction "P_2") (pintype "passive"))
    )
    (net (code "175") (name "U3") (class "Default")
      (node (ref "N1") (pin "15") (pinfunction "CHANNELIN/OUTA2_15") (pintype "bidirectional"))
      (node (ref "R3") (pin "2") (pinfunction "3_2") (pintype "passive"))
      (node (ref "SV1") (pin "3") (pinfunction "3_3") (pintype "passive"))
      (node (ref "SV3") (pin "6") (pinfunction "6_6") (pintype "passive"))
    )
    (net (code "176") (name "U3_ON") (class "Default")
      (node (ref "D4") (pin "2") (pinfunction "D2_2") (pintype "bidirectional"))
      (node (ref "R11") (pin "2") (pinfunction "2_2") (pintype "passive"))
      (node (ref "S3") (pin "2") (pinfunction "P_2") (pintype "passive"))
    )
    (net (code "177") (name "U4") (class "Default")
      (node (ref "N1") (pin "12") (pinfunction "CHANNELIN/OUTA3_12") (pintype "bidirectional"))
      (node (ref "R4") (pin "2") (pinfunction "3_2") (pintype "passive"))
      (node (ref "SV1") (pin "4") (pinfunction "4_4") (pintype "passive"))
      (node (ref "SV3") (pin "5") (pinfunction "5_5") (pintype "passive"))
    )
    (net (code "178") (name "U4_ON") (class "Default")
      (node (ref "D4") (pin "1") (pinfunction "D3_1") (pintype "bidirectional"))
      (node (ref "R12") (pin "2") (pinfunction "2_2") (pintype "passive"))
      (node (ref "S4") (pin "2") (pinfunction "P_2") (pintype "passive"))
    )
    (net (code "179") (name "U5") (class "Default")
      (node (ref "N1") (pin "1") (pinfunction "CHANNELIN/OUTA4_1") (pintype "bidirectional"))
      (node (ref "R5") (pin "2") (pinfunction "3_2") (pintype "passive"))
      (node (ref "SV1") (pin "5") (pinfunction "5_5") (pintype "passive"))
      (node (ref "SV3") (pin "4") (pinfunction "4_4") (pintype "passive"))
    )
    (net (code "180") (name "U5_ON") (class "Default")
      (node (ref "D4") (pin "15") (pinfunction "D4_15") (pintype "bidirectional"))
      (node (ref "R13") (pin "2") (pinfunction "2_2") (pintype "passive"))
      (node (ref "S5") (pin "2") (pinfunction "P_2") (pintype "passive"))
    )
    (net (code "181") (name "U6") (class "Default")
      (node (ref "N1") (pin "5") (pinfunction "CHANNELIN/OUTA5_5") (pintype "bidirectional"))
      (node (ref "R6") (pin "2") (pinfunction "3_2") (pintype "passive"))
      (node (ref "SV1") (pin "6") (pinfunction "6_6") (pintype "passive"))
      (node (ref "SV3") (pin "3") (pinfunction "3_3") (pintype "passive"))
    )
    (net (code "182") (name "U6_ON") (class "Default")
      (node (ref "D4") (pin "14") (pinfunction "D5_14") (pintype "bidirectional"))
      (node (ref "R14") (pin "2") (pinfunction "2_2") (pintype "passive"))
      (node (ref "S6") (pin "2") (pinfunction "P_2") (pintype "passive"))
    )
    (net (code "183") (name "U7") (class "Default")
      (node (ref "N1") (pin "2") (pinfunction "CHANNELIN/OUTA6_2") (pintype "bidirectional"))
      (node (ref "R7") (pin "2") (pinfunction "3_2") (pintype "passive"))
      (node (ref "SV1") (pin "7") (pinfunction "7_7") (pintype "passive"))
      (node (ref "SV3") (pin "2") (pinfunction "2_2") (pintype "passive"))
    )
    (net (code "184") (name "U7_ON") (class "Default")
      (node (ref "D4") (pin "13") (pinfunction "D6_13") (pintype "bidirectional"))
      (node (ref "R15") (pin "2") (pinfunction "2_2") (pintype "passive"))
      (node (ref "S7") (pin "2") (pinfunction "P_2") (pintype "passive"))
    )
    (net (code "185") (name "U8") (class "Default")
      (node (ref "N1") (pin "4") (pinfunction "CHANNELIN/OUTA7_4") (pintype "bidirectional"))
      (node (ref "R8") (pin "2") (pinfunction "3_2") (pintype "passive"))
      (node (ref "SV1") (pin "8") (pinfunction "8_8") (pintype "passive"))
      (node (ref "SV3") (pin "1") (pinfunction "1_1") (pintype "passive"))
    )
    (net (code "186") (name "U8_ON") (class "Default")
      (node (ref "D4") (pin "12") (pinfunction "D7_12") (pintype "bidirectional"))
      (node (ref "R16") (pin "2") (pinfunction "2_2") (pintype "passive"))
      (node (ref "S8") (pin "2") (pinfunction "P_2") (pintype "passive"))
    )
    (net (code "187") (name "UN") (class "Default")
      (node (ref "D3") (pin "1") (pinfunction "VIN_1") (pintype "bidirectional"))
      (node (ref "N1") (pin "3") (pinfunction "COMOUT/INA_3") (pintype "bidirectional"))
    )
    (net (code "188") (name "U_OCT") (class "Default")
      (node (ref "D2") (pin "1") (pinfunction "VIN_1") (pintype "bidirectional"))
    )
    (net (code "189") (name "U_ON") (class "Default")
      (node (ref "D4") (pin "5") (pinfunction "Y_5") (pintype "bidirectional"))
    )
    (net (code "190") (name "VOL-POT_A") (class "Default")
      (node (ref "R21") (pin "3") (pinfunction "2_3") (pintype "passive"))
      (node (ref "X10") (pin "1") (pinfunction "2_1") (pintype "passive"))
      (node (ref "X17") (pin "2") (pinfunction "2_2") (pintype "passive"))
    )
    (net (code "191") (name "VOL-POT_B") (class "Default")
      (node (ref "R21") (pin "1") (pinfunction "1_1") (pintype "passive"))
      (node (ref "R21") (pin "2") (pinfunction "3_2") (pintype "passive"))
      (node (ref "X10") (pin "2") (pinfunction "3_2") (pintype "passive"))
      (node (ref "X17") (pin "1") (pinfunction "1_1") (pintype "passive"))
    )
    (net (code "192") (name "Y1") (class "Default")
      (node (ref "D12") (pin "5") (pinfunction "Y_5") (pintype "bidirectional"))
      (node (ref "D17") (pin "1") (pinfunction "A_1") (pintype "input"))
    )
    (net (code "193") (name "Y2") (class "Default")
      (node (ref "D11") (pin "5") (pinfunction "Y_5") (pintype "bidirectional"))
      (node (ref "D17") (pin "9") (pinfunction "B_9") (pintype "input"))
    )
    (net (code "194") (name "unconnected-(D1A-~{TCD}-Pad13)") (class "Default")
      (node (ref "D1") (pin "13") (pinfunction "~{TCD}_13") (pintype "output"))
    )
    (net (code "195") (name "unconnected-(D1A-~{TCU}-Pad12)") (class "Default")
      (node (ref "D1") (pin "12") (pinfunction "~{TCU}_12") (pintype "output"))
    )
    (net (code "196") (name "unconnected-(D2-DB0-Pad2)") (class "Default")
      (node (ref "D2") (pin "2") (pinfunction "DB0_2") (pintype "bidirectional"))
    )
    (net (code "197") (name "unconnected-(D2-DB1-Pad3)") (class "Default")
      (node (ref "D2") (pin "3") (pinfunction "DB1_3") (pintype "bidirectional"))
    )
    (net (code "198") (name "unconnected-(D2-DB2-Pad4)") (class "Default")
      (node (ref "D2") (pin "4") (pinfunction "DB2_4") (pintype "bidirectional"))
    )
    (net (code "199") (name "unconnected-(D2-DB3-Pad5)") (class "Default")
      (node (ref "D2") (pin "5") (pinfunction "DB3_5") (pintype "bidirectional"))
    )
    (net (code "200") (name "unconnected-(D2-NC-Pad19)") (class "Default")
      (node (ref "D2") (pin "19") (pinfunction "NC_19") (pintype "no_connect"))
    )
    (net (code "201") (name "unconnected-(D2-~{INT}-Pad9)") (class "Default")
      (node (ref "D2") (pin "9") (pinfunction "~{INT}_9") (pintype "bidirectional"))
    )
    (net (code "202") (name "unconnected-(D2-~{OFL}-Pad18)") (class "Default")
      (node (ref "D2") (pin "18") (pinfunction "~{OFL}_18") (pintype "bidirectional"))
    )
    (net (code "203") (name "unconnected-(D3-DB0-Pad2)") (class "Default")
      (node (ref "D3") (pin "2") (pinfunction "DB0_2") (pintype "bidirectional"))
    )
    (net (code "204") (name "unconnected-(D3-DB1-Pad3)") (class "Default")
      (node (ref "D3") (pin "3") (pinfunction "DB1_3") (pintype "bidirectional"))
    )
    (net (code "205") (name "unconnected-(D3-DB2-Pad4)") (class "Default")
      (node (ref "D3") (pin "4") (pinfunction "DB2_4") (pintype "bidirectional"))
    )
    (net (code "206") (name "unconnected-(D3-DB7-Pad17)") (class "Default")
      (node (ref "D3") (pin "17") (pinfunction "DB7_17") (pintype "bidirectional"))
    )
    (net (code "207") (name "unconnected-(D3-NC-Pad19)") (class "Default")
      (node (ref "D3") (pin "19") (pinfunction "NC_19") (pintype "no_connect"))
    )
    (net (code "208") (name "unconnected-(D3-~{INT}-Pad9)") (class "Default")
      (node (ref "D3") (pin "9") (pinfunction "~{INT}_9") (pintype "bidirectional"))
    )
    (net (code "209") (name "unconnected-(D3-~{OFL}-Pad18)") (class "Default")
      (node (ref "D3") (pin "18") (pinfunction "~{OFL}_18") (pintype "bidirectional"))
    )
    (net (code "210") (name "unconnected-(D4-W-Pad6)") (class "Default")
      (node (ref "D4") (pin "6") (pinfunction "W_6") (pintype "bidirectional"))
    )
    (net (code "211") (name "unconnected-(D5-OUT1-Pad1)") (class "Default")
      (node (ref "D5") (pin "1") (pinfunction "OUT1_1") (pintype "output"))
    )
    (net (code "212") (name "unconnected-(D5-OUT2-Pad2)") (class "Default")
      (node (ref "D5") (pin "2") (pinfunction "OUT2_2") (pintype "output"))
    )
    (net (code "213") (name "unconnected-(D5-REF-Pad15)") (class "Default")
      (node (ref "D5") (pin "15") (pinfunction "REF_15") (pintype "input"))
    )
    (net (code "214") (name "unconnected-(D5-RFB-Pad16)") (class "Default")
      (node (ref "D5") (pin "16") (pinfunction "RFB_16") (pintype "output"))
    )
    (net (code "215") (name "unconnected-(D5-~{CS}-Pad12)") (class "Default")
      (node (ref "D5") (pin "12") (pinfunction "~{CS}_12") (pintype "input"))
    )
    (net (code "216") (name "unconnected-(D8B-~{CLR}-Pad2)") (class "Default")
      (node (ref "D8") (pin "2") (pinfunction "~{CLR}_2") (pintype "input"))
    )
    (net (code "217") (name "unconnected-(D10-DB7-Pad4)") (class "Default")
      (node (ref "D10") (pin "4") (pinfunction "DB7_4") (pintype "input"))
    )
    (net (code "218") (name "unconnected-(D10-OUT1-Pad1)") (class "Default")
      (node (ref "D10") (pin "1") (pinfunction "OUT1_1") (pintype "output"))
    )
    (net (code "219") (name "unconnected-(D10-OUT2-Pad2)") (class "Default")
      (node (ref "D10") (pin "2") (pinfunction "OUT2_2") (pintype "output"))
    )
    (net (code "220") (name "unconnected-(D10-REF-Pad15)") (class "Default")
      (node (ref "D10") (pin "15") (pinfunction "REF_15") (pintype "input"))
    )
    (net (code "221") (name "unconnected-(D10-RFB-Pad16)") (class "Default")
      (node (ref "D10") (pin "16") (pinfunction "RFB_16") (pintype "output"))
    )
    (net (code "222") (name "unconnected-(D10-~{CS}-Pad12)") (class "Default")
      (node (ref "D10") (pin "12") (pinfunction "~{CS}_12") (pintype "input"))
    )
    (net (code "223") (name "unconnected-(D11-W-Pad6)") (class "Default")
      (node (ref "D11") (pin "6") (pinfunction "W_6") (pintype "bidirectional"))
    )
    (net (code "224") (name "unconnected-(D12-W-Pad6)") (class "Default")
      (node (ref "D12") (pin "6") (pinfunction "W_6") (pintype "bidirectional"))
    )
    (net (code "225") (name "unconnected-(D13B-~{CLR}-Pad2)") (class "Default")
      (node (ref "D13") (pin "2") (pinfunction "~{CLR}_2") (pintype "input"))
    )
    (net (code "226") (name "unconnected-(D13B-~{Q}-Pad13)") (class "Default")
      (node (ref "D13") (pin "13") (pinfunction "~{Q}_13") (pintype "output"))
    )
    (net (code "227") (name "unconnected-(D13C-J-Pad7)") (class "Default")
      (node (ref "D13") (pin "7") (pinfunction "J_7") (pintype "input"))
    )
    (net (code "228") (name "unconnected-(D13C-K-Pad10)") (class "Default")
      (node (ref "D13") (pin "10") (pinfunction "K_10") (pintype "input"))
    )
    (net (code "229") (name "unconnected-(D13C-~{CLK}-Pad5)") (class "Default")
      (node (ref "D13") (pin "5") (pinfunction "~{CLK}_5") (pintype "input"))
    )
    (net (code "230") (name "unconnected-(D13C-~{CLR}-Pad6)") (class "Default")
      (node (ref "D13") (pin "6") (pinfunction "~{CLR}_6") (pintype "input"))
    )
    (net (code "231") (name "unconnected-(D13C-~{Q}-Pad8)") (class "Default")
      (node (ref "D13") (pin "8") (pinfunction "~{Q}_8") (pintype "output"))
    )
    (net (code "232") (name "unconnected-(D19B-5Q-Pad15)") (class "Default")
      (node (ref "D19") (pin "15") (pinfunction "5Q_15") (pintype "bidirectional"))
    )
    (net (code "233") (name "unconnected-(D19B-6Q-Pad14)") (class "Default")
      (node (ref "D19") (pin "14") (pinfunction "6Q_14") (pintype "bidirectional"))
    )
    (net (code "234") (name "unconnected-(D19B-7Q-Pad13)") (class "Default")
      (node (ref "D19") (pin "13") (pinfunction "7Q_13") (pintype "bidirectional"))
    )
    (net (code "235") (name "unconnected-(D19B-8Q-Pad12)") (class "Default")
      (node (ref "D19") (pin "12") (pinfunction "8Q_12") (pintype "bidirectional"))
    )
    (net (code "236") (name "unconnected-(D21B-~{CLR}-Pad2)") (class "Default")
      (node (ref "D21") (pin "2") (pinfunction "~{CLR}_2") (pintype "input"))
    )
    (net (code "237") (name "unconnected-(D23-A-Pad11)") (class "Default")
      (node (ref "D23") (pin "11") (pinfunction "A_11") (pintype "bidirectional"))
    )
    (net (code "238") (name "unconnected-(D23-B-Pad10)") (class "Default")
      (node (ref "D23") (pin "10") (pinfunction "B_10") (pintype "bidirectional"))
    )
    (net (code "239") (name "unconnected-(D23-C-Pad9)") (class "Default")
      (node (ref "D23") (pin "9") (pinfunction "C_9") (pintype "bidirectional"))
    )
    (net (code "240") (name "unconnected-(D23-D5-Pad14)") (class "Default")
      (node (ref "D23") (pin "14") (pinfunction "D5_14") (pintype "bidirectional"))
    )
    (net (code "241") (name "unconnected-(D23-D6-Pad13)") (class "Default")
      (node (ref "D23") (pin "13") (pinfunction "D6_13") (pintype "bidirectional"))
    )
    (net (code "242") (name "unconnected-(D23-D7-Pad12)") (class "Default")
      (node (ref "D23") (pin "12") (pinfunction "D7_12") (pintype "bidirectional"))
    )
    (net (code "243") (name "unconnected-(D23-W-Pad6)") (class "Default")
      (node (ref "D23") (pin "6") (pinfunction "W_6") (pintype "bidirectional"))
    )
    (net (code "244") (name "unconnected-(D23-Y-Pad5)") (class "Default")
      (node (ref "D23") (pin "5") (pinfunction "Y_5") (pintype "bidirectional"))
    )
    (net (code "245") (name "unconnected-(D24-A-Pad11)") (class "Default")
      (node (ref "D24") (pin "11") (pinfunction "A_11") (pintype "bidirectional"))
    )
    (net (code "246") (name "unconnected-(D24-B-Pad10)") (class "Default")
      (node (ref "D24") (pin "10") (pinfunction "B_10") (pintype "bidirectional"))
    )
    (net (code "247") (name "unconnected-(D24-C-Pad9)") (class "Default")
      (node (ref "D24") (pin "9") (pinfunction "C_9") (pintype "bidirectional"))
    )
    (net (code "248") (name "unconnected-(D24-D5-Pad14)") (class "Default")
      (node (ref "D24") (pin "14") (pinfunction "D5_14") (pintype "bidirectional"))
    )
    (net (code "249") (name "unconnected-(D24-D6-Pad13)") (class "Default")
      (node (ref "D24") (pin "13") (pinfunction "D6_13") (pintype "bidirectional"))
    )
    (net (code "250") (name "unconnected-(D24-D7-Pad12)") (class "Default")
      (node (ref "D24") (pin "12") (pinfunction "D7_12") (pintype "bidirectional"))
    )
    (net (code "251") (name "unconnected-(D24-W-Pad6)") (class "Default")
      (node (ref "D24") (pin "6") (pinfunction "W_6") (pintype "bidirectional"))
    )
    (net (code "252") (name "unconnected-(D24-Y-Pad5)") (class "Default")
      (node (ref "D24") (pin "5") (pinfunction "Y_5") (pintype "bidirectional"))
    )
    (net (code "253") (name "unconnected-(D25A-CPU-Pad5)") (class "Default")
      (node (ref "D25") (pin "5") (pinfunction "CPU_5") (pintype "input"))
    )
    (net (code "254") (name "unconnected-(D25A-D0-Pad15)") (class "Default")
      (node (ref "D25") (pin "15") (pinfunction "D0_15") (pintype "input"))
    )
    (net (code "255") (name "unconnected-(D25A-D1-Pad1)") (class "Default")
      (node (ref "D25") (pin "1") (pinfunction "D1_1") (pintype "input"))
    )
    (net (code "256") (name "unconnected-(D25A-D2-Pad10)") (class "Default")
      (node (ref "D25") (pin "10") (pinfunction "D2_10") (pintype "input"))
    )
    (net (code "257") (name "unconnected-(D25A-D3-Pad9)") (class "Default")
      (node (ref "D25") (pin "9") (pinfunction "D3_9") (pintype "input"))
    )
    (net (code "258") (name "unconnected-(D25A-~{TCD}-Pad13)") (class "Default")
      (node (ref "D25") (pin "13") (pinfunction "~{TCD}_13") (pintype "output"))
    )
    (net (code "259") (name "unconnected-(D25A-~{TCU}-Pad12)") (class "Default")
      (node (ref "D25") (pin "12") (pinfunction "~{TCU}_12") (pintype "output"))
    )
    (net (code "260") (name "unconnected-(D26B-J-Pad14)") (class "Default")
      (node (ref "D26") (pin "14") (pinfunction "J_14") (pintype "input"))
    )
    (net (code "261") (name "unconnected-(D26B-K-Pad3)") (class "Default")
      (node (ref "D26") (pin "3") (pinfunction "K_3") (pintype "input"))
    )
    (net (code "262") (name "unconnected-(D26B-~{CLK}-Pad1)") (class "Default")
      (node (ref "D26") (pin "1") (pinfunction "~{CLK}_1") (pintype "input"))
    )
    (net (code "263") (name "unconnected-(D26B-~{CLR}-Pad2)") (class "Default")
      (node (ref "D26") (pin "2") (pinfunction "~{CLR}_2") (pintype "input"))
    )
    (net (code "264") (name "unconnected-(D26B-~{Q}-Pad13)") (class "Default")
      (node (ref "D26") (pin "13") (pinfunction "~{Q}_13") (pintype "output"))
    )
    (net (code "265") (name "unconnected-(D26C-J-Pad7)") (class "Default")
      (node (ref "D26") (pin "7") (pinfunction "J_7") (pintype "input"))
    )
    (net (code "266") (name "unconnected-(D26C-K-Pad10)") (class "Default")
      (node (ref "D26") (pin "10") (pinfunction "K_10") (pintype "input"))
    )
    (net (code "267") (name "unconnected-(D26C-~{CLK}-Pad5)") (class "Default")
      (node (ref "D26") (pin "5") (pinfunction "~{CLK}_5") (pintype "input"))
    )
    (net (code "268") (name "unconnected-(D26C-~{CLR}-Pad6)") (class "Default")
      (node (ref "D26") (pin "6") (pinfunction "~{CLR}_6") (pintype "input"))
    )
    (net (code "269") (name "unconnected-(D26C-~{Q}-Pad8)") (class "Default")
      (node (ref "D26") (pin "8") (pinfunction "~{Q}_8") (pintype "output"))
    )
    (net (code "270") (name "unconnected-(D27B-J-Pad14)") (class "Default")
      (node (ref "D27") (pin "14") (pinfunction "J_14") (pintype "input"))
    )
    (net (code "271") (name "unconnected-(D27B-K-Pad3)") (class "Default")
      (node (ref "D27") (pin "3") (pinfunction "K_3") (pintype "input"))
    )
    (net (code "272") (name "unconnected-(D27B-Q-Pad12)") (class "Default")
      (node (ref "D27") (pin "12") (pinfunction "Q_12") (pintype "output"))
    )
    (net (code "273") (name "unconnected-(D27B-~{CLK}-Pad1)") (class "Default")
      (node (ref "D27") (pin "1") (pinfunction "~{CLK}_1") (pintype "input"))
    )
    (net (code "274") (name "unconnected-(D27B-~{CLR}-Pad2)") (class "Default")
      (node (ref "D27") (pin "2") (pinfunction "~{CLR}_2") (pintype "input"))
    )
    (net (code "275") (name "unconnected-(D27B-~{Q}-Pad13)") (class "Default")
      (node (ref "D27") (pin "13") (pinfunction "~{Q}_13") (pintype "output"))
    )
    (net (code "276") (name "unconnected-(D27C-J-Pad7)") (class "Default")
      (node (ref "D27") (pin "7") (pinfunction "J_7") (pintype "input"))
    )
    (net (code "277") (name "unconnected-(D27C-K-Pad10)") (class "Default")
      (node (ref "D27") (pin "10") (pinfunction "K_10") (pintype "input"))
    )
    (net (code "278") (name "unconnected-(D27C-Q-Pad9)") (class "Default")
      (node (ref "D27") (pin "9") (pinfunction "Q_9") (pintype "output"))
    )
    (net (code "279") (name "unconnected-(D27C-~{CLK}-Pad5)") (class "Default")
      (node (ref "D27") (pin "5") (pinfunction "~{CLK}_5") (pintype "input"))
    )
    (net (code "280") (name "unconnected-(D27C-~{CLR}-Pad6)") (class "Default")
      (node (ref "D27") (pin "6") (pinfunction "~{CLR}_6") (pintype "input"))
    )
    (net (code "281") (name "unconnected-(D27C-~{Q}-Pad8)") (class "Default")
      (node (ref "D27") (pin "8") (pinfunction "~{Q}_8") (pintype "output"))
    )
    (net (code "282") (name "unconnected-(D28B-J-Pad14)") (class "Default")
      (node (ref "D28") (pin "14") (pinfunction "J_14") (pintype "input"))
    )
    (net (code "283") (name "unconnected-(D28B-K-Pad3)") (class "Default")
      (node (ref "D28") (pin "3") (pinfunction "K_3") (pintype "input"))
    )
    (net (code "284") (name "unconnected-(D28B-Q-Pad12)") (class "Default")
      (node (ref "D28") (pin "12") (pinfunction "Q_12") (pintype "output"))
    )
    (net (code "285") (name "unconnected-(D28B-~{CLK}-Pad1)") (class "Default")
      (node (ref "D28") (pin "1") (pinfunction "~{CLK}_1") (pintype "input"))
    )
    (net (code "286") (name "unconnected-(D28B-~{CLR}-Pad2)") (class "Default")
      (node (ref "D28") (pin "2") (pinfunction "~{CLR}_2") (pintype "input"))
    )
    (net (code "287") (name "unconnected-(D28B-~{Q}-Pad13)") (class "Default")
      (node (ref "D28") (pin "13") (pinfunction "~{Q}_13") (pintype "output"))
    )
    (net (code "288") (name "unconnected-(D28C-~{CLR}-Pad6)") (class "Default")
      (node (ref "D28") (pin "6") (pinfunction "~{CLR}_6") (pintype "input"))
    )
    (net (code "289") (name "unconnected-(D28C-~{Q}-Pad8)") (class "Default")
      (node (ref "D28") (pin "8") (pinfunction "~{Q}_8") (pintype "output"))
    )
    (net (code "290") (name "unconnected-(D29B-~{CLR}-Pad2)") (class "Default")
      (node (ref "D29") (pin "2") (pinfunction "~{CLR}_2") (pintype "input"))
    )
    (net (code "291") (name "unconnected-(D29B-~{Q}-Pad13)") (class "Default")
      (node (ref "D29") (pin "13") (pinfunction "~{Q}_13") (pintype "output"))
    )
    (net (code "292") (name "unconnected-(J1-Pad2)") (class "Default")
      (node (ref "J1") (pin "2") (pinfunction "2_2") (pintype "bidirectional"))
    )
    (net (code "293") (name "unconnected-(J1-Pad3)") (class "Default")
      (node (ref "J1") (pin "3") (pinfunction "3_3") (pintype "bidirectional"))
    )
    (net (code "294") (name "unconnected-(J1-Pad4)") (class "Default")
      (node (ref "J1") (pin "4") (pinfunction "4_4") (pintype "bidirectional"))
    )
    (net (code "295") (name "unconnected-(J2-Pad2)") (class "Default")
      (node (ref "J2") (pin "2") (pinfunction "2_2") (pintype "bidirectional"))
    )
    (net (code "296") (name "unconnected-(J2-Pad3)") (class "Default")
      (node (ref "J2") (pin "3") (pinfunction "3_3") (pintype "bidirectional"))
    )
    (net (code "297") (name "unconnected-(J2-Pad4)") (class "Default")
      (node (ref "J2") (pin "4") (pinfunction "4_4") (pintype "bidirectional"))
    )
    (net (code "298") (name "unconnected-(J3-Pad2)") (class "Default")
      (node (ref "J3") (pin "2") (pinfunction "2_2") (pintype "bidirectional"))
    )
    (net (code "299") (name "unconnected-(J3-Pad3)") (class "Default")
      (node (ref "J3") (pin "3") (pinfunction "3_3") (pintype "bidirectional"))
    )
    (net (code "300") (name "unconnected-(J3-Pad4)") (class "Default")
      (node (ref "J3") (pin "4") (pinfunction "4_4") (pintype "bidirectional"))
    )
    (net (code "301") (name "unconnected-(J4-Pad2)") (class "Default")
      (node (ref "J4") (pin "2") (pinfunction "2_2") (pintype "bidirectional"))
    )
    (net (code "302") (name "unconnected-(J4-Pad3)") (class "Default")
      (node (ref "J4") (pin "3") (pinfunction "3_3") (pintype "bidirectional"))
    )
    (net (code "303") (name "unconnected-(J4-Pad4)") (class "Default")
      (node (ref "J4") (pin "4") (pinfunction "4_4") (pintype "bidirectional"))
    )
    (net (code "304") (name "unconnected-(J5-Pad2)") (class "Default")
      (node (ref "J5") (pin "2") (pinfunction "2_2") (pintype "bidirectional"))
    )
    (net (code "305") (name "unconnected-(J5-Pad3)") (class "Default")
      (node (ref "J5") (pin "3") (pinfunction "3_3") (pintype "bidirectional"))
    )
    (net (code "306") (name "unconnected-(J5-Pad4)") (class "Default")
      (node (ref "J5") (pin "4") (pinfunction "4_4") (pintype "bidirectional"))
    )
    (net (code "307") (name "unconnected-(J6-Pad2)") (class "Default")
      (node (ref "J6") (pin "2") (pinfunction "2_2") (pintype "bidirectional"))
    )
    (net (code "308") (name "unconnected-(J6-Pad3)") (class "Default")
      (node (ref "J6") (pin "3") (pinfunction "3_3") (pintype "bidirectional"))
    )
    (net (code "309") (name "unconnected-(J6-Pad4)") (class "Default")
      (node (ref "J6") (pin "4") (pinfunction "4_4") (pintype "bidirectional"))
    )
    (net (code "310") (name "unconnected-(J7-Pad2)") (class "Default")
      (node (ref "J7") (pin "2") (pinfunction "2_2") (pintype "bidirectional"))
    )
    (net (code "311") (name "unconnected-(J7-Pad3)") (class "Default")
      (node (ref "J7") (pin "3") (pinfunction "3_3") (pintype "bidirectional"))
    )
    (net (code "312") (name "unconnected-(J7-Pad4)") (class "Default")
      (node (ref "J7") (pin "4") (pinfunction "4_4") (pintype "bidirectional"))
    )
    (net (code "313") (name "unconnected-(J8-Pad2)") (class "Default")
      (node (ref "J8") (pin "2") (pinfunction "2_2") (pintype "bidirectional"))
    )
    (net (code "314") (name "unconnected-(J8-Pad3)") (class "Default")
      (node (ref "J8") (pin "3") (pinfunction "3_3") (pintype "bidirectional"))
    )
    (net (code "315") (name "unconnected-(J8-Pad4)") (class "Default")
      (node (ref "J8") (pin "4") (pinfunction "4_4") (pintype "bidirectional"))
    )
    (net (code "316") (name "unconnected-(J9-Pad2)") (class "Default")
      (node (ref "J9") (pin "2") (pinfunction "2_2") (pintype "bidirectional"))
    )
    (net (code "317") (name "unconnected-(J9-Pad3)") (class "Default")
      (node (ref "J9") (pin "3") (pinfunction "3_3") (pintype "bidirectional"))
    )
    (net (code "318") (name "unconnected-(J9-Pad4)") (class "Default")
      (node (ref "J9") (pin "4") (pinfunction "4_4") (pintype "bidirectional"))
    )
    (net (code "319") (name "unconnected-(X18-Pad1)") (class "Default")
      (node (ref "X18") (pin "1") (pinfunction "1_1") (pintype "passive"))
    )
    (net (code "320") (name "unconnected-(X18-Pad2)") (class "Default")
      (node (ref "X18") (pin "2") (pinfunction "2_2") (pintype "passive"))
    )
    (net (code "321") (name "unconnected-(X18-Pad3)") (class "Default")
      (node (ref "X18") (pin "3") (pinfunction "3_3") (pintype "passive"))
    )
    (net (code "322") (name "~{MODE_EN}") (class "Default")
      (node (ref "D7") (pin "1") (pinfunction "A_1") (pintype "input"))
      (node (ref "D7") (pin "10") (pinfunction "A_10") (pintype "input"))
      (node (ref "D7") (pin "13") (pinfunction "A_13") (pintype "input"))
      (node (ref "D7") (pin "4") (pinfunction "A_4") (pintype "input"))
      (node (ref "D8") (pin "13") (pinfunction "~{Q}_13") (pintype "output"))
    )
  )
)
